# schematics.net
KiCad netlist of a schematic drawn in EAGLE
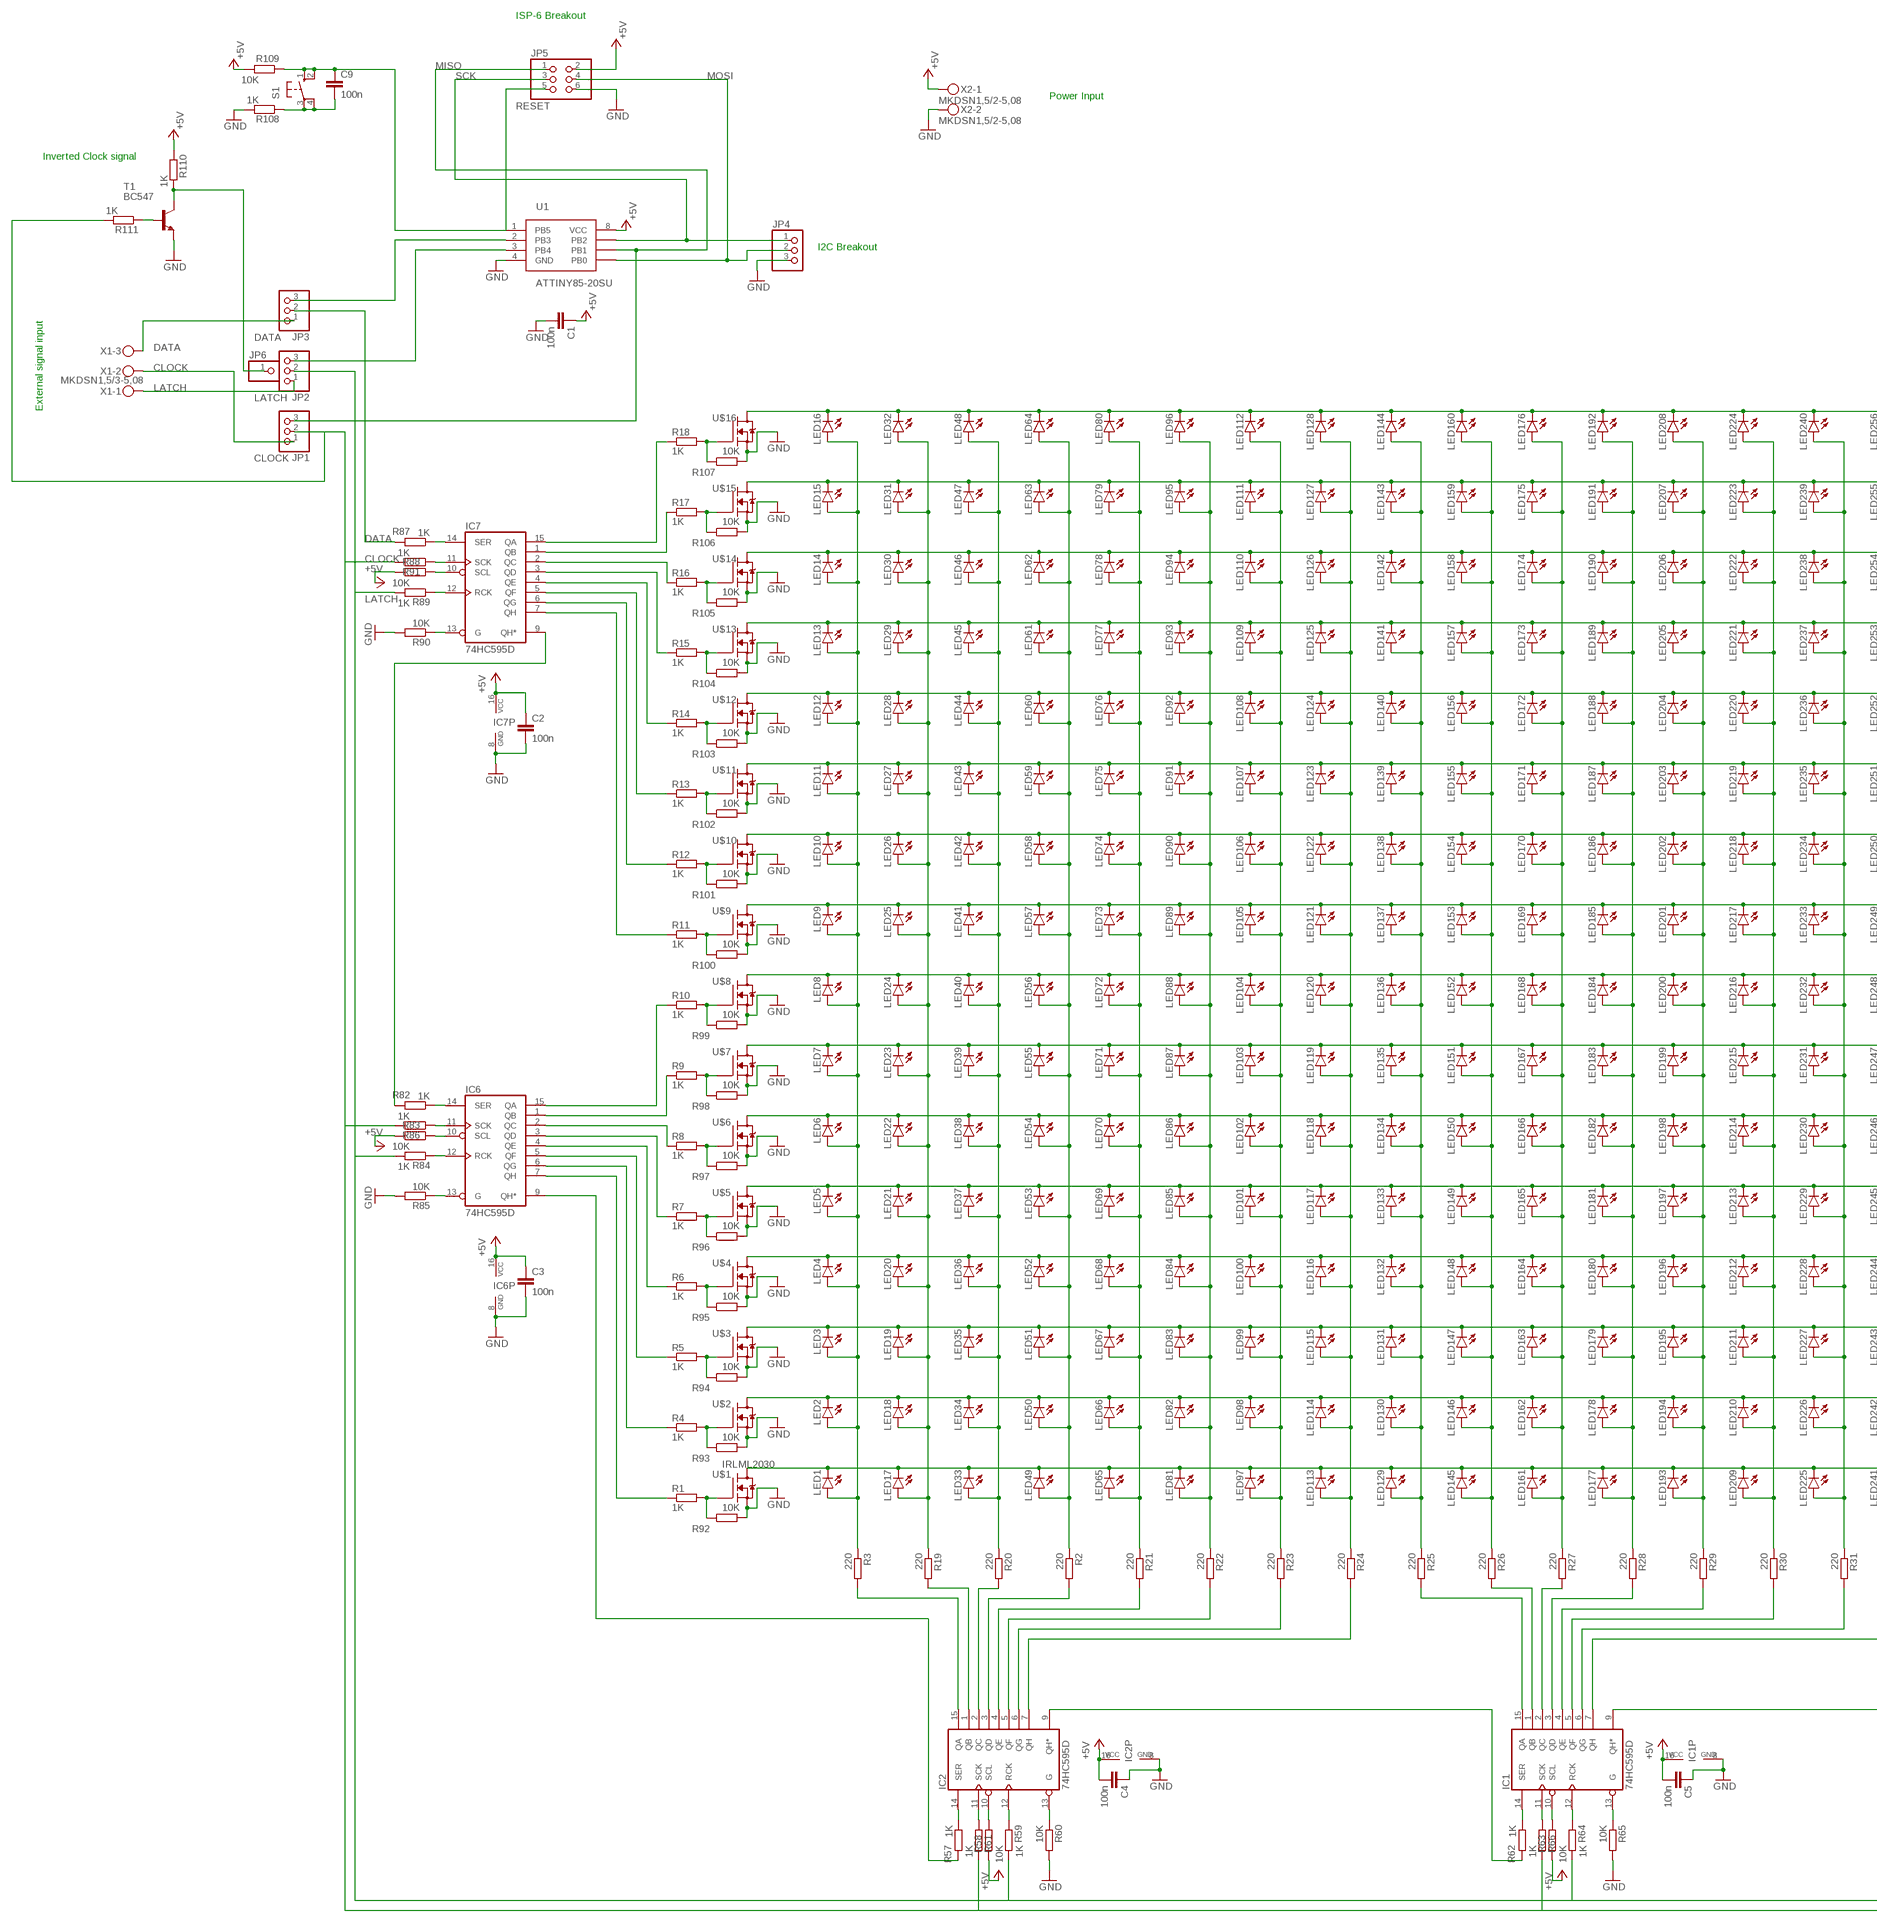
[diagram p0: schematic, sheet 1, part 1 of 2]
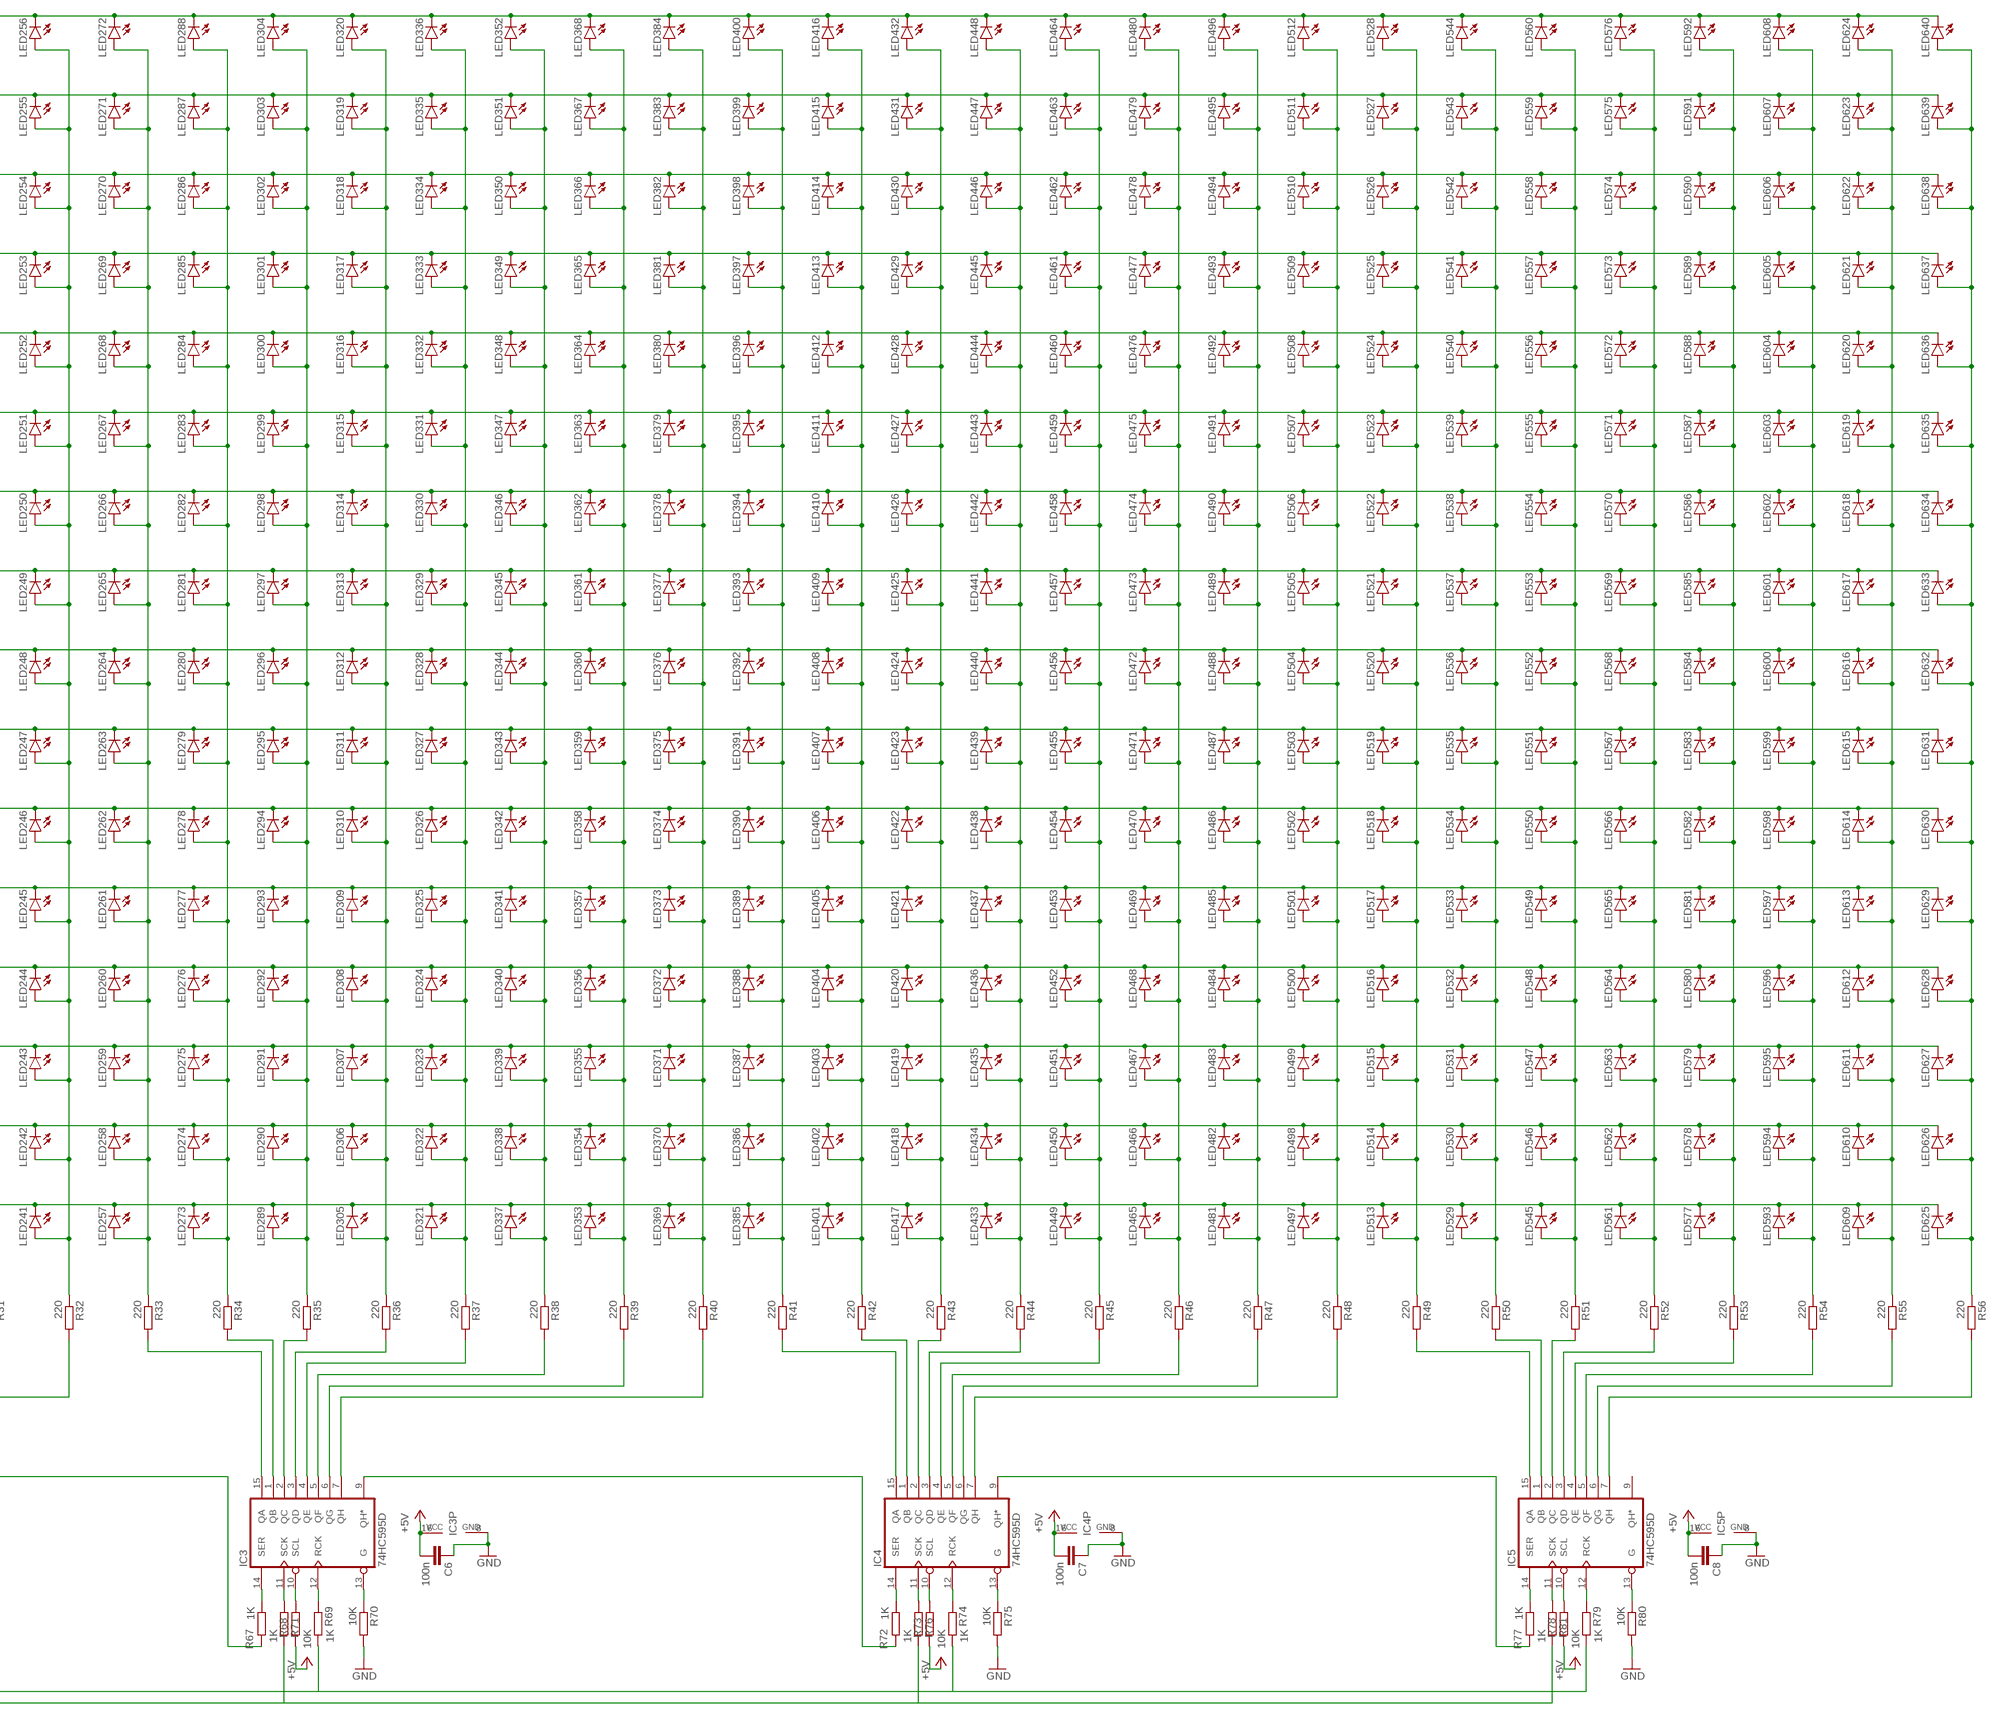
[diagram p1: schematic, sheet 1, part 2 of 2]

(export (version "E")
  (design (tool "Eeschema 10.0.6"))
  (components
    (comp (ref "C1")
      (value "100n")
      (footprint "eagle-import:C0805K")
      (libsource (lib "eagle-import") (part "C-EUC0805K"))
    )
    (comp (ref "C2")
      (value "100n")
      (footprint "eagle-import:C0805K")
      (libsource (lib "eagle-import") (part "C-EUC0805K"))
    )
    (comp (ref "C3")
      (value "100n")
      (footprint "eagle-import:C0805K")
      (libsource (lib "eagle-import") (part "C-EUC0805K"))
    )
    (comp (ref "C4")
      (value "100n")
      (footprint "eagle-import:C0805K")
      (libsource (lib "eagle-import") (part "C-EUC0805K"))
    )
    (comp (ref "C5")
      (value "100n")
      (footprint "eagle-import:C0805K")
      (libsource (lib "eagle-import") (part "C-EUC0805K"))
    )
    (comp (ref "C6")
      (value "100n")
      (footprint "eagle-import:C0805K")
      (libsource (lib "eagle-import") (part "C-EUC0805K"))
    )
    (comp (ref "C7")
      (value "100n")
      (footprint "eagle-import:C0805K")
      (libsource (lib "eagle-import") (part "C-EUC0805K"))
    )
    (comp (ref "C8")
      (value "100n")
      (footprint "eagle-import:C0805K")
      (libsource (lib "eagle-import") (part "C-EUC0805K"))
    )
    (comp (ref "C9")
      (value "100n")
      (footprint "eagle-import:C0805K")
      (libsource (lib "eagle-import") (part "C-EUC0805K"))
    )
    (comp (ref "IC1")
      (value "74HC595D")
      (footprint "eagle-import:SO16")
      (libsource (lib "eagle-import") (part "74595DHC"))
    )
    (comp (ref "IC2")
      (value "74HC595D")
      (footprint "eagle-import:SO16")
      (libsource (lib "eagle-import") (part "74595DHC"))
    )
    (comp (ref "IC3")
      (value "74HC595D")
      (footprint "eagle-import:SO16")
      (libsource (lib "eagle-import") (part "74595DHC"))
    )
    (comp (ref "IC4")
      (value "74HC595D")
      (footprint "eagle-import:SO16")
      (libsource (lib "eagle-import") (part "74595DHC"))
    )
    (comp (ref "IC5")
      (value "74HC595D")
      (footprint "eagle-import:SO16")
      (libsource (lib "eagle-import") (part "74595DHC"))
    )
    (comp (ref "IC6")
      (value "74HC595D")
      (footprint "eagle-import:SO16")
      (libsource (lib "eagle-import") (part "74595DHC"))
    )
    (comp (ref "IC7")
      (value "74HC595D")
      (footprint "eagle-import:SO16")
      (libsource (lib "eagle-import") (part "74595DHC"))
    )
    (comp (ref "JP1")
      (value "PINHD-1X3")
      (footprint "eagle-import:1X03")
      (libsource (lib "eagle-import") (part "PINHD-1X3"))
    )
    (comp (ref "JP2")
      (value "PINHD-1X3")
      (footprint "eagle-import:1X03")
      (libsource (lib "eagle-import") (part "PINHD-1X3"))
    )
    (comp (ref "JP3")
      (value "PINHD-1X3")
      (footprint "eagle-import:1X03")
      (libsource (lib "eagle-import") (part "PINHD-1X3"))
    )
    (comp (ref "JP4")
      (value "PINHD-1X3")
      (footprint "eagle-import:1X03")
      (libsource (lib "eagle-import") (part "PINHD-1X3"))
    )
    (comp (ref "JP5")
      (value "PINHD-2X3")
      (footprint "eagle-import:2X03")
      (libsource (lib "eagle-import") (part "PINHD-2X3"))
    )
    (comp (ref "JP6")
      (value "PINHD-1X1")
      (footprint "eagle-import:1X01")
      (libsource (lib "eagle-import") (part "PINHD-1X1"))
    )
    (comp (ref "LED1")
      (value "LED3MM")
      (footprint "eagle-import:LED3MM")
      (libsource (lib "eagle-import") (part "LED3MM"))
    )
    (comp (ref "LED2")
      (value "LED3MM")
      (footprint "eagle-import:LED3MM")
      (libsource (lib "eagle-import") (part "LED3MM"))
    )
    (comp (ref "LED3")
      (value "LED3MM")
      (footprint "eagle-import:LED3MM")
      (libsource (lib "eagle-import") (part "LED3MM"))
    )
    (comp (ref "LED4")
      (value "LED3MM")
      (footprint "eagle-import:LED3MM")
      (libsource (lib "eagle-import") (part "LED3MM"))
    )
    (comp (ref "LED5")
      (value "LED3MM")
      (footprint "eagle-import:LED3MM")
      (libsource (lib "eagle-import") (part "LED3MM"))
    )
    (comp (ref "LED6")
      (value "LED3MM")
      (footprint "eagle-import:LED3MM")
      (libsource (lib "eagle-import") (part "LED3MM"))
    )
    (comp (ref "LED7")
      (value "LED3MM")
      (footprint "eagle-import:LED3MM")
      (libsource (lib "eagle-import") (part "LED3MM"))
    )
    (comp (ref "LED8")
      (value "LED3MM")
      (footprint "eagle-import:LED3MM")
      (libsource (lib "eagle-import") (part "LED3MM"))
    )
    (comp (ref "LED9")
      (value "LED3MM")
      (footprint "eagle-import:LED3MM")
      (libsource (lib "eagle-import") (part "LED3MM"))
    )
    (comp (ref "LED10")
      (value "LED3MM")
      (footprint "eagle-import:LED3MM")
      (libsource (lib "eagle-import") (part "LED3MM"))
    )
    (comp (ref "LED11")
      (value "LED3MM")
      (footprint "eagle-import:LED3MM")
      (libsource (lib "eagle-import") (part "LED3MM"))
    )
    (comp (ref "LED12")
      (value "LED3MM")
      (footprint "eagle-import:LED3MM")
      (libsource (lib "eagle-import") (part "LED3MM"))
    )
    (comp (ref "LED13")
      (value "LED3MM")
      (footprint "eagle-import:LED3MM")
      (libsource (lib "eagle-import") (part "LED3MM"))
    )
    (comp (ref "LED14")
      (value "LED3MM")
      (footprint "eagle-import:LED3MM")
      (libsource (lib "eagle-import") (part "LED3MM"))
    )
    (comp (ref "LED15")
      (value "LED3MM")
      (footprint "eagle-import:LED3MM")
      (libsource (lib "eagle-import") (part "LED3MM"))
    )
    (comp (ref "LED16")
      (value "LED3MM")
      (footprint "eagle-import:LED3MM")
      (libsource (lib "eagle-import") (part "LED3MM"))
    )
    (comp (ref "LED17")
      (value "LED3MM")
      (footprint "eagle-import:LED3MM")
      (libsource (lib "eagle-import") (part "LED3MM"))
    )
    (comp (ref "LED18")
      (value "LED3MM")
      (footprint "eagle-import:LED3MM")
      (libsource (lib "eagle-import") (part "LED3MM"))
    )
    (comp (ref "LED19")
      (value "LED3MM")
      (footprint "eagle-import:LED3MM")
      (libsource (lib "eagle-import") (part "LED3MM"))
    )
    (comp (ref "LED20")
      (value "LED3MM")
      (footprint "eagle-import:LED3MM")
      (libsource (lib "eagle-import") (part "LED3MM"))
    )
    (comp (ref "LED21")
      (value "LED3MM")
      (footprint "eagle-import:LED3MM")
      (libsource (lib "eagle-import") (part "LED3MM"))
    )
    (comp (ref "LED22")
      (value "LED3MM")
      (footprint "eagle-import:LED3MM")
      (libsource (lib "eagle-import") (part "LED3MM"))
    )
    (comp (ref "LED23")
      (value "LED3MM")
      (footprint "eagle-import:LED3MM")
      (libsource (lib "eagle-import") (part "LED3MM"))
    )
    (comp (ref "LED24")
      (value "LED3MM")
      (footprint "eagle-import:LED3MM")
      (libsource (lib "eagle-import") (part "LED3MM"))
    )
    (comp (ref "LED25")
      (value "LED3MM")
      (footprint "eagle-import:LED3MM")
      (libsource (lib "eagle-import") (part "LED3MM"))
    )
    (comp (ref "LED26")
      (value "LED3MM")
      (footprint "eagle-import:LED3MM")
      (libsource (lib "eagle-import") (part "LED3MM"))
    )
    (comp (ref "LED27")
      (value "LED3MM")
      (footprint "eagle-import:LED3MM")
      (libsource (lib "eagle-import") (part "LED3MM"))
    )
    (comp (ref "LED28")
      (value "LED3MM")
      (footprint "eagle-import:LED3MM")
      (libsource (lib "eagle-import") (part "LED3MM"))
    )
    (comp (ref "LED29")
      (value "LED3MM")
      (footprint "eagle-import:LED3MM")
      (libsource (lib "eagle-import") (part "LED3MM"))
    )
    (comp (ref "LED30")
      (value "LED3MM")
      (footprint "eagle-import:LED3MM")
      (libsource (lib "eagle-import") (part "LED3MM"))
    )
    (comp (ref "LED31")
      (value "LED3MM")
      (footprint "eagle-import:LED3MM")
      (libsource (lib "eagle-import") (part "LED3MM"))
    )
    (comp (ref "LED32")
      (value "LED3MM")
      (footprint "eagle-import:LED3MM")
      (libsource (lib "eagle-import") (part "LED3MM"))
    )
    (comp (ref "LED33")
      (value "LED3MM")
      (footprint "eagle-import:LED3MM")
      (libsource (lib "eagle-import") (part "LED3MM"))
    )
    (comp (ref "LED34")
      (value "LED3MM")
      (footprint "eagle-import:LED3MM")
      (libsource (lib "eagle-import") (part "LED3MM"))
    )
    (comp (ref "LED35")
      (value "LED3MM")
      (footprint "eagle-import:LED3MM")
      (libsource (lib "eagle-import") (part "LED3MM"))
    )
    (comp (ref "LED36")
      (value "LED3MM")
      (footprint "eagle-import:LED3MM")
      (libsource (lib "eagle-import") (part "LED3MM"))
    )
    (comp (ref "LED37")
      (value "LED3MM")
      (footprint "eagle-import:LED3MM")
      (libsource (lib "eagle-import") (part "LED3MM"))
    )
    (comp (ref "LED38")
      (value "LED3MM")
      (footprint "eagle-import:LED3MM")
      (libsource (lib "eagle-import") (part "LED3MM"))
    )
    (comp (ref "LED39")
      (value "LED3MM")
      (footprint "eagle-import:LED3MM")
      (libsource (lib "eagle-import") (part "LED3MM"))
    )
    (comp (ref "LED40")
      (value "LED3MM")
      (footprint "eagle-import:LED3MM")
      (libsource (lib "eagle-import") (part "LED3MM"))
    )
    (comp (ref "LED41")
      (value "LED3MM")
      (footprint "eagle-import:LED3MM")
      (libsource (lib "eagle-import") (part "LED3MM"))
    )
    (comp (ref "LED42")
      (value "LED3MM")
      (footprint "eagle-import:LED3MM")
      (libsource (lib "eagle-import") (part "LED3MM"))
    )
    (comp (ref "LED43")
      (value "LED3MM")
      (footprint "eagle-import:LED3MM")
      (libsource (lib "eagle-import") (part "LED3MM"))
    )
    (comp (ref "LED44")
      (value "LED3MM")
      (footprint "eagle-import:LED3MM")
      (libsource (lib "eagle-import") (part "LED3MM"))
    )
    (comp (ref "LED45")
      (value "LED3MM")
      (footprint "eagle-import:LED3MM")
      (libsource (lib "eagle-import") (part "LED3MM"))
    )
    (comp (ref "LED46")
      (value "LED3MM")
      (footprint "eagle-import:LED3MM")
      (libsource (lib "eagle-import") (part "LED3MM"))
    )
    (comp (ref "LED47")
      (value "LED3MM")
      (footprint "eagle-import:LED3MM")
      (libsource (lib "eagle-import") (part "LED3MM"))
    )
    (comp (ref "LED48")
      (value "LED3MM")
      (footprint "eagle-import:LED3MM")
      (libsource (lib "eagle-import") (part "LED3MM"))
    )
    (comp (ref "LED49")
      (value "LED3MM")
      (footprint "eagle-import:LED3MM")
      (libsource (lib "eagle-import") (part "LED3MM"))
    )
    (comp (ref "LED50")
      (value "LED3MM")
      (footprint "eagle-import:LED3MM")
      (libsource (lib "eagle-import") (part "LED3MM"))
    )
    (comp (ref "LED51")
      (value "LED3MM")
      (footprint "eagle-import:LED3MM")
      (libsource (lib "eagle-import") (part "LED3MM"))
    )
    (comp (ref "LED52")
      (value "LED3MM")
      (footprint "eagle-import:LED3MM")
      (libsource (lib "eagle-import") (part "LED3MM"))
    )
    (comp (ref "LED53")
      (value "LED3MM")
      (footprint "eagle-import:LED3MM")
      (libsource (lib "eagle-import") (part "LED3MM"))
    )
    (comp (ref "LED54")
      (value "LED3MM")
      (footprint "eagle-import:LED3MM")
      (libsource (lib "eagle-import") (part "LED3MM"))
    )
    (comp (ref "LED55")
      (value "LED3MM")
      (footprint "eagle-import:LED3MM")
      (libsource (lib "eagle-import") (part "LED3MM"))
    )
    (comp (ref "LED56")
      (value "LED3MM")
      (footprint "eagle-import:LED3MM")
      (libsource (lib "eagle-import") (part "LED3MM"))
    )
    (comp (ref "LED57")
      (value "LED3MM")
      (footprint "eagle-import:LED3MM")
      (libsource (lib "eagle-import") (part "LED3MM"))
    )
    (comp (ref "LED58")
      (value "LED3MM")
      (footprint "eagle-import:LED3MM")
      (libsource (lib "eagle-import") (part "LED3MM"))
    )
    (comp (ref "LED59")
      (value "LED3MM")
      (footprint "eagle-import:LED3MM")
      (libsource (lib "eagle-import") (part "LED3MM"))
    )
    (comp (ref "LED60")
      (value "LED3MM")
      (footprint "eagle-import:LED3MM")
      (libsource (lib "eagle-import") (part "LED3MM"))
    )
    (comp (ref "LED61")
      (value "LED3MM")
      (footprint "eagle-import:LED3MM")
      (libsource (lib "eagle-import") (part "LED3MM"))
    )
    (comp (ref "LED62")
      (value "LED3MM")
      (footprint "eagle-import:LED3MM")
      (libsource (lib "eagle-import") (part "LED3MM"))
    )
    (comp (ref "LED63")
      (value "LED3MM")
      (footprint "eagle-import:LED3MM")
      (libsource (lib "eagle-import") (part "LED3MM"))
    )
    (comp (ref "LED64")
      (value "LED3MM")
      (footprint "eagle-import:LED3MM")
      (libsource (lib "eagle-import") (part "LED3MM"))
    )
    (comp (ref "LED65")
      (value "LED3MM")
      (footprint "eagle-import:LED3MM")
      (libsource (lib "eagle-import") (part "LED3MM"))
    )
    (comp (ref "LED66")
      (value "LED3MM")
      (footprint "eagle-import:LED3MM")
      (libsource (lib "eagle-import") (part "LED3MM"))
    )
    (comp (ref "LED67")
      (value "LED3MM")
      (footprint "eagle-import:LED3MM")
      (libsource (lib "eagle-import") (part "LED3MM"))
    )
    (comp (ref "LED68")
      (value "LED3MM")
      (footprint "eagle-import:LED3MM")
      (libsource (lib "eagle-import") (part "LED3MM"))
    )
    (comp (ref "LED69")
      (value "LED3MM")
      (footprint "eagle-import:LED3MM")
      (libsource (lib "eagle-import") (part "LED3MM"))
    )
    (comp (ref "LED70")
      (value "LED3MM")
      (footprint "eagle-import:LED3MM")
      (libsource (lib "eagle-import") (part "LED3MM"))
    )
    (comp (ref "LED71")
      (value "LED3MM")
      (footprint "eagle-import:LED3MM")
      (libsource (lib "eagle-import") (part "LED3MM"))
    )
    (comp (ref "LED72")
      (value "LED3MM")
      (footprint "eagle-import:LED3MM")
      (libsource (lib "eagle-import") (part "LED3MM"))
    )
    (comp (ref "LED73")
      (value "LED3MM")
      (footprint "eagle-import:LED3MM")
      (libsource (lib "eagle-import") (part "LED3MM"))
    )
    (comp (ref "LED74")
      (value "LED3MM")
      (footprint "eagle-import:LED3MM")
      (libsource (lib "eagle-import") (part "LED3MM"))
    )
    (comp (ref "LED75")
      (value "LED3MM")
      (footprint "eagle-import:LED3MM")
      (libsource (lib "eagle-import") (part "LED3MM"))
    )
    (comp (ref "LED76")
      (value "LED3MM")
      (footprint "eagle-import:LED3MM")
      (libsource (lib "eagle-import") (part "LED3MM"))
    )
    (comp (ref "LED77")
      (value "LED3MM")
      (footprint "eagle-import:LED3MM")
      (libsource (lib "eagle-import") (part "LED3MM"))
    )
    (comp (ref "LED78")
      (value "LED3MM")
      (footprint "eagle-import:LED3MM")
      (libsource (lib "eagle-import") (part "LED3MM"))
    )
    (comp (ref "LED79")
      (value "LED3MM")
      (footprint "eagle-import:LED3MM")
      (libsource (lib "eagle-import") (part "LED3MM"))
    )
    (comp (ref "LED80")
      (value "LED3MM")
      (footprint "eagle-import:LED3MM")
      (libsource (lib "eagle-import") (part "LED3MM"))
    )
    (comp (ref "LED81")
      (value "LED3MM")
      (footprint "eagle-import:LED3MM")
      (libsource (lib "eagle-import") (part "LED3MM"))
    )
    (comp (ref "LED82")
      (value "LED3MM")
      (footprint "eagle-import:LED3MM")
      (libsource (lib "eagle-import") (part "LED3MM"))
    )
    (comp (ref "LED83")
      (value "LED3MM")
      (footprint "eagle-import:LED3MM")
      (libsource (lib "eagle-import") (part "LED3MM"))
    )
    (comp (ref "LED84")
      (value "LED3MM")
      (footprint "eagle-import:LED3MM")
      (libsource (lib "eagle-import") (part "LED3MM"))
    )
    (comp (ref "LED85")
      (value "LED3MM")
      (footprint "eagle-import:LED3MM")
      (libsource (lib "eagle-import") (part "LED3MM"))
    )
    (comp (ref "LED86")
      (value "LED3MM")
      (footprint "eagle-import:LED3MM")
      (libsource (lib "eagle-import") (part "LED3MM"))
    )
    (comp (ref "LED87")
      (value "LED3MM")
      (footprint "eagle-import:LED3MM")
      (libsource (lib "eagle-import") (part "LED3MM"))
    )
    (comp (ref "LED88")
      (value "LED3MM")
      (footprint "eagle-import:LED3MM")
      (libsource (lib "eagle-import") (part "LED3MM"))
    )
    (comp (ref "LED89")
      (value "LED3MM")
      (footprint "eagle-import:LED3MM")
      (libsource (lib "eagle-import") (part "LED3MM"))
    )
    (comp (ref "LED90")
      (value "LED3MM")
      (footprint "eagle-import:LED3MM")
      (libsource (lib "eagle-import") (part "LED3MM"))
    )
    (comp (ref "LED91")
      (value "LED3MM")
      (footprint "eagle-import:LED3MM")
      (libsource (lib "eagle-import") (part "LED3MM"))
    )
    (comp (ref "LED92")
      (value "LED3MM")
      (footprint "eagle-import:LED3MM")
      (libsource (lib "eagle-import") (part "LED3MM"))
    )
    (comp (ref "LED93")
      (value "LED3MM")
      (footprint "eagle-import:LED3MM")
      (libsource (lib "eagle-import") (part "LED3MM"))
    )
    (comp (ref "LED94")
      (value "LED3MM")
      (footprint "eagle-import:LED3MM")
      (libsource (lib "eagle-import") (part "LED3MM"))
    )
    (comp (ref "LED95")
      (value "LED3MM")
      (footprint "eagle-import:LED3MM")
      (libsource (lib "eagle-import") (part "LED3MM"))
    )
    (comp (ref "LED96")
      (value "LED3MM")
      (footprint "eagle-import:LED3MM")
      (libsource (lib "eagle-import") (part "LED3MM"))
    )
    (comp (ref "LED97")
      (value "LED3MM")
      (footprint "eagle-import:LED3MM")
      (libsource (lib "eagle-import") (part "LED3MM"))
    )
    (comp (ref "LED98")
      (value "LED3MM")
      (footprint "eagle-import:LED3MM")
      (libsource (lib "eagle-import") (part "LED3MM"))
    )
    (comp (ref "LED99")
      (value "LED3MM")
      (footprint "eagle-import:LED3MM")
      (libsource (lib "eagle-import") (part "LED3MM"))
    )
    (comp (ref "LED100")
      (value "LED3MM")
      (footprint "eagle-import:LED3MM")
      (libsource (lib "eagle-import") (part "LED3MM"))
    )
    (comp (ref "LED101")
      (value "LED3MM")
      (footprint "eagle-import:LED3MM")
      (libsource (lib "eagle-import") (part "LED3MM"))
    )
    (comp (ref "LED102")
      (value "LED3MM")
      (footprint "eagle-import:LED3MM")
      (libsource (lib "eagle-import") (part "LED3MM"))
    )
    (comp (ref "LED103")
      (value "LED3MM")
      (footprint "eagle-import:LED3MM")
      (libsource (lib "eagle-import") (part "LED3MM"))
    )
    (comp (ref "LED104")
      (value "LED3MM")
      (footprint "eagle-import:LED3MM")
      (libsource (lib "eagle-import") (part "LED3MM"))
    )
    (comp (ref "LED105")
      (value "LED3MM")
      (footprint "eagle-import:LED3MM")
      (libsource (lib "eagle-import") (part "LED3MM"))
    )
    (comp (ref "LED106")
      (value "LED3MM")
      (footprint "eagle-import:LED3MM")
      (libsource (lib "eagle-import") (part "LED3MM"))
    )
    (comp (ref "LED107")
      (value "LED3MM")
      (footprint "eagle-import:LED3MM")
      (libsource (lib "eagle-import") (part "LED3MM"))
    )
    (comp (ref "LED108")
      (value "LED3MM")
      (footprint "eagle-import:LED3MM")
      (libsource (lib "eagle-import") (part "LED3MM"))
    )
    (comp (ref "LED109")
      (value "LED3MM")
      (footprint "eagle-import:LED3MM")
      (libsource (lib "eagle-import") (part "LED3MM"))
    )
    (comp (ref "LED110")
      (value "LED3MM")
      (footprint "eagle-import:LED3MM")
      (libsource (lib "eagle-import") (part "LED3MM"))
    )
    (comp (ref "LED111")
      (value "LED3MM")
      (footprint "eagle-import:LED3MM")
      (libsource (lib "eagle-import") (part "LED3MM"))
    )
    (comp (ref "LED112")
      (value "LED3MM")
      (footprint "eagle-import:LED3MM")
      (libsource (lib "eagle-import") (part "LED3MM"))
    )
    (comp (ref "LED113")
      (value "LED3MM")
      (footprint "eagle-import:LED3MM")
      (libsource (lib "eagle-import") (part "LED3MM"))
    )
    (comp (ref "LED114")
      (value "LED3MM")
      (footprint "eagle-import:LED3MM")
      (libsource (lib "eagle-import") (part "LED3MM"))
    )
    (comp (ref "LED115")
      (value "LED3MM")
      (footprint "eagle-import:LED3MM")
      (libsource (lib "eagle-import") (part "LED3MM"))
    )
    (comp (ref "LED116")
      (value "LED3MM")
      (footprint "eagle-import:LED3MM")
      (libsource (lib "eagle-import") (part "LED3MM"))
    )
    (comp (ref "LED117")
      (value "LED3MM")
      (footprint "eagle-import:LED3MM")
      (libsource (lib "eagle-import") (part "LED3MM"))
    )
    (comp (ref "LED118")
      (value "LED3MM")
      (footprint "eagle-import:LED3MM")
      (libsource (lib "eagle-import") (part "LED3MM"))
    )
    (comp (ref "LED119")
      (value "LED3MM")
      (footprint "eagle-import:LED3MM")
      (libsource (lib "eagle-import") (part "LED3MM"))
    )
    (comp (ref "LED120")
      (value "LED3MM")
      (footprint "eagle-import:LED3MM")
      (libsource (lib "eagle-import") (part "LED3MM"))
    )
    (comp (ref "LED121")
      (value "LED3MM")
      (footprint "eagle-import:LED3MM")
      (libsource (lib "eagle-import") (part "LED3MM"))
    )
    (comp (ref "LED122")
      (value "LED3MM")
      (footprint "eagle-import:LED3MM")
      (libsource (lib "eagle-import") (part "LED3MM"))
    )
    (comp (ref "LED123")
      (value "LED3MM")
      (footprint "eagle-import:LED3MM")
      (libsource (lib "eagle-import") (part "LED3MM"))
    )
    (comp (ref "LED124")
      (value "LED3MM")
      (footprint "eagle-import:LED3MM")
      (libsource (lib "eagle-import") (part "LED3MM"))
    )
    (comp (ref "LED125")
      (value "LED3MM")
      (footprint "eagle-import:LED3MM")
      (libsource (lib "eagle-import") (part "LED3MM"))
    )
    (comp (ref "LED126")
      (value "LED3MM")
      (footprint "eagle-import:LED3MM")
      (libsource (lib "eagle-import") (part "LED3MM"))
    )
    (comp (ref "LED127")
      (value "LED3MM")
      (footprint "eagle-import:LED3MM")
      (libsource (lib "eagle-import") (part "LED3MM"))
    )
    (comp (ref "LED128")
      (value "LED3MM")
      (footprint "eagle-import:LED3MM")
      (libsource (lib "eagle-import") (part "LED3MM"))
    )
    (comp (ref "LED129")
      (value "LED3MM")
      (footprint "eagle-import:LED3MM")
      (libsource (lib "eagle-import") (part "LED3MM"))
    )
    (comp (ref "LED130")
      (value "LED3MM")
      (footprint "eagle-import:LED3MM")
      (libsource (lib "eagle-import") (part "LED3MM"))
    )
    (comp (ref "LED131")
      (value "LED3MM")
      (footprint "eagle-import:LED3MM")
      (libsource (lib "eagle-import") (part "LED3MM"))
    )
    (comp (ref "LED132")
      (value "LED3MM")
      (footprint "eagle-import:LED3MM")
      (libsource (lib "eagle-import") (part "LED3MM"))
    )
    (comp (ref "LED133")
      (value "LED3MM")
      (footprint "eagle-import:LED3MM")
      (libsource (lib "eagle-import") (part "LED3MM"))
    )
    (comp (ref "LED134")
      (value "LED3MM")
      (footprint "eagle-import:LED3MM")
      (libsource (lib "eagle-import") (part "LED3MM"))
    )
    (comp (ref "LED135")
      (value "LED3MM")
      (footprint "eagle-import:LED3MM")
      (libsource (lib "eagle-import") (part "LED3MM"))
    )
    (comp (ref "LED136")
      (value "LED3MM")
      (footprint "eagle-import:LED3MM")
      (libsource (lib "eagle-import") (part "LED3MM"))
    )
    (comp (ref "LED137")
      (value "LED3MM")
      (footprint "eagle-import:LED3MM")
      (libsource (lib "eagle-import") (part "LED3MM"))
    )
    (comp (ref "LED138")
      (value "LED3MM")
      (footprint "eagle-import:LED3MM")
      (libsource (lib "eagle-import") (part "LED3MM"))
    )
    (comp (ref "LED139")
      (value "LED3MM")
      (footprint "eagle-import:LED3MM")
      (libsource (lib "eagle-import") (part "LED3MM"))
    )
    (comp (ref "LED140")
      (value "LED3MM")
      (footprint "eagle-import:LED3MM")
      (libsource (lib "eagle-import") (part "LED3MM"))
    )
    (comp (ref "LED141")
      (value "LED3MM")
      (footprint "eagle-import:LED3MM")
      (libsource (lib "eagle-import") (part "LED3MM"))
    )
    (comp (ref "LED142")
      (value "LED3MM")
      (footprint "eagle-import:LED3MM")
      (libsource (lib "eagle-import") (part "LED3MM"))
    )
    (comp (ref "LED143")
      (value "LED3MM")
      (footprint "eagle-import:LED3MM")
      (libsource (lib "eagle-import") (part "LED3MM"))
    )
    (comp (ref "LED144")
      (value "LED3MM")
      (footprint "eagle-import:LED3MM")
      (libsource (lib "eagle-import") (part "LED3MM"))
    )
    (comp (ref "LED145")
      (value "LED3MM")
      (footprint "eagle-import:LED3MM")
      (libsource (lib "eagle-import") (part "LED3MM"))
    )
    (comp (ref "LED146")
      (value "LED3MM")
      (footprint "eagle-import:LED3MM")
      (libsource (lib "eagle-import") (part "LED3MM"))
    )
    (comp (ref "LED147")
      (value "LED3MM")
      (footprint "eagle-import:LED3MM")
      (libsource (lib "eagle-import") (part "LED3MM"))
    )
    (comp (ref "LED148")
      (value "LED3MM")
      (footprint "eagle-import:LED3MM")
      (libsource (lib "eagle-import") (part "LED3MM"))
    )
    (comp (ref "LED149")
      (value "LED3MM")
      (footprint "eagle-import:LED3MM")
      (libsource (lib "eagle-import") (part "LED3MM"))
    )
    (comp (ref "LED150")
      (value "LED3MM")
      (footprint "eagle-import:LED3MM")
      (libsource (lib "eagle-import") (part "LED3MM"))
    )
    (comp (ref "LED151")
      (value "LED3MM")
      (footprint "eagle-import:LED3MM")
      (libsource (lib "eagle-import") (part "LED3MM"))
    )
    (comp (ref "LED152")
      (value "LED3MM")
      (footprint "eagle-import:LED3MM")
      (libsource (lib "eagle-import") (part "LED3MM"))
    )
    (comp (ref "LED153")
      (value "LED3MM")
      (footprint "eagle-import:LED3MM")
      (libsource (lib "eagle-import") (part "LED3MM"))
    )
    (comp (ref "LED154")
      (value "LED3MM")
      (footprint "eagle-import:LED3MM")
      (libsource (lib "eagle-import") (part "LED3MM"))
    )
    (comp (ref "LED155")
      (value "LED3MM")
      (footprint "eagle-import:LED3MM")
      (libsource (lib "eagle-import") (part "LED3MM"))
    )
    (comp (ref "LED156")
      (value "LED3MM")
      (footprint "eagle-import:LED3MM")
      (libsource (lib "eagle-import") (part "LED3MM"))
    )
    (comp (ref "LED157")
      (value "LED3MM")
      (footprint "eagle-import:LED3MM")
      (libsource (lib "eagle-import") (part "LED3MM"))
    )
    (comp (ref "LED158")
      (value "LED3MM")
      (footprint "eagle-import:LED3MM")
      (libsource (lib "eagle-import") (part "LED3MM"))
    )
    (comp (ref "LED159")
      (value "LED3MM")
      (footprint "eagle-import:LED3MM")
      (libsource (lib "eagle-import") (part "LED3MM"))
    )
    (comp (ref "LED160")
      (value "LED3MM")
      (footprint "eagle-import:LED3MM")
      (libsource (lib "eagle-import") (part "LED3MM"))
    )
    (comp (ref "LED161")
      (value "LED3MM")
      (footprint "eagle-import:LED3MM")
      (libsource (lib "eagle-import") (part "LED3MM"))
    )
    (comp (ref "LED162")
      (value "LED3MM")
      (footprint "eagle-import:LED3MM")
      (libsource (lib "eagle-import") (part "LED3MM"))
    )
    (comp (ref "LED163")
      (value "LED3MM")
      (footprint "eagle-import:LED3MM")
      (libsource (lib "eagle-import") (part "LED3MM"))
    )
    (comp (ref "LED164")
      (value "LED3MM")
      (footprint "eagle-import:LED3MM")
      (libsource (lib "eagle-import") (part "LED3MM"))
    )
    (comp (ref "LED165")
      (value "LED3MM")
      (footprint "eagle-import:LED3MM")
      (libsource (lib "eagle-import") (part "LED3MM"))
    )
    (comp (ref "LED166")
      (value "LED3MM")
      (footprint "eagle-import:LED3MM")
      (libsource (lib "eagle-import") (part "LED3MM"))
    )
    (comp (ref "LED167")
      (value "LED3MM")
      (footprint "eagle-import:LED3MM")
      (libsource (lib "eagle-import") (part "LED3MM"))
    )
    (comp (ref "LED168")
      (value "LED3MM")
      (footprint "eagle-import:LED3MM")
      (libsource (lib "eagle-import") (part "LED3MM"))
    )
    (comp (ref "LED169")
      (value "LED3MM")
      (footprint "eagle-import:LED3MM")
      (libsource (lib "eagle-import") (part "LED3MM"))
    )
    (comp (ref "LED170")
      (value "LED3MM")
      (footprint "eagle-import:LED3MM")
      (libsource (lib "eagle-import") (part "LED3MM"))
    )
    (comp (ref "LED171")
      (value "LED3MM")
      (footprint "eagle-import:LED3MM")
      (libsource (lib "eagle-import") (part "LED3MM"))
    )
    (comp (ref "LED172")
      (value "LED3MM")
      (footprint "eagle-import:LED3MM")
      (libsource (lib "eagle-import") (part "LED3MM"))
    )
    (comp (ref "LED173")
      (value "LED3MM")
      (footprint "eagle-import:LED3MM")
      (libsource (lib "eagle-import") (part "LED3MM"))
    )
    (comp (ref "LED174")
      (value "LED3MM")
      (footprint "eagle-import:LED3MM")
      (libsource (lib "eagle-import") (part "LED3MM"))
    )
    (comp (ref "LED175")
      (value "LED3MM")
      (footprint "eagle-import:LED3MM")
      (libsource (lib "eagle-import") (part "LED3MM"))
    )
    (comp (ref "LED176")
      (value "LED3MM")
      (footprint "eagle-import:LED3MM")
      (libsource (lib "eagle-import") (part "LED3MM"))
    )
    (comp (ref "LED177")
      (value "LED3MM")
      (footprint "eagle-import:LED3MM")
      (libsource (lib "eagle-import") (part "LED3MM"))
    )
    (comp (ref "LED178")
      (value "LED3MM")
      (footprint "eagle-import:LED3MM")
      (libsource (lib "eagle-import") (part "LED3MM"))
    )
    (comp (ref "LED179")
      (value "LED3MM")
      (footprint "eagle-import:LED3MM")
      (libsource (lib "eagle-import") (part "LED3MM"))
    )
    (comp (ref "LED180")
      (value "LED3MM")
      (footprint "eagle-import:LED3MM")
      (libsource (lib "eagle-import") (part "LED3MM"))
    )
    (comp (ref "LED181")
      (value "LED3MM")
      (footprint "eagle-import:LED3MM")
      (libsource (lib "eagle-import") (part "LED3MM"))
    )
    (comp (ref "LED182")
      (value "LED3MM")
      (footprint "eagle-import:LED3MM")
      (libsource (lib "eagle-import") (part "LED3MM"))
    )
    (comp (ref "LED183")
      (value "LED3MM")
      (footprint "eagle-import:LED3MM")
      (libsource (lib "eagle-import") (part "LED3MM"))
    )
    (comp (ref "LED184")
      (value "LED3MM")
      (footprint "eagle-import:LED3MM")
      (libsource (lib "eagle-import") (part "LED3MM"))
    )
    (comp (ref "LED185")
      (value "LED3MM")
      (footprint "eagle-import:LED3MM")
      (libsource (lib "eagle-import") (part "LED3MM"))
    )
    (comp (ref "LED186")
      (value "LED3MM")
      (footprint "eagle-import:LED3MM")
      (libsource (lib "eagle-import") (part "LED3MM"))
    )
    (comp (ref "LED187")
      (value "LED3MM")
      (footprint "eagle-import:LED3MM")
      (libsource (lib "eagle-import") (part "LED3MM"))
    )
    (comp (ref "LED188")
      (value "LED3MM")
      (footprint "eagle-import:LED3MM")
      (libsource (lib "eagle-import") (part "LED3MM"))
    )
    (comp (ref "LED189")
      (value "LED3MM")
      (footprint "eagle-import:LED3MM")
      (libsource (lib "eagle-import") (part "LED3MM"))
    )
    (comp (ref "LED190")
      (value "LED3MM")
      (footprint "eagle-import:LED3MM")
      (libsource (lib "eagle-import") (part "LED3MM"))
    )
    (comp (ref "LED191")
      (value "LED3MM")
      (footprint "eagle-import:LED3MM")
      (libsource (lib "eagle-import") (part "LED3MM"))
    )
    (comp (ref "LED192")
      (value "LED3MM")
      (footprint "eagle-import:LED3MM")
      (libsource (lib "eagle-import") (part "LED3MM"))
    )
    (comp (ref "LED193")
      (value "LED3MM")
      (footprint "eagle-import:LED3MM")
      (libsource (lib "eagle-import") (part "LED3MM"))
    )
    (comp (ref "LED194")
      (value "LED3MM")
      (footprint "eagle-import:LED3MM")
      (libsource (lib "eagle-import") (part "LED3MM"))
    )
    (comp (ref "LED195")
      (value "LED3MM")
      (footprint "eagle-import:LED3MM")
      (libsource (lib "eagle-import") (part "LED3MM"))
    )
    (comp (ref "LED196")
      (value "LED3MM")
      (footprint "eagle-import:LED3MM")
      (libsource (lib "eagle-import") (part "LED3MM"))
    )
    (comp (ref "LED197")
      (value "LED3MM")
      (footprint "eagle-import:LED3MM")
      (libsource (lib "eagle-import") (part "LED3MM"))
    )
    (comp (ref "LED198")
      (value "LED3MM")
      (footprint "eagle-import:LED3MM")
      (libsource (lib "eagle-import") (part "LED3MM"))
    )
    (comp (ref "LED199")
      (value "LED3MM")
      (footprint "eagle-import:LED3MM")
      (libsource (lib "eagle-import") (part "LED3MM"))
    )
    (comp (ref "LED200")
      (value "LED3MM")
      (footprint "eagle-import:LED3MM")
      (libsource (lib "eagle-import") (part "LED3MM"))
    )
    (comp (ref "LED201")
      (value "LED3MM")
      (footprint "eagle-import:LED3MM")
      (libsource (lib "eagle-import") (part "LED3MM"))
    )
    (comp (ref "LED202")
      (value "LED3MM")
      (footprint "eagle-import:LED3MM")
      (libsource (lib "eagle-import") (part "LED3MM"))
    )
    (comp (ref "LED203")
      (value "LED3MM")
      (footprint "eagle-import:LED3MM")
      (libsource (lib "eagle-import") (part "LED3MM"))
    )
    (comp (ref "LED204")
      (value "LED3MM")
      (footprint "eagle-import:LED3MM")
      (libsource (lib "eagle-import") (part "LED3MM"))
    )
    (comp (ref "LED205")
      (value "LED3MM")
      (footprint "eagle-import:LED3MM")
      (libsource (lib "eagle-import") (part "LED3MM"))
    )
    (comp (ref "LED206")
      (value "LED3MM")
      (footprint "eagle-import:LED3MM")
      (libsource (lib "eagle-import") (part "LED3MM"))
    )
    (comp (ref "LED207")
      (value "LED3MM")
      (footprint "eagle-import:LED3MM")
      (libsource (lib "eagle-import") (part "LED3MM"))
    )
    (comp (ref "LED208")
      (value "LED3MM")
      (footprint "eagle-import:LED3MM")
      (libsource (lib "eagle-import") (part "LED3MM"))
    )
    (comp (ref "LED209")
      (value "LED3MM")
      (footprint "eagle-import:LED3MM")
      (libsource (lib "eagle-import") (part "LED3MM"))
    )
    (comp (ref "LED210")
      (value "LED3MM")
      (footprint "eagle-import:LED3MM")
      (libsource (lib "eagle-import") (part "LED3MM"))
    )
    (comp (ref "LED211")
      (value "LED3MM")
      (footprint "eagle-import:LED3MM")
      (libsource (lib "eagle-import") (part "LED3MM"))
    )
    (comp (ref "LED212")
      (value "LED3MM")
      (footprint "eagle-import:LED3MM")
      (libsource (lib "eagle-import") (part "LED3MM"))
    )
    (comp (ref "LED213")
      (value "LED3MM")
      (footprint "eagle-import:LED3MM")
      (libsource (lib "eagle-import") (part "LED3MM"))
    )
    (comp (ref "LED214")
      (value "LED3MM")
      (footprint "eagle-import:LED3MM")
      (libsource (lib "eagle-import") (part "LED3MM"))
    )
    (comp (ref "LED215")
      (value "LED3MM")
      (footprint "eagle-import:LED3MM")
      (libsource (lib "eagle-import") (part "LED3MM"))
    )
    (comp (ref "LED216")
      (value "LED3MM")
      (footprint "eagle-import:LED3MM")
      (libsource (lib "eagle-import") (part "LED3MM"))
    )
    (comp (ref "LED217")
      (value "LED3MM")
      (footprint "eagle-import:LED3MM")
      (libsource (lib "eagle-import") (part "LED3MM"))
    )
    (comp (ref "LED218")
      (value "LED3MM")
      (footprint "eagle-import:LED3MM")
      (libsource (lib "eagle-import") (part "LED3MM"))
    )
    (comp (ref "LED219")
      (value "LED3MM")
      (footprint "eagle-import:LED3MM")
      (libsource (lib "eagle-import") (part "LED3MM"))
    )
    (comp (ref "LED220")
      (value "LED3MM")
      (footprint "eagle-import:LED3MM")
      (libsource (lib "eagle-import") (part "LED3MM"))
    )
    (comp (ref "LED221")
      (value "LED3MM")
      (footprint "eagle-import:LED3MM")
      (libsource (lib "eagle-import") (part "LED3MM"))
    )
    (comp (ref "LED222")
      (value "LED3MM")
      (footprint "eagle-import:LED3MM")
      (libsource (lib "eagle-import") (part "LED3MM"))
    )
    (comp (ref "LED223")
      (value "LED3MM")
      (footprint "eagle-import:LED3MM")
      (libsource (lib "eagle-import") (part "LED3MM"))
    )
    (comp (ref "LED224")
      (value "LED3MM")
      (footprint "eagle-import:LED3MM")
      (libsource (lib "eagle-import") (part "LED3MM"))
    )
    (comp (ref "LED225")
      (value "LED3MM")
      (footprint "eagle-import:LED3MM")
      (libsource (lib "eagle-import") (part "LED3MM"))
    )
    (comp (ref "LED226")
      (value "LED3MM")
      (footprint "eagle-import:LED3MM")
      (libsource (lib "eagle-import") (part "LED3MM"))
    )
    (comp (ref "LED227")
      (value "LED3MM")
      (footprint "eagle-import:LED3MM")
      (libsource (lib "eagle-import") (part "LED3MM"))
    )
    (comp (ref "LED228")
      (value "LED3MM")
      (footprint "eagle-import:LED3MM")
      (libsource (lib "eagle-import") (part "LED3MM"))
    )
    (comp (ref "LED229")
      (value "LED3MM")
      (footprint "eagle-import:LED3MM")
      (libsource (lib "eagle-import") (part "LED3MM"))
    )
    (comp (ref "LED230")
      (value "LED3MM")
      (footprint "eagle-import:LED3MM")
      (libsource (lib "eagle-import") (part "LED3MM"))
    )
    (comp (ref "LED231")
      (value "LED3MM")
      (footprint "eagle-import:LED3MM")
      (libsource (lib "eagle-import") (part "LED3MM"))
    )
    (comp (ref "LED232")
      (value "LED3MM")
      (footprint "eagle-import:LED3MM")
      (libsource (lib "eagle-import") (part "LED3MM"))
    )
    (comp (ref "LED233")
      (value "LED3MM")
      (footprint "eagle-import:LED3MM")
      (libsource (lib "eagle-import") (part "LED3MM"))
    )
    (comp (ref "LED234")
      (value "LED3MM")
      (footprint "eagle-import:LED3MM")
      (libsource (lib "eagle-import") (part "LED3MM"))
    )
    (comp (ref "LED235")
      (value "LED3MM")
      (footprint "eagle-import:LED3MM")
      (libsource (lib "eagle-import") (part "LED3MM"))
    )
    (comp (ref "LED236")
      (value "LED3MM")
      (footprint "eagle-import:LED3MM")
      (libsource (lib "eagle-import") (part "LED3MM"))
    )
    (comp (ref "LED237")
      (value "LED3MM")
      (footprint "eagle-import:LED3MM")
      (libsource (lib "eagle-import") (part "LED3MM"))
    )
    (comp (ref "LED238")
      (value "LED3MM")
      (footprint "eagle-import:LED3MM")
      (libsource (lib "eagle-import") (part "LED3MM"))
    )
    (comp (ref "LED239")
      (value "LED3MM")
      (footprint "eagle-import:LED3MM")
      (libsource (lib "eagle-import") (part "LED3MM"))
    )
    (comp (ref "LED240")
      (value "LED3MM")
      (footprint "eagle-import:LED3MM")
      (libsource (lib "eagle-import") (part "LED3MM"))
    )
    (comp (ref "LED241")
      (value "LED3MM")
      (footprint "eagle-import:LED3MM")
      (libsource (lib "eagle-import") (part "LED3MM"))
    )
    (comp (ref "LED242")
      (value "LED3MM")
      (footprint "eagle-import:LED3MM")
      (libsource (lib "eagle-import") (part "LED3MM"))
    )
    (comp (ref "LED243")
      (value "LED3MM")
      (footprint "eagle-import:LED3MM")
      (libsource (lib "eagle-import") (part "LED3MM"))
    )
    (comp (ref "LED244")
      (value "LED3MM")
      (footprint "eagle-import:LED3MM")
      (libsource (lib "eagle-import") (part "LED3MM"))
    )
    (comp (ref "LED245")
      (value "LED3MM")
      (footprint "eagle-import:LED3MM")
      (libsource (lib "eagle-import") (part "LED3MM"))
    )
    (comp (ref "LED246")
      (value "LED3MM")
      (footprint "eagle-import:LED3MM")
      (libsource (lib "eagle-import") (part "LED3MM"))
    )
    (comp (ref "LED247")
      (value "LED3MM")
      (footprint "eagle-import:LED3MM")
      (libsource (lib "eagle-import") (part "LED3MM"))
    )
    (comp (ref "LED248")
      (value "LED3MM")
      (footprint "eagle-import:LED3MM")
      (libsource (lib "eagle-import") (part "LED3MM"))
    )
    (comp (ref "LED249")
      (value "LED3MM")
      (footprint "eagle-import:LED3MM")
      (libsource (lib "eagle-import") (part "LED3MM"))
    )
    (comp (ref "LED250")
      (value "LED3MM")
      (footprint "eagle-import:LED3MM")
      (libsource (lib "eagle-import") (part "LED3MM"))
    )
    (comp (ref "LED251")
      (value "LED3MM")
      (footprint "eagle-import:LED3MM")
      (libsource (lib "eagle-import") (part "LED3MM"))
    )
    (comp (ref "LED252")
      (value "LED3MM")
      (footprint "eagle-import:LED3MM")
      (libsource (lib "eagle-import") (part "LED3MM"))
    )
    (comp (ref "LED253")
      (value "LED3MM")
      (footprint "eagle-import:LED3MM")
      (libsource (lib "eagle-import") (part "LED3MM"))
    )
    (comp (ref "LED254")
      (value "LED3MM")
      (footprint "eagle-import:LED3MM")
      (libsource (lib "eagle-import") (part "LED3MM"))
    )
    (comp (ref "LED255")
      (value "LED3MM")
      (footprint "eagle-import:LED3MM")
      (libsource (lib "eagle-import") (part "LED3MM"))
    )
    (comp (ref "LED256")
      (value "LED3MM")
      (footprint "eagle-import:LED3MM")
      (libsource (lib "eagle-import") (part "LED3MM"))
    )
    (comp (ref "LED257")
      (value "LED3MM")
      (footprint "eagle-import:LED3MM")
      (libsource (lib "eagle-import") (part "LED3MM"))
    )
    (comp (ref "LED258")
      (value "LED3MM")
      (footprint "eagle-import:LED3MM")
      (libsource (lib "eagle-import") (part "LED3MM"))
    )
    (comp (ref "LED259")
      (value "LED3MM")
      (footprint "eagle-import:LED3MM")
      (libsource (lib "eagle-import") (part "LED3MM"))
    )
    (comp (ref "LED260")
      (value "LED3MM")
      (footprint "eagle-import:LED3MM")
      (libsource (lib "eagle-import") (part "LED3MM"))
    )
    (comp (ref "LED261")
      (value "LED3MM")
      (footprint "eagle-import:LED3MM")
      (libsource (lib "eagle-import") (part "LED3MM"))
    )
    (comp (ref "LED262")
      (value "LED3MM")
      (footprint "eagle-import:LED3MM")
      (libsource (lib "eagle-import") (part "LED3MM"))
    )
    (comp (ref "LED263")
      (value "LED3MM")
      (footprint "eagle-import:LED3MM")
      (libsource (lib "eagle-import") (part "LED3MM"))
    )
    (comp (ref "LED264")
      (value "LED3MM")
      (footprint "eagle-import:LED3MM")
      (libsource (lib "eagle-import") (part "LED3MM"))
    )
    (comp (ref "LED265")
      (value "LED3MM")
      (footprint "eagle-import:LED3MM")
      (libsource (lib "eagle-import") (part "LED3MM"))
    )
    (comp (ref "LED266")
      (value "LED3MM")
      (footprint "eagle-import:LED3MM")
      (libsource (lib "eagle-import") (part "LED3MM"))
    )
    (comp (ref "LED267")
      (value "LED3MM")
      (footprint "eagle-import:LED3MM")
      (libsource (lib "eagle-import") (part "LED3MM"))
    )
    (comp (ref "LED268")
      (value "LED3MM")
      (footprint "eagle-import:LED3MM")
      (libsource (lib "eagle-import") (part "LED3MM"))
    )
    (comp (ref "LED269")
      (value "LED3MM")
      (footprint "eagle-import:LED3MM")
      (libsource (lib "eagle-import") (part "LED3MM"))
    )
    (comp (ref "LED270")
      (value "LED3MM")
      (footprint "eagle-import:LED3MM")
      (libsource (lib "eagle-import") (part "LED3MM"))
    )
    (comp (ref "LED271")
      (value "LED3MM")
      (footprint "eagle-import:LED3MM")
      (libsource (lib "eagle-import") (part "LED3MM"))
    )
    (comp (ref "LED272")
      (value "LED3MM")
      (footprint "eagle-import:LED3MM")
      (libsource (lib "eagle-import") (part "LED3MM"))
    )
    (comp (ref "LED273")
      (value "LED3MM")
      (footprint "eagle-import:LED3MM")
      (libsource (lib "eagle-import") (part "LED3MM"))
    )
    (comp (ref "LED274")
      (value "LED3MM")
      (footprint "eagle-import:LED3MM")
      (libsource (lib "eagle-import") (part "LED3MM"))
    )
    (comp (ref "LED275")
      (value "LED3MM")
      (footprint "eagle-import:LED3MM")
      (libsource (lib "eagle-import") (part "LED3MM"))
    )
    (comp (ref "LED276")
      (value "LED3MM")
      (footprint "eagle-import:LED3MM")
      (libsource (lib "eagle-import") (part "LED3MM"))
    )
    (comp (ref "LED277")
      (value "LED3MM")
      (footprint "eagle-import:LED3MM")
      (libsource (lib "eagle-import") (part "LED3MM"))
    )
    (comp (ref "LED278")
      (value "LED3MM")
      (footprint "eagle-import:LED3MM")
      (libsource (lib "eagle-import") (part "LED3MM"))
    )
    (comp (ref "LED279")
      (value "LED3MM")
      (footprint "eagle-import:LED3MM")
      (libsource (lib "eagle-import") (part "LED3MM"))
    )
    (comp (ref "LED280")
      (value "LED3MM")
      (footprint "eagle-import:LED3MM")
      (libsource (lib "eagle-import") (part "LED3MM"))
    )
    (comp (ref "LED281")
      (value "LED3MM")
      (footprint "eagle-import:LED3MM")
      (libsource (lib "eagle-import") (part "LED3MM"))
    )
    (comp (ref "LED282")
      (value "LED3MM")
      (footprint "eagle-import:LED3MM")
      (libsource (lib "eagle-import") (part "LED3MM"))
    )
    (comp (ref "LED283")
      (value "LED3MM")
      (footprint "eagle-import:LED3MM")
      (libsource (lib "eagle-import") (part "LED3MM"))
    )
    (comp (ref "LED284")
      (value "LED3MM")
      (footprint "eagle-import:LED3MM")
      (libsource (lib "eagle-import") (part "LED3MM"))
    )
    (comp (ref "LED285")
      (value "LED3MM")
      (footprint "eagle-import:LED3MM")
      (libsource (lib "eagle-import") (part "LED3MM"))
    )
    (comp (ref "LED286")
      (value "LED3MM")
      (footprint "eagle-import:LED3MM")
      (libsource (lib "eagle-import") (part "LED3MM"))
    )
    (comp (ref "LED287")
      (value "LED3MM")
      (footprint "eagle-import:LED3MM")
      (libsource (lib "eagle-import") (part "LED3MM"))
    )
    (comp (ref "LED288")
      (value "LED3MM")
      (footprint "eagle-import:LED3MM")
      (libsource (lib "eagle-import") (part "LED3MM"))
    )
    (comp (ref "LED289")
      (value "LED3MM")
      (footprint "eagle-import:LED3MM")
      (libsource (lib "eagle-import") (part "LED3MM"))
    )
    (comp (ref "LED290")
      (value "LED3MM")
      (footprint "eagle-import:LED3MM")
      (libsource (lib "eagle-import") (part "LED3MM"))
    )
    (comp (ref "LED291")
      (value "LED3MM")
      (footprint "eagle-import:LED3MM")
      (libsource (lib "eagle-import") (part "LED3MM"))
    )
    (comp (ref "LED292")
      (value "LED3MM")
      (footprint "eagle-import:LED3MM")
      (libsource (lib "eagle-import") (part "LED3MM"))
    )
    (comp (ref "LED293")
      (value "LED3MM")
      (footprint "eagle-import:LED3MM")
      (libsource (lib "eagle-import") (part "LED3MM"))
    )
    (comp (ref "LED294")
      (value "LED3MM")
      (footprint "eagle-import:LED3MM")
      (libsource (lib "eagle-import") (part "LED3MM"))
    )
    (comp (ref "LED295")
      (value "LED3MM")
      (footprint "eagle-import:LED3MM")
      (libsource (lib "eagle-import") (part "LED3MM"))
    )
    (comp (ref "LED296")
      (value "LED3MM")
      (footprint "eagle-import:LED3MM")
      (libsource (lib "eagle-import") (part "LED3MM"))
    )
    (comp (ref "LED297")
      (value "LED3MM")
      (footprint "eagle-import:LED3MM")
      (libsource (lib "eagle-import") (part "LED3MM"))
    )
    (comp (ref "LED298")
      (value "LED3MM")
      (footprint "eagle-import:LED3MM")
      (libsource (lib "eagle-import") (part "LED3MM"))
    )
    (comp (ref "LED299")
      (value "LED3MM")
      (footprint "eagle-import:LED3MM")
      (libsource (lib "eagle-import") (part "LED3MM"))
    )
    (comp (ref "LED300")
      (value "LED3MM")
      (footprint "eagle-import:LED3MM")
      (libsource (lib "eagle-import") (part "LED3MM"))
    )
    (comp (ref "LED301")
      (value "LED3MM")
      (footprint "eagle-import:LED3MM")
      (libsource (lib "eagle-import") (part "LED3MM"))
    )
    (comp (ref "LED302")
      (value "LED3MM")
      (footprint "eagle-import:LED3MM")
      (libsource (lib "eagle-import") (part "LED3MM"))
    )
    (comp (ref "LED303")
      (value "LED3MM")
      (footprint "eagle-import:LED3MM")
      (libsource (lib "eagle-import") (part "LED3MM"))
    )
    (comp (ref "LED304")
      (value "LED3MM")
      (footprint "eagle-import:LED3MM")
      (libsource (lib "eagle-import") (part "LED3MM"))
    )
    (comp (ref "LED305")
      (value "LED3MM")
      (footprint "eagle-import:LED3MM")
      (libsource (lib "eagle-import") (part "LED3MM"))
    )
    (comp (ref "LED306")
      (value "LED3MM")
      (footprint "eagle-import:LED3MM")
      (libsource (lib "eagle-import") (part "LED3MM"))
    )
    (comp (ref "LED307")
      (value "LED3MM")
      (footprint "eagle-import:LED3MM")
      (libsource (lib "eagle-import") (part "LED3MM"))
    )
    (comp (ref "LED308")
      (value "LED3MM")
      (footprint "eagle-import:LED3MM")
      (libsource (lib "eagle-import") (part "LED3MM"))
    )
    (comp (ref "LED309")
      (value "LED3MM")
      (footprint "eagle-import:LED3MM")
      (libsource (lib "eagle-import") (part "LED3MM"))
    )
    (comp (ref "LED310")
      (value "LED3MM")
      (footprint "eagle-import:LED3MM")
      (libsource (lib "eagle-import") (part "LED3MM"))
    )
    (comp (ref "LED311")
      (value "LED3MM")
      (footprint "eagle-import:LED3MM")
      (libsource (lib "eagle-import") (part "LED3MM"))
    )
    (comp (ref "LED312")
      (value "LED3MM")
      (footprint "eagle-import:LED3MM")
      (libsource (lib "eagle-import") (part "LED3MM"))
    )
    (comp (ref "LED313")
      (value "LED3MM")
      (footprint "eagle-import:LED3MM")
      (libsource (lib "eagle-import") (part "LED3MM"))
    )
    (comp (ref "LED314")
      (value "LED3MM")
      (footprint "eagle-import:LED3MM")
      (libsource (lib "eagle-import") (part "LED3MM"))
    )
    (comp (ref "LED315")
      (value "LED3MM")
      (footprint "eagle-import:LED3MM")
      (libsource (lib "eagle-import") (part "LED3MM"))
    )
    (comp (ref "LED316")
      (value "LED3MM")
      (footprint "eagle-import:LED3MM")
      (libsource (lib "eagle-import") (part "LED3MM"))
    )
    (comp (ref "LED317")
      (value "LED3MM")
      (footprint "eagle-import:LED3MM")
      (libsource (lib "eagle-import") (part "LED3MM"))
    )
    (comp (ref "LED318")
      (value "LED3MM")
      (footprint "eagle-import:LED3MM")
      (libsource (lib "eagle-import") (part "LED3MM"))
    )
    (comp (ref "LED319")
      (value "LED3MM")
      (footprint "eagle-import:LED3MM")
      (libsource (lib "eagle-import") (part "LED3MM"))
    )
    (comp (ref "LED320")
      (value "LED3MM")
      (footprint "eagle-import:LED3MM")
      (libsource (lib "eagle-import") (part "LED3MM"))
    )
    (comp (ref "LED321")
      (value "LED3MM")
      (footprint "eagle-import:LED3MM")
      (libsource (lib "eagle-import") (part "LED3MM"))
    )
    (comp (ref "LED322")
      (value "LED3MM")
      (footprint "eagle-import:LED3MM")
      (libsource (lib "eagle-import") (part "LED3MM"))
    )
    (comp (ref "LED323")
      (value "LED3MM")
      (footprint "eagle-import:LED3MM")
      (libsource (lib "eagle-import") (part "LED3MM"))
    )
    (comp (ref "LED324")
      (value "LED3MM")
      (footprint "eagle-import:LED3MM")
      (libsource (lib "eagle-import") (part "LED3MM"))
    )
    (comp (ref "LED325")
      (value "LED3MM")
      (footprint "eagle-import:LED3MM")
      (libsource (lib "eagle-import") (part "LED3MM"))
    )
    (comp (ref "LED326")
      (value "LED3MM")
      (footprint "eagle-import:LED3MM")
      (libsource (lib "eagle-import") (part "LED3MM"))
    )
    (comp (ref "LED327")
      (value "LED3MM")
      (footprint "eagle-import:LED3MM")
      (libsource (lib "eagle-import") (part "LED3MM"))
    )
    (comp (ref "LED328")
      (value "LED3MM")
      (footprint "eagle-import:LED3MM")
      (libsource (lib "eagle-import") (part "LED3MM"))
    )
    (comp (ref "LED329")
      (value "LED3MM")
      (footprint "eagle-import:LED3MM")
      (libsource (lib "eagle-import") (part "LED3MM"))
    )
    (comp (ref "LED330")
      (value "LED3MM")
      (footprint "eagle-import:LED3MM")
      (libsource (lib "eagle-import") (part "LED3MM"))
    )
    (comp (ref "LED331")
      (value "LED3MM")
      (footprint "eagle-import:LED3MM")
      (libsource (lib "eagle-import") (part "LED3MM"))
    )
    (comp (ref "LED332")
      (value "LED3MM")
      (footprint "eagle-import:LED3MM")
      (libsource (lib "eagle-import") (part "LED3MM"))
    )
    (comp (ref "LED333")
      (value "LED3MM")
      (footprint "eagle-import:LED3MM")
      (libsource (lib "eagle-import") (part "LED3MM"))
    )
    (comp (ref "LED334")
      (value "LED3MM")
      (footprint "eagle-import:LED3MM")
      (libsource (lib "eagle-import") (part "LED3MM"))
    )
    (comp (ref "LED335")
      (value "LED3MM")
      (footprint "eagle-import:LED3MM")
      (libsource (lib "eagle-import") (part "LED3MM"))
    )
    (comp (ref "LED336")
      (value "LED3MM")
      (footprint "eagle-import:LED3MM")
      (libsource (lib "eagle-import") (part "LED3MM"))
    )
    (comp (ref "LED337")
      (value "LED3MM")
      (footprint "eagle-import:LED3MM")
      (libsource (lib "eagle-import") (part "LED3MM"))
    )
    (comp (ref "LED338")
      (value "LED3MM")
      (footprint "eagle-import:LED3MM")
      (libsource (lib "eagle-import") (part "LED3MM"))
    )
    (comp (ref "LED339")
      (value "LED3MM")
      (footprint "eagle-import:LED3MM")
      (libsource (lib "eagle-import") (part "LED3MM"))
    )
    (comp (ref "LED340")
      (value "LED3MM")
      (footprint "eagle-import:LED3MM")
      (libsource (lib "eagle-import") (part "LED3MM"))
    )
    (comp (ref "LED341")
      (value "LED3MM")
      (footprint "eagle-import:LED3MM")
      (libsource (lib "eagle-import") (part "LED3MM"))
    )
    (comp (ref "LED342")
      (value "LED3MM")
      (footprint "eagle-import:LED3MM")
      (libsource (lib "eagle-import") (part "LED3MM"))
    )
    (comp (ref "LED343")
      (value "LED3MM")
      (footprint "eagle-import:LED3MM")
      (libsource (lib "eagle-import") (part "LED3MM"))
    )
    (comp (ref "LED344")
      (value "LED3MM")
      (footprint "eagle-import:LED3MM")
      (libsource (lib "eagle-import") (part "LED3MM"))
    )
    (comp (ref "LED345")
      (value "LED3MM")
      (footprint "eagle-import:LED3MM")
      (libsource (lib "eagle-import") (part "LED3MM"))
    )
    (comp (ref "LED346")
      (value "LED3MM")
      (footprint "eagle-import:LED3MM")
      (libsource (lib "eagle-import") (part "LED3MM"))
    )
    (comp (ref "LED347")
      (value "LED3MM")
      (footprint "eagle-import:LED3MM")
      (libsource (lib "eagle-import") (part "LED3MM"))
    )
    (comp (ref "LED348")
      (value "LED3MM")
      (footprint "eagle-import:LED3MM")
      (libsource (lib "eagle-import") (part "LED3MM"))
    )
    (comp (ref "LED349")
      (value "LED3MM")
      (footprint "eagle-import:LED3MM")
      (libsource (lib "eagle-import") (part "LED3MM"))
    )
    (comp (ref "LED350")
      (value "LED3MM")
      (footprint "eagle-import:LED3MM")
      (libsource (lib "eagle-import") (part "LED3MM"))
    )
    (comp (ref "LED351")
      (value "LED3MM")
      (footprint "eagle-import:LED3MM")
      (libsource (lib "eagle-import") (part "LED3MM"))
    )
    (comp (ref "LED352")
      (value "LED3MM")
      (footprint "eagle-import:LED3MM")
      (libsource (lib "eagle-import") (part "LED3MM"))
    )
    (comp (ref "LED353")
      (value "LED3MM")
      (footprint "eagle-import:LED3MM")
      (libsource (lib "eagle-import") (part "LED3MM"))
    )
    (comp (ref "LED354")
      (value "LED3MM")
      (footprint "eagle-import:LED3MM")
      (libsource (lib "eagle-import") (part "LED3MM"))
    )
    (comp (ref "LED355")
      (value "LED3MM")
      (footprint "eagle-import:LED3MM")
      (libsource (lib "eagle-import") (part "LED3MM"))
    )
    (comp (ref "LED356")
      (value "LED3MM")
      (footprint "eagle-import:LED3MM")
      (libsource (lib "eagle-import") (part "LED3MM"))
    )
    (comp (ref "LED357")
      (value "LED3MM")
      (footprint "eagle-import:LED3MM")
      (libsource (lib "eagle-import") (part "LED3MM"))
    )
    (comp (ref "LED358")
      (value "LED3MM")
      (footprint "eagle-import:LED3MM")
      (libsource (lib "eagle-import") (part "LED3MM"))
    )
    (comp (ref "LED359")
      (value "LED3MM")
      (footprint "eagle-import:LED3MM")
      (libsource (lib "eagle-import") (part "LED3MM"))
    )
    (comp (ref "LED360")
      (value "LED3MM")
      (footprint "eagle-import:LED3MM")
      (libsource (lib "eagle-import") (part "LED3MM"))
    )
    (comp (ref "LED361")
      (value "LED3MM")
      (footprint "eagle-import:LED3MM")
      (libsource (lib "eagle-import") (part "LED3MM"))
    )
    (comp (ref "LED362")
      (value "LED3MM")
      (footprint "eagle-import:LED3MM")
      (libsource (lib "eagle-import") (part "LED3MM"))
    )
    (comp (ref "LED363")
      (value "LED3MM")
      (footprint "eagle-import:LED3MM")
      (libsource (lib "eagle-import") (part "LED3MM"))
    )
    (comp (ref "LED364")
      (value "LED3MM")
      (footprint "eagle-import:LED3MM")
      (libsource (lib "eagle-import") (part "LED3MM"))
    )
    (comp (ref "LED365")
      (value "LED3MM")
      (footprint "eagle-import:LED3MM")
      (libsource (lib "eagle-import") (part "LED3MM"))
    )
    (comp (ref "LED366")
      (value "LED3MM")
      (footprint "eagle-import:LED3MM")
      (libsource (lib "eagle-import") (part "LED3MM"))
    )
    (comp (ref "LED367")
      (value "LED3MM")
      (footprint "eagle-import:LED3MM")
      (libsource (lib "eagle-import") (part "LED3MM"))
    )
    (comp (ref "LED368")
      (value "LED3MM")
      (footprint "eagle-import:LED3MM")
      (libsource (lib "eagle-import") (part "LED3MM"))
    )
    (comp (ref "LED369")
      (value "LED3MM")
      (footprint "eagle-import:LED3MM")
      (libsource (lib "eagle-import") (part "LED3MM"))
    )
    (comp (ref "LED370")
      (value "LED3MM")
      (footprint "eagle-import:LED3MM")
      (libsource (lib "eagle-import") (part "LED3MM"))
    )
    (comp (ref "LED371")
      (value "LED3MM")
      (footprint "eagle-import:LED3MM")
      (libsource (lib "eagle-import") (part "LED3MM"))
    )
    (comp (ref "LED372")
      (value "LED3MM")
      (footprint "eagle-import:LED3MM")
      (libsource (lib "eagle-import") (part "LED3MM"))
    )
    (comp (ref "LED373")
      (value "LED3MM")
      (footprint "eagle-import:LED3MM")
      (libsource (lib "eagle-import") (part "LED3MM"))
    )
    (comp (ref "LED374")
      (value "LED3MM")
      (footprint "eagle-import:LED3MM")
      (libsource (lib "eagle-import") (part "LED3MM"))
    )
    (comp (ref "LED375")
      (value "LED3MM")
      (footprint "eagle-import:LED3MM")
      (libsource (lib "eagle-import") (part "LED3MM"))
    )
    (comp (ref "LED376")
      (value "LED3MM")
      (footprint "eagle-import:LED3MM")
      (libsource (lib "eagle-import") (part "LED3MM"))
    )
    (comp (ref "LED377")
      (value "LED3MM")
      (footprint "eagle-import:LED3MM")
      (libsource (lib "eagle-import") (part "LED3MM"))
    )
    (comp (ref "LED378")
      (value "LED3MM")
      (footprint "eagle-import:LED3MM")
      (libsource (lib "eagle-import") (part "LED3MM"))
    )
    (comp (ref "LED379")
      (value "LED3MM")
      (footprint "eagle-import:LED3MM")
      (libsource (lib "eagle-import") (part "LED3MM"))
    )
    (comp (ref "LED380")
      (value "LED3MM")
      (footprint "eagle-import:LED3MM")
      (libsource (lib "eagle-import") (part "LED3MM"))
    )
    (comp (ref "LED381")
      (value "LED3MM")
      (footprint "eagle-import:LED3MM")
      (libsource (lib "eagle-import") (part "LED3MM"))
    )
    (comp (ref "LED382")
      (value "LED3MM")
      (footprint "eagle-import:LED3MM")
      (libsource (lib "eagle-import") (part "LED3MM"))
    )
    (comp (ref "LED383")
      (value "LED3MM")
      (footprint "eagle-import:LED3MM")
      (libsource (lib "eagle-import") (part "LED3MM"))
    )
    (comp (ref "LED384")
      (value "LED3MM")
      (footprint "eagle-import:LED3MM")
      (libsource (lib "eagle-import") (part "LED3MM"))
    )
    (comp (ref "LED385")
      (value "LED3MM")
      (footprint "eagle-import:LED3MM")
      (libsource (lib "eagle-import") (part "LED3MM"))
    )
    (comp (ref "LED386")
      (value "LED3MM")
      (footprint "eagle-import:LED3MM")
      (libsource (lib "eagle-import") (part "LED3MM"))
    )
    (comp (ref "LED387")
      (value "LED3MM")
      (footprint "eagle-import:LED3MM")
      (libsource (lib "eagle-import") (part "LED3MM"))
    )
    (comp (ref "LED388")
      (value "LED3MM")
      (footprint "eagle-import:LED3MM")
      (libsource (lib "eagle-import") (part "LED3MM"))
    )
    (comp (ref "LED389")
      (value "LED3MM")
      (footprint "eagle-import:LED3MM")
      (libsource (lib "eagle-import") (part "LED3MM"))
    )
    (comp (ref "LED390")
      (value "LED3MM")
      (footprint "eagle-import:LED3MM")
      (libsource (lib "eagle-import") (part "LED3MM"))
    )
    (comp (ref "LED391")
      (value "LED3MM")
      (footprint "eagle-import:LED3MM")
      (libsource (lib "eagle-import") (part "LED3MM"))
    )
    (comp (ref "LED392")
      (value "LED3MM")
      (footprint "eagle-import:LED3MM")
      (libsource (lib "eagle-import") (part "LED3MM"))
    )
    (comp (ref "LED393")
      (value "LED3MM")
      (footprint "eagle-import:LED3MM")
      (libsource (lib "eagle-import") (part "LED3MM"))
    )
    (comp (ref "LED394")
      (value "LED3MM")
      (footprint "eagle-import:LED3MM")
      (libsource (lib "eagle-import") (part "LED3MM"))
    )
    (comp (ref "LED395")
      (value "LED3MM")
      (footprint "eagle-import:LED3MM")
      (libsource (lib "eagle-import") (part "LED3MM"))
    )
    (comp (ref "LED396")
      (value "LED3MM")
      (footprint "eagle-import:LED3MM")
      (libsource (lib "eagle-import") (part "LED3MM"))
    )
    (comp (ref "LED397")
      (value "LED3MM")
      (footprint "eagle-import:LED3MM")
      (libsource (lib "eagle-import") (part "LED3MM"))
    )
    (comp (ref "LED398")
      (value "LED3MM")
      (footprint "eagle-import:LED3MM")
      (libsource (lib "eagle-import") (part "LED3MM"))
    )
    (comp (ref "LED399")
      (value "LED3MM")
      (footprint "eagle-import:LED3MM")
      (libsource (lib "eagle-import") (part "LED3MM"))
    )
    (comp (ref "LED400")
      (value "LED3MM")
      (footprint "eagle-import:LED3MM")
      (libsource (lib "eagle-import") (part "LED3MM"))
    )
    (comp (ref "LED401")
      (value "LED3MM")
      (footprint "eagle-import:LED3MM")
      (libsource (lib "eagle-import") (part "LED3MM"))
    )
    (comp (ref "LED402")
      (value "LED3MM")
      (footprint "eagle-import:LED3MM")
      (libsource (lib "eagle-import") (part "LED3MM"))
    )
    (comp (ref "LED403")
      (value "LED3MM")
      (footprint "eagle-import:LED3MM")
      (libsource (lib "eagle-import") (part "LED3MM"))
    )
    (comp (ref "LED404")
      (value "LED3MM")
      (footprint "eagle-import:LED3MM")
      (libsource (lib "eagle-import") (part "LED3MM"))
    )
    (comp (ref "LED405")
      (value "LED3MM")
      (footprint "eagle-import:LED3MM")
      (libsource (lib "eagle-import") (part "LED3MM"))
    )
    (comp (ref "LED406")
      (value "LED3MM")
      (footprint "eagle-import:LED3MM")
      (libsource (lib "eagle-import") (part "LED3MM"))
    )
    (comp (ref "LED407")
      (value "LED3MM")
      (footprint "eagle-import:LED3MM")
      (libsource (lib "eagle-import") (part "LED3MM"))
    )
    (comp (ref "LED408")
      (value "LED3MM")
      (footprint "eagle-import:LED3MM")
      (libsource (lib "eagle-import") (part "LED3MM"))
    )
    (comp (ref "LED409")
      (value "LED3MM")
      (footprint "eagle-import:LED3MM")
      (libsource (lib "eagle-import") (part "LED3MM"))
    )
    (comp (ref "LED410")
      (value "LED3MM")
      (footprint "eagle-import:LED3MM")
      (libsource (lib "eagle-import") (part "LED3MM"))
    )
    (comp (ref "LED411")
      (value "LED3MM")
      (footprint "eagle-import:LED3MM")
      (libsource (lib "eagle-import") (part "LED3MM"))
    )
    (comp (ref "LED412")
      (value "LED3MM")
      (footprint "eagle-import:LED3MM")
      (libsource (lib "eagle-import") (part "LED3MM"))
    )
    (comp (ref "LED413")
      (value "LED3MM")
      (footprint "eagle-import:LED3MM")
      (libsource (lib "eagle-import") (part "LED3MM"))
    )
    (comp (ref "LED414")
      (value "LED3MM")
      (footprint "eagle-import:LED3MM")
      (libsource (lib "eagle-import") (part "LED3MM"))
    )
    (comp (ref "LED415")
      (value "LED3MM")
      (footprint "eagle-import:LED3MM")
      (libsource (lib "eagle-import") (part "LED3MM"))
    )
    (comp (ref "LED416")
      (value "LED3MM")
      (footprint "eagle-import:LED3MM")
      (libsource (lib "eagle-import") (part "LED3MM"))
    )
    (comp (ref "LED417")
      (value "LED3MM")
      (footprint "eagle-import:LED3MM")
      (libsource (lib "eagle-import") (part "LED3MM"))
    )
    (comp (ref "LED418")
      (value "LED3MM")
      (footprint "eagle-import:LED3MM")
      (libsource (lib "eagle-import") (part "LED3MM"))
    )
    (comp (ref "LED419")
      (value "LED3MM")
      (footprint "eagle-import:LED3MM")
      (libsource (lib "eagle-import") (part "LED3MM"))
    )
    (comp (ref "LED420")
      (value "LED3MM")
      (footprint "eagle-import:LED3MM")
      (libsource (lib "eagle-import") (part "LED3MM"))
    )
    (comp (ref "LED421")
      (value "LED3MM")
      (footprint "eagle-import:LED3MM")
      (libsource (lib "eagle-import") (part "LED3MM"))
    )
    (comp (ref "LED422")
      (value "LED3MM")
      (footprint "eagle-import:LED3MM")
      (libsource (lib "eagle-import") (part "LED3MM"))
    )
    (comp (ref "LED423")
      (value "LED3MM")
      (footprint "eagle-import:LED3MM")
      (libsource (lib "eagle-import") (part "LED3MM"))
    )
    (comp (ref "LED424")
      (value "LED3MM")
      (footprint "eagle-import:LED3MM")
      (libsource (lib "eagle-import") (part "LED3MM"))
    )
    (comp (ref "LED425")
      (value "LED3MM")
      (footprint "eagle-import:LED3MM")
      (libsource (lib "eagle-import") (part "LED3MM"))
    )
    (comp (ref "LED426")
      (value "LED3MM")
      (footprint "eagle-import:LED3MM")
      (libsource (lib "eagle-import") (part "LED3MM"))
    )
    (comp (ref "LED427")
      (value "LED3MM")
      (footprint "eagle-import:LED3MM")
      (libsource (lib "eagle-import") (part "LED3MM"))
    )
    (comp (ref "LED428")
      (value "LED3MM")
      (footprint "eagle-import:LED3MM")
      (libsource (lib "eagle-import") (part "LED3MM"))
    )
    (comp (ref "LED429")
      (value "LED3MM")
      (footprint "eagle-import:LED3MM")
      (libsource (lib "eagle-import") (part "LED3MM"))
    )
    (comp (ref "LED430")
      (value "LED3MM")
      (footprint "eagle-import:LED3MM")
      (libsource (lib "eagle-import") (part "LED3MM"))
    )
    (comp (ref "LED431")
      (value "LED3MM")
      (footprint "eagle-import:LED3MM")
      (libsource (lib "eagle-import") (part "LED3MM"))
    )
    (comp (ref "LED432")
      (value "LED3MM")
      (footprint "eagle-import:LED3MM")
      (libsource (lib "eagle-import") (part "LED3MM"))
    )
    (comp (ref "LED433")
      (value "LED3MM")
      (footprint "eagle-import:LED3MM")
      (libsource (lib "eagle-import") (part "LED3MM"))
    )
    (comp (ref "LED434")
      (value "LED3MM")
      (footprint "eagle-import:LED3MM")
      (libsource (lib "eagle-import") (part "LED3MM"))
    )
    (comp (ref "LED435")
      (value "LED3MM")
      (footprint "eagle-import:LED3MM")
      (libsource (lib "eagle-import") (part "LED3MM"))
    )
    (comp (ref "LED436")
      (value "LED3MM")
      (footprint "eagle-import:LED3MM")
      (libsource (lib "eagle-import") (part "LED3MM"))
    )
    (comp (ref "LED437")
      (value "LED3MM")
      (footprint "eagle-import:LED3MM")
      (libsource (lib "eagle-import") (part "LED3MM"))
    )
    (comp (ref "LED438")
      (value "LED3MM")
      (footprint "eagle-import:LED3MM")
      (libsource (lib "eagle-import") (part "LED3MM"))
    )
    (comp (ref "LED439")
      (value "LED3MM")
      (footprint "eagle-import:LED3MM")
      (libsource (lib "eagle-import") (part "LED3MM"))
    )
    (comp (ref "LED440")
      (value "LED3MM")
      (footprint "eagle-import:LED3MM")
      (libsource (lib "eagle-import") (part "LED3MM"))
    )
    (comp (ref "LED441")
      (value "LED3MM")
      (footprint "eagle-import:LED3MM")
      (libsource (lib "eagle-import") (part "LED3MM"))
    )
    (comp (ref "LED442")
      (value "LED3MM")
      (footprint "eagle-import:LED3MM")
      (libsource (lib "eagle-import") (part "LED3MM"))
    )
    (comp (ref "LED443")
      (value "LED3MM")
      (footprint "eagle-import:LED3MM")
      (libsource (lib "eagle-import") (part "LED3MM"))
    )
    (comp (ref "LED444")
      (value "LED3MM")
      (footprint "eagle-import:LED3MM")
      (libsource (lib "eagle-import") (part "LED3MM"))
    )
    (comp (ref "LED445")
      (value "LED3MM")
      (footprint "eagle-import:LED3MM")
      (libsource (lib "eagle-import") (part "LED3MM"))
    )
    (comp (ref "LED446")
      (value "LED3MM")
      (footprint "eagle-import:LED3MM")
      (libsource (lib "eagle-import") (part "LED3MM"))
    )
    (comp (ref "LED447")
      (value "LED3MM")
      (footprint "eagle-import:LED3MM")
      (libsource (lib "eagle-import") (part "LED3MM"))
    )
    (comp (ref "LED448")
      (value "LED3MM")
      (footprint "eagle-import:LED3MM")
      (libsource (lib "eagle-import") (part "LED3MM"))
    )
    (comp (ref "LED449")
      (value "LED3MM")
      (footprint "eagle-import:LED3MM")
      (libsource (lib "eagle-import") (part "LED3MM"))
    )
    (comp (ref "LED450")
      (value "LED3MM")
      (footprint "eagle-import:LED3MM")
      (libsource (lib "eagle-import") (part "LED3MM"))
    )
    (comp (ref "LED451")
      (value "LED3MM")
      (footprint "eagle-import:LED3MM")
      (libsource (lib "eagle-import") (part "LED3MM"))
    )
    (comp (ref "LED452")
      (value "LED3MM")
      (footprint "eagle-import:LED3MM")
      (libsource (lib "eagle-import") (part "LED3MM"))
    )
    (comp (ref "LED453")
      (value "LED3MM")
      (footprint "eagle-import:LED3MM")
      (libsource (lib "eagle-import") (part "LED3MM"))
    )
    (comp (ref "LED454")
      (value "LED3MM")
      (footprint "eagle-import:LED3MM")
      (libsource (lib "eagle-import") (part "LED3MM"))
    )
    (comp (ref "LED455")
      (value "LED3MM")
      (footprint "eagle-import:LED3MM")
      (libsource (lib "eagle-import") (part "LED3MM"))
    )
    (comp (ref "LED456")
      (value "LED3MM")
      (footprint "eagle-import:LED3MM")
      (libsource (lib "eagle-import") (part "LED3MM"))
    )
    (comp (ref "LED457")
      (value "LED3MM")
      (footprint "eagle-import:LED3MM")
      (libsource (lib "eagle-import") (part "LED3MM"))
    )
    (comp (ref "LED458")
      (value "LED3MM")
      (footprint "eagle-import:LED3MM")
      (libsource (lib "eagle-import") (part "LED3MM"))
    )
    (comp (ref "LED459")
      (value "LED3MM")
      (footprint "eagle-import:LED3MM")
      (libsource (lib "eagle-import") (part "LED3MM"))
    )
    (comp (ref "LED460")
      (value "LED3MM")
      (footprint "eagle-import:LED3MM")
      (libsource (lib "eagle-import") (part "LED3MM"))
    )
    (comp (ref "LED461")
      (value "LED3MM")
      (footprint "eagle-import:LED3MM")
      (libsource (lib "eagle-import") (part "LED3MM"))
    )
    (comp (ref "LED462")
      (value "LED3MM")
      (footprint "eagle-import:LED3MM")
      (libsource (lib "eagle-import") (part "LED3MM"))
    )
    (comp (ref "LED463")
      (value "LED3MM")
      (footprint "eagle-import:LED3MM")
      (libsource (lib "eagle-import") (part "LED3MM"))
    )
    (comp (ref "LED464")
      (value "LED3MM")
      (footprint "eagle-import:LED3MM")
      (libsource (lib "eagle-import") (part "LED3MM"))
    )
    (comp (ref "LED465")
      (value "LED3MM")
      (footprint "eagle-import:LED3MM")
      (libsource (lib "eagle-import") (part "LED3MM"))
    )
    (comp (ref "LED466")
      (value "LED3MM")
      (footprint "eagle-import:LED3MM")
      (libsource (lib "eagle-import") (part "LED3MM"))
    )
    (comp (ref "LED467")
      (value "LED3MM")
      (footprint "eagle-import:LED3MM")
      (libsource (lib "eagle-import") (part "LED3MM"))
    )
    (comp (ref "LED468")
      (value "LED3MM")
      (footprint "eagle-import:LED3MM")
      (libsource (lib "eagle-import") (part "LED3MM"))
    )
    (comp (ref "LED469")
      (value "LED3MM")
      (footprint "eagle-import:LED3MM")
      (libsource (lib "eagle-import") (part "LED3MM"))
    )
    (comp (ref "LED470")
      (value "LED3MM")
      (footprint "eagle-import:LED3MM")
      (libsource (lib "eagle-import") (part "LED3MM"))
    )
    (comp (ref "LED471")
      (value "LED3MM")
      (footprint "eagle-import:LED3MM")
      (libsource (lib "eagle-import") (part "LED3MM"))
    )
    (comp (ref "LED472")
      (value "LED3MM")
      (footprint "eagle-import:LED3MM")
      (libsource (lib "eagle-import") (part "LED3MM"))
    )
    (comp (ref "LED473")
      (value "LED3MM")
      (footprint "eagle-import:LED3MM")
      (libsource (lib "eagle-import") (part "LED3MM"))
    )
    (comp (ref "LED474")
      (value "LED3MM")
      (footprint "eagle-import:LED3MM")
      (libsource (lib "eagle-import") (part "LED3MM"))
    )
    (comp (ref "LED475")
      (value "LED3MM")
      (footprint "eagle-import:LED3MM")
      (libsource (lib "eagle-import") (part "LED3MM"))
    )
    (comp (ref "LED476")
      (value "LED3MM")
      (footprint "eagle-import:LED3MM")
      (libsource (lib "eagle-import") (part "LED3MM"))
    )
    (comp (ref "LED477")
      (value "LED3MM")
      (footprint "eagle-import:LED3MM")
      (libsource (lib "eagle-import") (part "LED3MM"))
    )
    (comp (ref "LED478")
      (value "LED3MM")
      (footprint "eagle-import:LED3MM")
      (libsource (lib "eagle-import") (part "LED3MM"))
    )
    (comp (ref "LED479")
      (value "LED3MM")
      (footprint "eagle-import:LED3MM")
      (libsource (lib "eagle-import") (part "LED3MM"))
    )
    (comp (ref "LED480")
      (value "LED3MM")
      (footprint "eagle-import:LED3MM")
      (libsource (lib "eagle-import") (part "LED3MM"))
    )
    (comp (ref "LED481")
      (value "LED3MM")
      (footprint "eagle-import:LED3MM")
      (libsource (lib "eagle-import") (part "LED3MM"))
    )
    (comp (ref "LED482")
      (value "LED3MM")
      (footprint "eagle-import:LED3MM")
      (libsource (lib "eagle-import") (part "LED3MM"))
    )
    (comp (ref "LED483")
      (value "LED3MM")
      (footprint "eagle-import:LED3MM")
      (libsource (lib "eagle-import") (part "LED3MM"))
    )
    (comp (ref "LED484")
      (value "LED3MM")
      (footprint "eagle-import:LED3MM")
      (libsource (lib "eagle-import") (part "LED3MM"))
    )
    (comp (ref "LED485")
      (value "LED3MM")
      (footprint "eagle-import:LED3MM")
      (libsource (lib "eagle-import") (part "LED3MM"))
    )
    (comp (ref "LED486")
      (value "LED3MM")
      (footprint "eagle-import:LED3MM")
      (libsource (lib "eagle-import") (part "LED3MM"))
    )
    (comp (ref "LED487")
      (value "LED3MM")
      (footprint "eagle-import:LED3MM")
      (libsource (lib "eagle-import") (part "LED3MM"))
    )
    (comp (ref "LED488")
      (value "LED3MM")
      (footprint "eagle-import:LED3MM")
      (libsource (lib "eagle-import") (part "LED3MM"))
    )
    (comp (ref "LED489")
      (value "LED3MM")
      (footprint "eagle-import:LED3MM")
      (libsource (lib "eagle-import") (part "LED3MM"))
    )
    (comp (ref "LED490")
      (value "LED3MM")
      (footprint "eagle-import:LED3MM")
      (libsource (lib "eagle-import") (part "LED3MM"))
    )
    (comp (ref "LED491")
      (value "LED3MM")
      (footprint "eagle-import:LED3MM")
      (libsource (lib "eagle-import") (part "LED3MM"))
    )
    (comp (ref "LED492")
      (value "LED3MM")
      (footprint "eagle-import:LED3MM")
      (libsource (lib "eagle-import") (part "LED3MM"))
    )
    (comp (ref "LED493")
      (value "LED3MM")
      (footprint "eagle-import:LED3MM")
      (libsource (lib "eagle-import") (part "LED3MM"))
    )
    (comp (ref "LED494")
      (value "LED3MM")
      (footprint "eagle-import:LED3MM")
      (libsource (lib "eagle-import") (part "LED3MM"))
    )
    (comp (ref "LED495")
      (value "LED3MM")
      (footprint "eagle-import:LED3MM")
      (libsource (lib "eagle-import") (part "LED3MM"))
    )
    (comp (ref "LED496")
      (value "LED3MM")
      (footprint "eagle-import:LED3MM")
      (libsource (lib "eagle-import") (part "LED3MM"))
    )
    (comp (ref "LED497")
      (value "LED3MM")
      (footprint "eagle-import:LED3MM")
      (libsource (lib "eagle-import") (part "LED3MM"))
    )
    (comp (ref "LED498")
      (value "LED3MM")
      (footprint "eagle-import:LED3MM")
      (libsource (lib "eagle-import") (part "LED3MM"))
    )
    (comp (ref "LED499")
      (value "LED3MM")
      (footprint "eagle-import:LED3MM")
      (libsource (lib "eagle-import") (part "LED3MM"))
    )
    (comp (ref "LED500")
      (value "LED3MM")
      (footprint "eagle-import:LED3MM")
      (libsource (lib "eagle-import") (part "LED3MM"))
    )
    (comp (ref "LED501")
      (value "LED3MM")
      (footprint "eagle-import:LED3MM")
      (libsource (lib "eagle-import") (part "LED3MM"))
    )
    (comp (ref "LED502")
      (value "LED3MM")
      (footprint "eagle-import:LED3MM")
      (libsource (lib "eagle-import") (part "LED3MM"))
    )
    (comp (ref "LED503")
      (value "LED3MM")
      (footprint "eagle-import:LED3MM")
      (libsource (lib "eagle-import") (part "LED3MM"))
    )
    (comp (ref "LED504")
      (value "LED3MM")
      (footprint "eagle-import:LED3MM")
      (libsource (lib "eagle-import") (part "LED3MM"))
    )
    (comp (ref "LED505")
      (value "LED3MM")
      (footprint "eagle-import:LED3MM")
      (libsource (lib "eagle-import") (part "LED3MM"))
    )
    (comp (ref "LED506")
      (value "LED3MM")
      (footprint "eagle-import:LED3MM")
      (libsource (lib "eagle-import") (part "LED3MM"))
    )
    (comp (ref "LED507")
      (value "LED3MM")
      (footprint "eagle-import:LED3MM")
      (libsource (lib "eagle-import") (part "LED3MM"))
    )
    (comp (ref "LED508")
      (value "LED3MM")
      (footprint "eagle-import:LED3MM")
      (libsource (lib "eagle-import") (part "LED3MM"))
    )
    (comp (ref "LED509")
      (value "LED3MM")
      (footprint "eagle-import:LED3MM")
      (libsource (lib "eagle-import") (part "LED3MM"))
    )
    (comp (ref "LED510")
      (value "LED3MM")
      (footprint "eagle-import:LED3MM")
      (libsource (lib "eagle-import") (part "LED3MM"))
    )
    (comp (ref "LED511")
      (value "LED3MM")
      (footprint "eagle-import:LED3MM")
      (libsource (lib "eagle-import") (part "LED3MM"))
    )
    (comp (ref "LED512")
      (value "LED3MM")
      (footprint "eagle-import:LED3MM")
      (libsource (lib "eagle-import") (part "LED3MM"))
    )
    (comp (ref "LED513")
      (value "LED3MM")
      (footprint "eagle-import:LED3MM")
      (libsource (lib "eagle-import") (part "LED3MM"))
    )
    (comp (ref "LED514")
      (value "LED3MM")
      (footprint "eagle-import:LED3MM")
      (libsource (lib "eagle-import") (part "LED3MM"))
    )
    (comp (ref "LED515")
      (value "LED3MM")
      (footprint "eagle-import:LED3MM")
      (libsource (lib "eagle-import") (part "LED3MM"))
    )
    (comp (ref "LED516")
      (value "LED3MM")
      (footprint "eagle-import:LED3MM")
      (libsource (lib "eagle-import") (part "LED3MM"))
    )
    (comp (ref "LED517")
      (value "LED3MM")
      (footprint "eagle-import:LED3MM")
      (libsource (lib "eagle-import") (part "LED3MM"))
    )
    (comp (ref "LED518")
      (value "LED3MM")
      (footprint "eagle-import:LED3MM")
      (libsource (lib "eagle-import") (part "LED3MM"))
    )
    (comp (ref "LED519")
      (value "LED3MM")
      (footprint "eagle-import:LED3MM")
      (libsource (lib "eagle-import") (part "LED3MM"))
    )
    (comp (ref "LED520")
      (value "LED3MM")
      (footprint "eagle-import:LED3MM")
      (libsource (lib "eagle-import") (part "LED3MM"))
    )
    (comp (ref "LED521")
      (value "LED3MM")
      (footprint "eagle-import:LED3MM")
      (libsource (lib "eagle-import") (part "LED3MM"))
    )
    (comp (ref "LED522")
      (value "LED3MM")
      (footprint "eagle-import:LED3MM")
      (libsource (lib "eagle-import") (part "LED3MM"))
    )
    (comp (ref "LED523")
      (value "LED3MM")
      (footprint "eagle-import:LED3MM")
      (libsource (lib "eagle-import") (part "LED3MM"))
    )
    (comp (ref "LED524")
      (value "LED3MM")
      (footprint "eagle-import:LED3MM")
      (libsource (lib "eagle-import") (part "LED3MM"))
    )
    (comp (ref "LED525")
      (value "LED3MM")
      (footprint "eagle-import:LED3MM")
      (libsource (lib "eagle-import") (part "LED3MM"))
    )
    (comp (ref "LED526")
      (value "LED3MM")
      (footprint "eagle-import:LED3MM")
      (libsource (lib "eagle-import") (part "LED3MM"))
    )
    (comp (ref "LED527")
      (value "LED3MM")
      (footprint "eagle-import:LED3MM")
      (libsource (lib "eagle-import") (part "LED3MM"))
    )
    (comp (ref "LED528")
      (value "LED3MM")
      (footprint "eagle-import:LED3MM")
      (libsource (lib "eagle-import") (part "LED3MM"))
    )
    (comp (ref "LED529")
      (value "LED3MM")
      (footprint "eagle-import:LED3MM")
      (libsource (lib "eagle-import") (part "LED3MM"))
    )
    (comp (ref "LED530")
      (value "LED3MM")
      (footprint "eagle-import:LED3MM")
      (libsource (lib "eagle-import") (part "LED3MM"))
    )
    (comp (ref "LED531")
      (value "LED3MM")
      (footprint "eagle-import:LED3MM")
      (libsource (lib "eagle-import") (part "LED3MM"))
    )
    (comp (ref "LED532")
      (value "LED3MM")
      (footprint "eagle-import:LED3MM")
      (libsource (lib "eagle-import") (part "LED3MM"))
    )
    (comp (ref "LED533")
      (value "LED3MM")
      (footprint "eagle-import:LED3MM")
      (libsource (lib "eagle-import") (part "LED3MM"))
    )
    (comp (ref "LED534")
      (value "LED3MM")
      (footprint "eagle-import:LED3MM")
      (libsource (lib "eagle-import") (part "LED3MM"))
    )
    (comp (ref "LED535")
      (value "LED3MM")
      (footprint "eagle-import:LED3MM")
      (libsource (lib "eagle-import") (part "LED3MM"))
    )
    (comp (ref "LED536")
      (value "LED3MM")
      (footprint "eagle-import:LED3MM")
      (libsource (lib "eagle-import") (part "LED3MM"))
    )
    (comp (ref "LED537")
      (value "LED3MM")
      (footprint "eagle-import:LED3MM")
      (libsource (lib "eagle-import") (part "LED3MM"))
    )
    (comp (ref "LED538")
      (value "LED3MM")
      (footprint "eagle-import:LED3MM")
      (libsource (lib "eagle-import") (part "LED3MM"))
    )
    (comp (ref "LED539")
      (value "LED3MM")
      (footprint "eagle-import:LED3MM")
      (libsource (lib "eagle-import") (part "LED3MM"))
    )
    (comp (ref "LED540")
      (value "LED3MM")
      (footprint "eagle-import:LED3MM")
      (libsource (lib "eagle-import") (part "LED3MM"))
    )
    (comp (ref "LED541")
      (value "LED3MM")
      (footprint "eagle-import:LED3MM")
      (libsource (lib "eagle-import") (part "LED3MM"))
    )
    (comp (ref "LED542")
      (value "LED3MM")
      (footprint "eagle-import:LED3MM")
      (libsource (lib "eagle-import") (part "LED3MM"))
    )
    (comp (ref "LED543")
      (value "LED3MM")
      (footprint "eagle-import:LED3MM")
      (libsource (lib "eagle-import") (part "LED3MM"))
    )
    (comp (ref "LED544")
      (value "LED3MM")
      (footprint "eagle-import:LED3MM")
      (libsource (lib "eagle-import") (part "LED3MM"))
    )
    (comp (ref "LED545")
      (value "LED3MM")
      (footprint "eagle-import:LED3MM")
      (libsource (lib "eagle-import") (part "LED3MM"))
    )
    (comp (ref "LED546")
      (value "LED3MM")
      (footprint "eagle-import:LED3MM")
      (libsource (lib "eagle-import") (part "LED3MM"))
    )
    (comp (ref "LED547")
      (value "LED3MM")
      (footprint "eagle-import:LED3MM")
      (libsource (lib "eagle-import") (part "LED3MM"))
    )
    (comp (ref "LED548")
      (value "LED3MM")
      (footprint "eagle-import:LED3MM")
      (libsource (lib "eagle-import") (part "LED3MM"))
    )
    (comp (ref "LED549")
      (value "LED3MM")
      (footprint "eagle-import:LED3MM")
      (libsource (lib "eagle-import") (part "LED3MM"))
    )
    (comp (ref "LED550")
      (value "LED3MM")
      (footprint "eagle-import:LED3MM")
      (libsource (lib "eagle-import") (part "LED3MM"))
    )
    (comp (ref "LED551")
      (value "LED3MM")
      (footprint "eagle-import:LED3MM")
      (libsource (lib "eagle-import") (part "LED3MM"))
    )
    (comp (ref "LED552")
      (value "LED3MM")
      (footprint "eagle-import:LED3MM")
      (libsource (lib "eagle-import") (part "LED3MM"))
    )
    (comp (ref "LED553")
      (value "LED3MM")
      (footprint "eagle-import:LED3MM")
      (libsource (lib "eagle-import") (part "LED3MM"))
    )
    (comp (ref "LED554")
      (value "LED3MM")
      (footprint "eagle-import:LED3MM")
      (libsource (lib "eagle-import") (part "LED3MM"))
    )
    (comp (ref "LED555")
      (value "LED3MM")
      (footprint "eagle-import:LED3MM")
      (libsource (lib "eagle-import") (part "LED3MM"))
    )
    (comp (ref "LED556")
      (value "LED3MM")
      (footprint "eagle-import:LED3MM")
      (libsource (lib "eagle-import") (part "LED3MM"))
    )
    (comp (ref "LED557")
      (value "LED3MM")
      (footprint "eagle-import:LED3MM")
      (libsource (lib "eagle-import") (part "LED3MM"))
    )
    (comp (ref "LED558")
      (value "LED3MM")
      (footprint "eagle-import:LED3MM")
      (libsource (lib "eagle-import") (part "LED3MM"))
    )
    (comp (ref "LED559")
      (value "LED3MM")
      (footprint "eagle-import:LED3MM")
      (libsource (lib "eagle-import") (part "LED3MM"))
    )
    (comp (ref "LED560")
      (value "LED3MM")
      (footprint "eagle-import:LED3MM")
      (libsource (lib "eagle-import") (part "LED3MM"))
    )
    (comp (ref "LED561")
      (value "LED3MM")
      (footprint "eagle-import:LED3MM")
      (libsource (lib "eagle-import") (part "LED3MM"))
    )
    (comp (ref "LED562")
      (value "LED3MM")
      (footprint "eagle-import:LED3MM")
      (libsource (lib "eagle-import") (part "LED3MM"))
    )
    (comp (ref "LED563")
      (value "LED3MM")
      (footprint "eagle-import:LED3MM")
      (libsource (lib "eagle-import") (part "LED3MM"))
    )
    (comp (ref "LED564")
      (value "LED3MM")
      (footprint "eagle-import:LED3MM")
      (libsource (lib "eagle-import") (part "LED3MM"))
    )
    (comp (ref "LED565")
      (value "LED3MM")
      (footprint "eagle-import:LED3MM")
      (libsource (lib "eagle-import") (part "LED3MM"))
    )
    (comp (ref "LED566")
      (value "LED3MM")
      (footprint "eagle-import:LED3MM")
      (libsource (lib "eagle-import") (part "LED3MM"))
    )
    (comp (ref "LED567")
      (value "LED3MM")
      (footprint "eagle-import:LED3MM")
      (libsource (lib "eagle-import") (part "LED3MM"))
    )
    (comp (ref "LED568")
      (value "LED3MM")
      (footprint "eagle-import:LED3MM")
      (libsource (lib "eagle-import") (part "LED3MM"))
    )
    (comp (ref "LED569")
      (value "LED3MM")
      (footprint "eagle-import:LED3MM")
      (libsource (lib "eagle-import") (part "LED3MM"))
    )
    (comp (ref "LED570")
      (value "LED3MM")
      (footprint "eagle-import:LED3MM")
      (libsource (lib "eagle-import") (part "LED3MM"))
    )
    (comp (ref "LED571")
      (value "LED3MM")
      (footprint "eagle-import:LED3MM")
      (libsource (lib "eagle-import") (part "LED3MM"))
    )
    (comp (ref "LED572")
      (value "LED3MM")
      (footprint "eagle-import:LED3MM")
      (libsource (lib "eagle-import") (part "LED3MM"))
    )
    (comp (ref "LED573")
      (value "LED3MM")
      (footprint "eagle-import:LED3MM")
      (libsource (lib "eagle-import") (part "LED3MM"))
    )
    (comp (ref "LED574")
      (value "LED3MM")
      (footprint "eagle-import:LED3MM")
      (libsource (lib "eagle-import") (part "LED3MM"))
    )
    (comp (ref "LED575")
      (value "LED3MM")
      (footprint "eagle-import:LED3MM")
      (libsource (lib "eagle-import") (part "LED3MM"))
    )
    (comp (ref "LED576")
      (value "LED3MM")
      (footprint "eagle-import:LED3MM")
      (libsource (lib "eagle-import") (part "LED3MM"))
    )
    (comp (ref "LED577")
      (value "LED3MM")
      (footprint "eagle-import:LED3MM")
      (libsource (lib "eagle-import") (part "LED3MM"))
    )
    (comp (ref "LED578")
      (value "LED3MM")
      (footprint "eagle-import:LED3MM")
      (libsource (lib "eagle-import") (part "LED3MM"))
    )
    (comp (ref "LED579")
      (value "LED3MM")
      (footprint "eagle-import:LED3MM")
      (libsource (lib "eagle-import") (part "LED3MM"))
    )
    (comp (ref "LED580")
      (value "LED3MM")
      (footprint "eagle-import:LED3MM")
      (libsource (lib "eagle-import") (part "LED3MM"))
    )
    (comp (ref "LED581")
      (value "LED3MM")
      (footprint "eagle-import:LED3MM")
      (libsource (lib "eagle-import") (part "LED3MM"))
    )
    (comp (ref "LED582")
      (value "LED3MM")
      (footprint "eagle-import:LED3MM")
      (libsource (lib "eagle-import") (part "LED3MM"))
    )
    (comp (ref "LED583")
      (value "LED3MM")
      (footprint "eagle-import:LED3MM")
      (libsource (lib "eagle-import") (part "LED3MM"))
    )
    (comp (ref "LED584")
      (value "LED3MM")
      (footprint "eagle-import:LED3MM")
      (libsource (lib "eagle-import") (part "LED3MM"))
    )
    (comp (ref "LED585")
      (value "LED3MM")
      (footprint "eagle-import:LED3MM")
      (libsource (lib "eagle-import") (part "LED3MM"))
    )
    (comp (ref "LED586")
      (value "LED3MM")
      (footprint "eagle-import:LED3MM")
      (libsource (lib "eagle-import") (part "LED3MM"))
    )
    (comp (ref "LED587")
      (value "LED3MM")
      (footprint "eagle-import:LED3MM")
      (libsource (lib "eagle-import") (part "LED3MM"))
    )
    (comp (ref "LED588")
      (value "LED3MM")
      (footprint "eagle-import:LED3MM")
      (libsource (lib "eagle-import") (part "LED3MM"))
    )
    (comp (ref "LED589")
      (value "LED3MM")
      (footprint "eagle-import:LED3MM")
      (libsource (lib "eagle-import") (part "LED3MM"))
    )
    (comp (ref "LED590")
      (value "LED3MM")
      (footprint "eagle-import:LED3MM")
      (libsource (lib "eagle-import") (part "LED3MM"))
    )
    (comp (ref "LED591")
      (value "LED3MM")
      (footprint "eagle-import:LED3MM")
      (libsource (lib "eagle-import") (part "LED3MM"))
    )
    (comp (ref "LED592")
      (value "LED3MM")
      (footprint "eagle-import:LED3MM")
      (libsource (lib "eagle-import") (part "LED3MM"))
    )
    (comp (ref "LED593")
      (value "LED3MM")
      (footprint "eagle-import:LED3MM")
      (libsource (lib "eagle-import") (part "LED3MM"))
    )
    (comp (ref "LED594")
      (value "LED3MM")
      (footprint "eagle-import:LED3MM")
      (libsource (lib "eagle-import") (part "LED3MM"))
    )
    (comp (ref "LED595")
      (value "LED3MM")
      (footprint "eagle-import:LED3MM")
      (libsource (lib "eagle-import") (part "LED3MM"))
    )
    (comp (ref "LED596")
      (value "LED3MM")
      (footprint "eagle-import:LED3MM")
      (libsource (lib "eagle-import") (part "LED3MM"))
    )
    (comp (ref "LED597")
      (value "LED3MM")
      (footprint "eagle-import:LED3MM")
      (libsource (lib "eagle-import") (part "LED3MM"))
    )
    (comp (ref "LED598")
      (value "LED3MM")
      (footprint "eagle-import:LED3MM")
      (libsource (lib "eagle-import") (part "LED3MM"))
    )
    (comp (ref "LED599")
      (value "LED3MM")
      (footprint "eagle-import:LED3MM")
      (libsource (lib "eagle-import") (part "LED3MM"))
    )
    (comp (ref "LED600")
      (value "LED3MM")
      (footprint "eagle-import:LED3MM")
      (libsource (lib "eagle-import") (part "LED3MM"))
    )
    (comp (ref "LED601")
      (value "LED3MM")
      (footprint "eagle-import:LED3MM")
      (libsource (lib "eagle-import") (part "LED3MM"))
    )
    (comp (ref "LED602")
      (value "LED3MM")
      (footprint "eagle-import:LED3MM")
      (libsource (lib "eagle-import") (part "LED3MM"))
    )
    (comp (ref "LED603")
      (value "LED3MM")
      (footprint "eagle-import:LED3MM")
      (libsource (lib "eagle-import") (part "LED3MM"))
    )
    (comp (ref "LED604")
      (value "LED3MM")
      (footprint "eagle-import:LED3MM")
      (libsource (lib "eagle-import") (part "LED3MM"))
    )
    (comp (ref "LED605")
      (value "LED3MM")
      (footprint "eagle-import:LED3MM")
      (libsource (lib "eagle-import") (part "LED3MM"))
    )
    (comp (ref "LED606")
      (value "LED3MM")
      (footprint "eagle-import:LED3MM")
      (libsource (lib "eagle-import") (part "LED3MM"))
    )
    (comp (ref "LED607")
      (value "LED3MM")
      (footprint "eagle-import:LED3MM")
      (libsource (lib "eagle-import") (part "LED3MM"))
    )
    (comp (ref "LED608")
      (value "LED3MM")
      (footprint "eagle-import:LED3MM")
      (libsource (lib "eagle-import") (part "LED3MM"))
    )
    (comp (ref "LED609")
      (value "LED3MM")
      (footprint "eagle-import:LED3MM")
      (libsource (lib "eagle-import") (part "LED3MM"))
    )
    (comp (ref "LED610")
      (value "LED3MM")
      (footprint "eagle-import:LED3MM")
      (libsource (lib "eagle-import") (part "LED3MM"))
    )
    (comp (ref "LED611")
      (value "LED3MM")
      (footprint "eagle-import:LED3MM")
      (libsource (lib "eagle-import") (part "LED3MM"))
    )
    (comp (ref "LED612")
      (value "LED3MM")
      (footprint "eagle-import:LED3MM")
      (libsource (lib "eagle-import") (part "LED3MM"))
    )
    (comp (ref "LED613")
      (value "LED3MM")
      (footprint "eagle-import:LED3MM")
      (libsource (lib "eagle-import") (part "LED3MM"))
    )
    (comp (ref "LED614")
      (value "LED3MM")
      (footprint "eagle-import:LED3MM")
      (libsource (lib "eagle-import") (part "LED3MM"))
    )
    (comp (ref "LED615")
      (value "LED3MM")
      (footprint "eagle-import:LED3MM")
      (libsource (lib "eagle-import") (part "LED3MM"))
    )
    (comp (ref "LED616")
      (value "LED3MM")
      (footprint "eagle-import:LED3MM")
      (libsource (lib "eagle-import") (part "LED3MM"))
    )
    (comp (ref "LED617")
      (value "LED3MM")
      (footprint "eagle-import:LED3MM")
      (libsource (lib "eagle-import") (part "LED3MM"))
    )
    (comp (ref "LED618")
      (value "LED3MM")
      (footprint "eagle-import:LED3MM")
      (libsource (lib "eagle-import") (part "LED3MM"))
    )
    (comp (ref "LED619")
      (value "LED3MM")
      (footprint "eagle-import:LED3MM")
      (libsource (lib "eagle-import") (part "LED3MM"))
    )
    (comp (ref "LED620")
      (value "LED3MM")
      (footprint "eagle-import:LED3MM")
      (libsource (lib "eagle-import") (part "LED3MM"))
    )
    (comp (ref "LED621")
      (value "LED3MM")
      (footprint "eagle-import:LED3MM")
      (libsource (lib "eagle-import") (part "LED3MM"))
    )
    (comp (ref "LED622")
      (value "LED3MM")
      (footprint "eagle-import:LED3MM")
      (libsource (lib "eagle-import") (part "LED3MM"))
    )
    (comp (ref "LED623")
      (value "LED3MM")
      (footprint "eagle-import:LED3MM")
      (libsource (lib "eagle-import") (part "LED3MM"))
    )
    (comp (ref "LED624")
      (value "LED3MM")
      (footprint "eagle-import:LED3MM")
      (libsource (lib "eagle-import") (part "LED3MM"))
    )
    (comp (ref "LED625")
      (value "LED3MM")
      (footprint "eagle-import:LED3MM")
      (libsource (lib "eagle-import") (part "LED3MM"))
    )
    (comp (ref "LED626")
      (value "LED3MM")
      (footprint "eagle-import:LED3MM")
      (libsource (lib "eagle-import") (part "LED3MM"))
    )
    (comp (ref "LED627")
      (value "LED3MM")
      (footprint "eagle-import:LED3MM")
      (libsource (lib "eagle-import") (part "LED3MM"))
    )
    (comp (ref "LED628")
      (value "LED3MM")
      (footprint "eagle-import:LED3MM")
      (libsource (lib "eagle-import") (part "LED3MM"))
    )
    (comp (ref "LED629")
      (value "LED3MM")
      (footprint "eagle-import:LED3MM")
      (libsource (lib "eagle-import") (part "LED3MM"))
    )
    (comp (ref "LED630")
      (value "LED3MM")
      (footprint "eagle-import:LED3MM")
      (libsource (lib "eagle-import") (part "LED3MM"))
    )
    (comp (ref "LED631")
      (value "LED3MM")
      (footprint "eagle-import:LED3MM")
      (libsource (lib "eagle-import") (part "LED3MM"))
    )
    (comp (ref "LED632")
      (value "LED3MM")
      (footprint "eagle-import:LED3MM")
      (libsource (lib "eagle-import") (part "LED3MM"))
    )
    (comp (ref "LED633")
      (value "LED3MM")
      (footprint "eagle-import:LED3MM")
      (libsource (lib "eagle-import") (part "LED3MM"))
    )
    (comp (ref "LED634")
      (value "LED3MM")
      (footprint "eagle-import:LED3MM")
      (libsource (lib "eagle-import") (part "LED3MM"))
    )
    (comp (ref "LED635")
      (value "LED3MM")
      (footprint "eagle-import:LED3MM")
      (libsource (lib "eagle-import") (part "LED3MM"))
    )
    (comp (ref "LED636")
      (value "LED3MM")
      (footprint "eagle-import:LED3MM")
      (libsource (lib "eagle-import") (part "LED3MM"))
    )
    (comp (ref "LED637")
      (value "LED3MM")
      (footprint "eagle-import:LED3MM")
      (libsource (lib "eagle-import") (part "LED3MM"))
    )
    (comp (ref "LED638")
      (value "LED3MM")
      (footprint "eagle-import:LED3MM")
      (libsource (lib "eagle-import") (part "LED3MM"))
    )
    (comp (ref "LED639")
      (value "LED3MM")
      (footprint "eagle-import:LED3MM")
      (libsource (lib "eagle-import") (part "LED3MM"))
    )
    (comp (ref "LED640")
      (value "LED3MM")
      (footprint "eagle-import:LED3MM")
      (libsource (lib "eagle-import") (part "LED3MM"))
    )
    (comp (ref "R1")
      (value "1K")
      (footprint "eagle-import:R0805W")
      (libsource (lib "eagle-import") (part "R-EU_R0805W"))
    )
    (comp (ref "R2")
      (value "220")
      (footprint "eagle-import:R0805W")
      (libsource (lib "eagle-import") (part "R-EU_R0805W"))
    )
    (comp (ref "R3")
      (value "220")
      (footprint "eagle-import:R0805W")
      (libsource (lib "eagle-import") (part "R-EU_R0805W"))
    )
    (comp (ref "R4")
      (value "1K")
      (footprint "eagle-import:R0805W")
      (libsource (lib "eagle-import") (part "R-EU_R0805W"))
    )
    (comp (ref "R5")
      (value "1K")
      (footprint "eagle-import:R0805W")
      (libsource (lib "eagle-import") (part "R-EU_R0805W"))
    )
    (comp (ref "R6")
      (value "1K")
      (footprint "eagle-import:R0805W")
      (libsource (lib "eagle-import") (part "R-EU_R0805W"))
    )
    (comp (ref "R7")
      (value "1K")
      (footprint "eagle-import:R0805W")
      (libsource (lib "eagle-import") (part "R-EU_R0805W"))
    )
    (comp (ref "R8")
      (value "1K")
      (footprint "eagle-import:R0805W")
      (libsource (lib "eagle-import") (part "R-EU_R0805W"))
    )
    (comp (ref "R9")
      (value "1K")
      (footprint "eagle-import:R0805W")
      (libsource (lib "eagle-import") (part "R-EU_R0805W"))
    )
    (comp (ref "R10")
      (value "1K")
      (footprint "eagle-import:R0805W")
      (libsource (lib "eagle-import") (part "R-EU_R0805W"))
    )
    (comp (ref "R11")
      (value "1K")
      (footprint "eagle-import:R0805W")
      (libsource (lib "eagle-import") (part "R-EU_R0805W"))
    )
    (comp (ref "R12")
      (value "1K")
      (footprint "eagle-import:R0805W")
      (libsource (lib "eagle-import") (part "R-EU_R0805W"))
    )
    (comp (ref "R13")
      (value "1K")
      (footprint "eagle-import:R0805W")
      (libsource (lib "eagle-import") (part "R-EU_R0805W"))
    )
    (comp (ref "R14")
      (value "1K")
      (footprint "eagle-import:R0805W")
      (libsource (lib "eagle-import") (part "R-EU_R0805W"))
    )
    (comp (ref "R15")
      (value "1K")
      (footprint "eagle-import:R0805W")
      (libsource (lib "eagle-import") (part "R-EU_R0805W"))
    )
    (comp (ref "R16")
      (value "1K")
      (footprint "eagle-import:R0805W")
      (libsource (lib "eagle-import") (part "R-EU_R0805W"))
    )
    (comp (ref "R17")
      (value "1K")
      (footprint "eagle-import:R0805W")
      (libsource (lib "eagle-import") (part "R-EU_R0805W"))
    )
    (comp (ref "R18")
      (value "1K")
      (footprint "eagle-import:R0805W")
      (libsource (lib "eagle-import") (part "R-EU_R0805W"))
    )
    (comp (ref "R19")
      (value "220")
      (footprint "eagle-import:R0805W")
      (libsource (lib "eagle-import") (part "R-EU_R0805W"))
    )
    (comp (ref "R20")
      (value "220")
      (footprint "eagle-import:R0805W")
      (libsource (lib "eagle-import") (part "R-EU_R0805W"))
    )
    (comp (ref "R21")
      (value "220")
      (footprint "eagle-import:R0805W")
      (libsource (lib "eagle-import") (part "R-EU_R0805W"))
    )
    (comp (ref "R22")
      (value "220")
      (footprint "eagle-import:R0805W")
      (libsource (lib "eagle-import") (part "R-EU_R0805W"))
    )
    (comp (ref "R23")
      (value "220")
      (footprint "eagle-import:R0805W")
      (libsource (lib "eagle-import") (part "R-EU_R0805W"))
    )
    (comp (ref "R24")
      (value "220")
      (footprint "eagle-import:R0805W")
      (libsource (lib "eagle-import") (part "R-EU_R0805W"))
    )
    (comp (ref "R25")
      (value "220")
      (footprint "eagle-import:R0805W")
      (libsource (lib "eagle-import") (part "R-EU_R0805W"))
    )
    (comp (ref "R26")
      (value "220")
      (footprint "eagle-import:R0805W")
      (libsource (lib "eagle-import") (part "R-EU_R0805W"))
    )
    (comp (ref "R27")
      (value "220")
      (footprint "eagle-import:R0805W")
      (libsource (lib "eagle-import") (part "R-EU_R0805W"))
    )
    (comp (ref "R28")
      (value "220")
      (footprint "eagle-import:R0805W")
      (libsource (lib "eagle-import") (part "R-EU_R0805W"))
    )
    (comp (ref "R29")
      (value "220")
      (footprint "eagle-import:R0805W")
      (libsource (lib "eagle-import") (part "R-EU_R0805W"))
    )
    (comp (ref "R30")
      (value "220")
      (footprint "eagle-import:R0805W")
      (libsource (lib "eagle-import") (part "R-EU_R0805W"))
    )
    (comp (ref "R31")
      (value "220")
      (footprint "eagle-import:R0805W")
      (libsource (lib "eagle-import") (part "R-EU_R0805W"))
    )
    (comp (ref "R32")
      (value "220")
      (footprint "eagle-import:R0805W")
      (libsource (lib "eagle-import") (part "R-EU_R0805W"))
    )
    (comp (ref "R33")
      (value "220")
      (footprint "eagle-import:R0805W")
      (libsource (lib "eagle-import") (part "R-EU_R0805W"))
    )
    (comp (ref "R34")
      (value "220")
      (footprint "eagle-import:R0805W")
      (libsource (lib "eagle-import") (part "R-EU_R0805W"))
    )
    (comp (ref "R35")
      (value "220")
      (footprint "eagle-import:R0805W")
      (libsource (lib "eagle-import") (part "R-EU_R0805W"))
    )
    (comp (ref "R36")
      (value "220")
      (footprint "eagle-import:R0805W")
      (libsource (lib "eagle-import") (part "R-EU_R0805W"))
    )
    (comp (ref "R37")
      (value "220")
      (footprint "eagle-import:R0805W")
      (libsource (lib "eagle-import") (part "R-EU_R0805W"))
    )
    (comp (ref "R38")
      (value "220")
      (footprint "eagle-import:R0805W")
      (libsource (lib "eagle-import") (part "R-EU_R0805W"))
    )
    (comp (ref "R39")
      (value "220")
      (footprint "eagle-import:R0805W")
      (libsource (lib "eagle-import") (part "R-EU_R0805W"))
    )
    (comp (ref "R40")
      (value "220")
      (footprint "eagle-import:R0805W")
      (libsource (lib "eagle-import") (part "R-EU_R0805W"))
    )
    (comp (ref "R41")
      (value "220")
      (footprint "eagle-import:R0805W")
      (libsource (lib "eagle-import") (part "R-EU_R0805W"))
    )
    (comp (ref "R42")
      (value "220")
      (footprint "eagle-import:R0805W")
      (libsource (lib "eagle-import") (part "R-EU_R0805W"))
    )
    (comp (ref "R43")
      (value "220")
      (footprint "eagle-import:R0805W")
      (libsource (lib "eagle-import") (part "R-EU_R0805W"))
    )
    (comp (ref "R44")
      (value "220")
      (footprint "eagle-import:R0805W")
      (libsource (lib "eagle-import") (part "R-EU_R0805W"))
    )
    (comp (ref "R45")
      (value "220")
      (footprint "eagle-import:R0805W")
      (libsource (lib "eagle-import") (part "R-EU_R0805W"))
    )
    (comp (ref "R46")
      (value "220")
      (footprint "eagle-import:R0805W")
      (libsource (lib "eagle-import") (part "R-EU_R0805W"))
    )
    (comp (ref "R47")
      (value "220")
      (footprint "eagle-import:R0805W")
      (libsource (lib "eagle-import") (part "R-EU_R0805W"))
    )
    (comp (ref "R48")
      (value "220")
      (footprint "eagle-import:R0805W")
      (libsource (lib "eagle-import") (part "R-EU_R0805W"))
    )
    (comp (ref "R49")
      (value "220")
      (footprint "eagle-import:R0805W")
      (libsource (lib "eagle-import") (part "R-EU_R0805W"))
    )
    (comp (ref "R50")
      (value "220")
      (footprint "eagle-import:R0805W")
      (libsource (lib "eagle-import") (part "R-EU_R0805W"))
    )
    (comp (ref "R51")
      (value "220")
      (footprint "eagle-import:R0805W")
      (libsource (lib "eagle-import") (part "R-EU_R0805W"))
    )
    (comp (ref "R52")
      (value "220")
      (footprint "eagle-import:R0805W")
      (libsource (lib "eagle-import") (part "R-EU_R0805W"))
    )
    (comp (ref "R53")
      (value "220")
      (footprint "eagle-import:R0805W")
      (libsource (lib "eagle-import") (part "R-EU_R0805W"))
    )
    (comp (ref "R54")
      (value "220")
      (footprint "eagle-import:R0805W")
      (libsource (lib "eagle-import") (part "R-EU_R0805W"))
    )
    (comp (ref "R55")
      (value "220")
      (footprint "eagle-import:R0805W")
      (libsource (lib "eagle-import") (part "R-EU_R0805W"))
    )
    (comp (ref "R56")
      (value "220")
      (footprint "eagle-import:R0805W")
      (libsource (lib "eagle-import") (part "R-EU_R0805W"))
    )
    (comp (ref "R57")
      (value "1K")
      (footprint "eagle-import:R0805W")
      (libsource (lib "eagle-import") (part "R-EU_R0805W"))
    )
    (comp (ref "R58")
      (value "1K")
      (footprint "eagle-import:R0805W")
      (libsource (lib "eagle-import") (part "R-EU_R0805W"))
    )
    (comp (ref "R59")
      (value "1K")
      (footprint "eagle-import:R0805W")
      (libsource (lib "eagle-import") (part "R-EU_R0805W"))
    )
    (comp (ref "R60")
      (value "10K")
      (footprint "eagle-import:R0805W")
      (libsource (lib "eagle-import") (part "R-EU_R0805W"))
    )
    (comp (ref "R61")
      (value "10K")
      (footprint "eagle-import:R0805W")
      (libsource (lib "eagle-import") (part "R-EU_R0805W"))
    )
    (comp (ref "R62")
      (value "1K")
      (footprint "eagle-import:R0805W")
      (libsource (lib "eagle-import") (part "R-EU_R0805W"))
    )
    (comp (ref "R63")
      (value "1K")
      (footprint "eagle-import:R0805W")
      (libsource (lib "eagle-import") (part "R-EU_R0805W"))
    )
    (comp (ref "R64")
      (value "1K")
      (footprint "eagle-import:R0805W")
      (libsource (lib "eagle-import") (part "R-EU_R0805W"))
    )
    (comp (ref "R65")
      (value "10K")
      (footprint "eagle-import:R0805W")
      (libsource (lib "eagle-import") (part "R-EU_R0805W"))
    )
    (comp (ref "R66")
      (value "10K")
      (footprint "eagle-import:R0805W")
      (libsource (lib "eagle-import") (part "R-EU_R0805W"))
    )
    (comp (ref "R67")
      (value "1K")
      (footprint "eagle-import:R0805W")
      (libsource (lib "eagle-import") (part "R-EU_R0805W"))
    )
    (comp (ref "R68")
      (value "1K")
      (footprint "eagle-import:R0805W")
      (libsource (lib "eagle-import") (part "R-EU_R0805W"))
    )
    (comp (ref "R69")
      (value "1K")
      (footprint "eagle-import:R0805W")
      (libsource (lib "eagle-import") (part "R-EU_R0805W"))
    )
    (comp (ref "R70")
      (value "10K")
      (footprint "eagle-import:R0805W")
      (libsource (lib "eagle-import") (part "R-EU_R0805W"))
    )
    (comp (ref "R71")
      (value "10K")
      (footprint "eagle-import:R0805W")
      (libsource (lib "eagle-import") (part "R-EU_R0805W"))
    )
    (comp (ref "R72")
      (value "1K")
      (footprint "eagle-import:R0805W")
      (libsource (lib "eagle-import") (part "R-EU_R0805W"))
    )
    (comp (ref "R73")
      (value "1K")
      (footprint "eagle-import:R0805W")
      (libsource (lib "eagle-import") (part "R-EU_R0805W"))
    )
    (comp (ref "R74")
      (value "1K")
      (footprint "eagle-import:R0805W")
      (libsource (lib "eagle-import") (part "R-EU_R0805W"))
    )
    (comp (ref "R75")
      (value "10K")
      (footprint "eagle-import:R0805W")
      (libsource (lib "eagle-import") (part "R-EU_R0805W"))
    )
    (comp (ref "R76")
      (value "10K")
      (footprint "eagle-import:R0805W")
      (libsource (lib "eagle-import") (part "R-EU_R0805W"))
    )
    (comp (ref "R77")
      (value "1K")
      (footprint "eagle-import:R0805W")
      (libsource (lib "eagle-import") (part "R-EU_R0805W"))
    )
    (comp (ref "R78")
      (value "1K")
      (footprint "eagle-import:R0805W")
      (libsource (lib "eagle-import") (part "R-EU_R0805W"))
    )
    (comp (ref "R79")
      (value "1K")
      (footprint "eagle-import:R0805W")
      (libsource (lib "eagle-import") (part "R-EU_R0805W"))
    )
    (comp (ref "R80")
      (value "10K")
      (footprint "eagle-import:R0805W")
      (libsource (lib "eagle-import") (part "R-EU_R0805W"))
    )
    (comp (ref "R81")
      (value "10K")
      (footprint "eagle-import:R0805W")
      (libsource (lib "eagle-import") (part "R-EU_R0805W"))
    )
    (comp (ref "R82")
      (value "1K")
      (footprint "eagle-import:R0805W")
      (libsource (lib "eagle-import") (part "R-EU_R0805W"))
    )
    (comp (ref "R83")
      (value "1K")
      (footprint "eagle-import:R0805W")
      (libsource (lib "eagle-import") (part "R-EU_R0805W"))
    )
    (comp (ref "R84")
      (value "1K")
      (footprint "eagle-import:R0805W")
      (libsource (lib "eagle-import") (part "R-EU_R0805W"))
    )
    (comp (ref "R85")
      (value "10K")
      (footprint "eagle-import:R0805W")
      (libsource (lib "eagle-import") (part "R-EU_R0805W"))
    )
    (comp (ref "R86")
      (value "10K")
      (footprint "eagle-import:R0805W")
      (libsource (lib "eagle-import") (part "R-EU_R0805W"))
    )
    (comp (ref "R87")
      (value "1K")
      (footprint "eagle-import:R0805W")
      (libsource (lib "eagle-import") (part "R-EU_R0805W"))
    )
    (comp (ref "R88")
      (value "1K")
      (footprint "eagle-import:R0805W")
      (libsource (lib "eagle-import") (part "R-EU_R0805W"))
    )
    (comp (ref "R89")
      (value "1K")
      (footprint "eagle-import:R0805W")
      (libsource (lib "eagle-import") (part "R-EU_R0805W"))
    )
    (comp (ref "R90")
      (value "10K")
      (footprint "eagle-import:R0805W")
      (libsource (lib "eagle-import") (part "R-EU_R0805W"))
    )
    (comp (ref "R91")
      (value "10K")
      (footprint "eagle-import:R0805W")
      (libsource (lib "eagle-import") (part "R-EU_R0805W"))
    )
    (comp (ref "R92")
      (value "10K")
      (footprint "eagle-import:R0805W")
      (libsource (lib "eagle-import") (part "R-EU_R0805W"))
    )
    (comp (ref "R93")
      (value "10K")
      (footprint "eagle-import:R0805W")
      (libsource (lib "eagle-import") (part "R-EU_R0805W"))
    )
    (comp (ref "R94")
      (value "10K")
      (footprint "eagle-import:R0805W")
      (libsource (lib "eagle-import") (part "R-EU_R0805W"))
    )
    (comp (ref "R95")
      (value "10K")
      (footprint "eagle-import:R0805W")
      (libsource (lib "eagle-import") (part "R-EU_R0805W"))
    )
    (comp (ref "R96")
      (value "10K")
      (footprint "eagle-import:R0805W")
      (libsource (lib "eagle-import") (part "R-EU_R0805W"))
    )
    (comp (ref "R97")
      (value "10K")
      (footprint "eagle-import:R0805W")
      (libsource (lib "eagle-import") (part "R-EU_R0805W"))
    )
    (comp (ref "R98")
      (value "10K")
      (footprint "eagle-import:R0805W")
      (libsource (lib "eagle-import") (part "R-EU_R0805W"))
    )
    (comp (ref "R99")
      (value "10K")
      (footprint "eagle-import:R0805W")
      (libsource (lib "eagle-import") (part "R-EU_R0805W"))
    )
    (comp (ref "R100")
      (value "10K")
      (footprint "eagle-import:R0805W")
      (libsource (lib "eagle-import") (part "R-EU_R0805W"))
    )
    (comp (ref "R101")
      (value "10K")
      (footprint "eagle-import:R0805W")
      (libsource (lib "eagle-import") (part "R-EU_R0805W"))
    )
    (comp (ref "R102")
      (value "10K")
      (footprint "eagle-import:R0805W")
      (libsource (lib "eagle-import") (part "R-EU_R0805W"))
    )
    (comp (ref "R103")
      (value "10K")
      (footprint "eagle-import:R0805W")
      (libsource (lib "eagle-import") (part "R-EU_R0805W"))
    )
    (comp (ref "R104")
      (value "10K")
      (footprint "eagle-import:R0805W")
      (libsource (lib "eagle-import") (part "R-EU_R0805W"))
    )
    (comp (ref "R105")
      (value "10K")
      (footprint "eagle-import:R0805W")
      (libsource (lib "eagle-import") (part "R-EU_R0805W"))
    )
    (comp (ref "R106")
      (value "10K")
      (footprint "eagle-import:R0805W")
      (libsource (lib "eagle-import") (part "R-EU_R0805W"))
    )
    (comp (ref "R107")
      (value "10K")
      (footprint "eagle-import:R0805W")
      (libsource (lib "eagle-import") (part "R-EU_R0805W"))
    )
    (comp (ref "R108")
      (value "1K")
      (footprint "eagle-import:R0805W")
      (libsource (lib "eagle-import") (part "R-EU_R0805W"))
    )
    (comp (ref "R109")
      (value "10K")
      (footprint "eagle-import:R0805W")
      (libsource (lib "eagle-import") (part "R-EU_R0805W"))
    )
    (comp (ref "R110")
      (value "1K")
      (footprint "eagle-import:R0805W")
      (libsource (lib "eagle-import") (part "R-EU_R0805W"))
    )
    (comp (ref "R111")
      (value "1K")
      (footprint "eagle-import:R0805W")
      (libsource (lib "eagle-import") (part "R-EU_R0805W"))
    )
    (comp (ref "S1")
      (value "10-XX")
      (footprint "eagle-import:B3F-10XX")
      (fields (field (name "MPN") "B3F-1000"))
      (libsource (lib "eagle-import") (part "10-XX"))
    )
    (comp (ref "T1")
      (value "BC547")
      (footprint "eagle-import:TO92")
      (libsource (lib "eagle-import") (part "BC547"))
    )
    (comp (ref "U$1")
      (value "IRLML2030")
      (footprint "eagle-import:SOT23")
      (libsource (lib "eagle-import") (part "IRLML2030"))
    )
    (comp (ref "U$2")
      (value "IRLML2030")
      (footprint "eagle-import:SOT23")
      (libsource (lib "eagle-import") (part "IRLML2030"))
    )
    (comp (ref "U$3")
      (value "IRLML2030")
      (footprint "eagle-import:SOT23")
      (libsource (lib "eagle-import") (part "IRLML2030"))
    )
    (comp (ref "U$4")
      (value "IRLML2030")
      (footprint "eagle-import:SOT23")
      (libsource (lib "eagle-import") (part "IRLML2030"))
    )
    (comp (ref "U$5")
      (value "IRLML2030")
      (footprint "eagle-import:SOT23")
      (libsource (lib "eagle-import") (part "IRLML2030"))
    )
    (comp (ref "U$6")
      (value "IRLML2030")
      (footprint "eagle-import:SOT23")
      (libsource (lib "eagle-import") (part "IRLML2030"))
    )
    (comp (ref "U$7")
      (value "IRLML2030")
      (footprint "eagle-import:SOT23")
      (libsource (lib "eagle-import") (part "IRLML2030"))
    )
    (comp (ref "U$8")
      (value "IRLML2030")
      (footprint "eagle-import:SOT23")
      (libsource (lib "eagle-import") (part "IRLML2030"))
    )
    (comp (ref "U$9")
      (value "IRLML2030")
      (footprint "eagle-import:SOT23")
      (libsource (lib "eagle-import") (part "IRLML2030"))
    )
    (comp (ref "U$10")
      (value "IRLML2030")
      (footprint "eagle-import:SOT23")
      (libsource (lib "eagle-import") (part "IRLML2030"))
    )
    (comp (ref "U$11")
      (value "IRLML2030")
      (footprint "eagle-import:SOT23")
      (libsource (lib "eagle-import") (part "IRLML2030"))
    )
    (comp (ref "U$12")
      (value "IRLML2030")
      (footprint "eagle-import:SOT23")
      (libsource (lib "eagle-import") (part "IRLML2030"))
    )
    (comp (ref "U$13")
      (value "IRLML2030")
      (footprint "eagle-import:SOT23")
      (libsource (lib "eagle-import") (part "IRLML2030"))
    )
    (comp (ref "U$14")
      (value "IRLML2030")
      (footprint "eagle-import:SOT23")
      (libsource (lib "eagle-import") (part "IRLML2030"))
    )
    (comp (ref "U$15")
      (value "IRLML2030")
      (footprint "eagle-import:SOT23")
      (libsource (lib "eagle-import") (part "IRLML2030"))
    )
    (comp (ref "U$16")
      (value "IRLML2030")
      (footprint "eagle-import:SOT23")
      (libsource (lib "eagle-import") (part "IRLML2030"))
    )
    (comp (ref "U1")
      (value "ATTINY85-20SU")
      (footprint "eagle-import:SOIC-8")
      (fields
        (field (name "DIGI_KEY_PART_NUMBER") "ATTINY85-20SU-ND")
        (field (name "MANUFACTURER") "Microchip Technology")
        (field (name "CREATED_BY") "PCBLayout.com")
      )
      (libsource (lib "eagle-import") (part "ATTINY85-20SU"))
    )
    (comp (ref "X1")
      (value "MKDSN1,5/3-5,08")
      (footprint "eagle-import:MKDSN1,5_3-5,08")
      (libsource (lib "eagle-import") (part "MKDSN1,5/3-5,08"))
    )
    (comp (ref "X2")
      (value "MKDSN1,5/2-5,08")
      (footprint "eagle-import:MKDSN1,5_2-5,08")
      (libsource (lib "eagle-import") (part "MKDSN1,5/2-5,08"))
    )
  )
  (nets
    (net (code "1") (name "+5V") (class "Default")
      (node (ref "C1") (pin "1") (pinfunction "1_1") (pintype "passive"))
      (node (ref "C2") (pin "1") (pinfunction "1_1") (pintype "passive"))
      (node (ref "C3") (pin "1") (pinfunction "1_1") (pintype "passive"))
      (node (ref "C4") (pin "2") (pinfunction "2_2") (pintype "passive"))
      (node (ref "C5") (pin "2") (pinfunction "2_2") (pintype "passive"))
      (node (ref "C6") (pin "2") (pinfunction "2_2") (pintype "passive"))
      (node (ref "C7") (pin "2") (pinfunction "2_2") (pintype "passive"))
      (node (ref "C8") (pin "2") (pinfunction "2_2") (pintype "passive"))
      (node (ref "IC1") (pin "16") (pinfunction "VCC_16") (pintype "power_in"))
      (node (ref "IC2") (pin "16") (pinfunction "VCC_16") (pintype "power_in"))
      (node (ref "IC3") (pin "16") (pinfunction "VCC_16") (pintype "power_in"))
      (node (ref "IC4") (pin "16") (pinfunction "VCC_16") (pintype "power_in"))
      (node (ref "IC5") (pin "16") (pinfunction "VCC_16") (pintype "power_in"))
      (node (ref "IC6") (pin "16") (pinfunction "VCC_16") (pintype "power_in"))
      (node (ref "IC7") (pin "16") (pinfunction "VCC_16") (pintype "power_in"))
      (node (ref "JP5") (pin "2") (pinfunction "2_2") (pintype "passive"))
      (node (ref "R109") (pin "2") (pinfunction "2_2") (pintype "passive"))
      (node (ref "R110") (pin "1") (pinfunction "1_1") (pintype "passive"))
      (node (ref "R61") (pin "2") (pinfunction "2_2") (pintype "passive"))
      (node (ref "R66") (pin "2") (pinfunction "2_2") (pintype "passive"))
      (node (ref "R71") (pin "2") (pinfunction "2_2") (pintype "passive"))
      (node (ref "R76") (pin "2") (pinfunction "2_2") (pintype "passive"))
      (node (ref "R81") (pin "2") (pinfunction "2_2") (pintype "passive"))
      (node (ref "R86") (pin "2") (pinfunction "2_2") (pintype "passive"))
      (node (ref "R91") (pin "2") (pinfunction "2_2") (pintype "passive"))
      (node (ref "U1") (pin "8") (pinfunction "VCC_8") (pintype "power_in"))
      (node (ref "X2") (pin "1") (pinfunction "KL_1") (pintype "passive"))
    )
    (net (code "2") (name "/CLOCK") (class "Default")
      (node (ref "JP1") (pin "2") (pinfunction "2_2") (pintype "passive"))
      (node (ref "R111") (pin "2") (pinfunction "2_2") (pintype "passive"))
      (node (ref "R58") (pin "2") (pinfunction "2_2") (pintype "passive"))
      (node (ref "R63") (pin "2") (pinfunction "2_2") (pintype "passive"))
      (node (ref "R68") (pin "2") (pinfunction "2_2") (pintype "passive"))
      (node (ref "R73") (pin "2") (pinfunction "2_2") (pintype "passive"))
      (node (ref "R78") (pin "2") (pinfunction "2_2") (pintype "passive"))
      (node (ref "R83") (pin "2") (pinfunction "2_2") (pintype "passive"))
      (node (ref "R88") (pin "2") (pinfunction "2_2") (pintype "passive"))
    )
    (net (code "3") (name "/DATA") (class "Default")
      (node (ref "JP3") (pin "2") (pinfunction "2_2") (pintype "passive"))
      (node (ref "R87") (pin "2") (pinfunction "2_2") (pintype "passive"))
    )
    (net (code "4") (name "/LATCH") (class "Default")
      (node (ref "JP2") (pin "2") (pinfunction "2_2") (pintype "passive"))
      (node (ref "R59") (pin "2") (pinfunction "2_2") (pintype "passive"))
      (node (ref "R64") (pin "2") (pinfunction "2_2") (pintype "passive"))
      (node (ref "R69") (pin "2") (pinfunction "2_2") (pintype "passive"))
      (node (ref "R74") (pin "2") (pinfunction "2_2") (pintype "passive"))
      (node (ref "R79") (pin "2") (pinfunction "2_2") (pintype "passive"))
      (node (ref "R84") (pin "2") (pinfunction "2_2") (pintype "passive"))
      (node (ref "R89") (pin "2") (pinfunction "2_2") (pintype "passive"))
    )
    (net (code "5") (name "/MISO") (class "Default")
      (node (ref "JP1") (pin "3") (pinfunction "3_3") (pintype "passive"))
      (node (ref "JP5") (pin "1") (pinfunction "1_1") (pintype "passive"))
      (node (ref "U1") (pin "6") (pinfunction "PB1_6") (pintype "bidirectional"))
    )
    (net (code "6") (name "/MOSI") (class "Default")
      (node (ref "JP4") (pin "2") (pinfunction "2_2") (pintype "passive"))
      (node (ref "JP5") (pin "4") (pinfunction "4_4") (pintype "passive"))
      (node (ref "U1") (pin "5") (pinfunction "PB0_5") (pintype "bidirectional"))
    )
    (net (code "7") (name "/RESET") (class "Default")
      (node (ref "C9") (pin "1") (pinfunction "1_1") (pintype "passive"))
      (node (ref "JP5") (pin "5") (pinfunction "5_5") (pintype "passive"))
      (node (ref "R109") (pin "1") (pinfunction "1_1") (pintype "passive"))
      (node (ref "S1") (pin "1") (pinfunction "S_1") (pintype "passive"))
      (node (ref "S1") (pin "2") (pinfunction "S1_2") (pintype "passive"))
      (node (ref "U1") (pin "1") (pinfunction "PB5_1") (pintype "bidirectional"))
    )
    (net (code "8") (name "/SCK") (class "Default")
      (node (ref "JP4") (pin "1") (pinfunction "1_1") (pintype "passive"))
      (node (ref "JP5") (pin "3") (pinfunction "3_3") (pintype "passive"))
      (node (ref "U1") (pin "7") (pinfunction "PB2_7") (pintype "bidirectional"))
    )
    (net (code "9") (name "GND") (class "Default")
      (node (ref "C1") (pin "2") (pinfunction "2_2") (pintype "passive"))
      (node (ref "C2") (pin "2") (pinfunction "2_2") (pintype "passive"))
      (node (ref "C3") (pin "2") (pinfunction "2_2") (pintype "passive"))
      (node (ref "C4") (pin "1") (pinfunction "1_1") (pintype "passive"))
      (node (ref "C5") (pin "1") (pinfunction "1_1") (pintype "passive"))
      (node (ref "C6") (pin "1") (pinfunction "1_1") (pintype "passive"))
      (node (ref "C7") (pin "1") (pinfunction "1_1") (pintype "passive"))
      (node (ref "C8") (pin "1") (pinfunction "1_1") (pintype "passive"))
      (node (ref "IC1") (pin "8") (pinfunction "GND_8") (pintype "power_in"))
      (node (ref "IC2") (pin "8") (pinfunction "GND_8") (pintype "power_in"))
      (node (ref "IC3") (pin "8") (pinfunction "GND_8") (pintype "power_in"))
      (node (ref "IC4") (pin "8") (pinfunction "GND_8") (pintype "power_in"))
      (node (ref "IC5") (pin "8") (pinfunction "GND_8") (pintype "power_in"))
      (node (ref "IC6") (pin "8") (pinfunction "GND_8") (pintype "power_in"))
      (node (ref "IC7") (pin "8") (pinfunction "GND_8") (pintype "power_in"))
      (node (ref "JP4") (pin "3") (pinfunction "3_3") (pintype "passive"))
      (node (ref "JP5") (pin "6") (pinfunction "6_6") (pintype "passive"))
      (node (ref "R100") (pin "2") (pinfunction "2_2") (pintype "passive"))
      (node (ref "R101") (pin "2") (pinfunction "2_2") (pintype "passive"))
      (node (ref "R102") (pin "2") (pinfunction "2_2") (pintype "passive"))
      (node (ref "R103") (pin "2") (pinfunction "2_2") (pintype "passive"))
      (node (ref "R104") (pin "2") (pinfunction "2_2") (pintype "passive"))
      (node (ref "R105") (pin "2") (pinfunction "2_2") (pintype "passive"))
      (node (ref "R106") (pin "2") (pinfunction "2_2") (pintype "passive"))
      (node (ref "R107") (pin "2") (pinfunction "2_2") (pintype "passive"))
      (node (ref "R108") (pin "2") (pinfunction "2_2") (pintype "passive"))
      (node (ref "R60") (pin "2") (pinfunction "2_2") (pintype "passive"))
      (node (ref "R65") (pin "2") (pinfunction "2_2") (pintype "passive"))
      (node (ref "R70") (pin "2") (pinfunction "2_2") (pintype "passive"))
      (node (ref "R75") (pin "2") (pinfunction "2_2") (pintype "passive"))
      (node (ref "R80") (pin "2") (pinfunction "2_2") (pintype "passive"))
      (node (ref "R85") (pin "2") (pinfunction "2_2") (pintype "passive"))
      (node (ref "R90") (pin "2") (pinfunction "2_2") (pintype "passive"))
      (node (ref "R92") (pin "2") (pinfunction "2_2") (pintype "passive"))
      (node (ref "R93") (pin "2") (pinfunction "2_2") (pintype "passive"))
      (node (ref "R94") (pin "2") (pinfunction "2_2") (pintype "passive"))
      (node (ref "R95") (pin "2") (pinfunction "2_2") (pintype "passive"))
      (node (ref "R96") (pin "2") (pinfunction "2_2") (pintype "passive"))
      (node (ref "R97") (pin "2") (pinfunction "2_2") (pintype "passive"))
      (node (ref "R98") (pin "2") (pinfunction "2_2") (pintype "passive"))
      (node (ref "R99") (pin "2") (pinfunction "2_2") (pintype "passive"))
      (node (ref "T1") (pin "1") (pinfunction "E_1") (pintype "passive"))
      (node (ref "U$1") (pin "2") (pinfunction "S_2") (pintype "passive"))
      (node (ref "U$10") (pin "2") (pinfunction "S_2") (pintype "passive"))
      (node (ref "U$11") (pin "2") (pinfunction "S_2") (pintype "passive"))
      (node (ref "U$12") (pin "2") (pinfunction "S_2") (pintype "passive"))
      (node (ref "U$13") (pin "2") (pinfunction "S_2") (pintype "passive"))
      (node (ref "U$14") (pin "2") (pinfunction "S_2") (pintype "passive"))
      (node (ref "U$15") (pin "2") (pinfunction "S_2") (pintype "passive"))
      (node (ref "U$16") (pin "2") (pinfunction "S_2") (pintype "passive"))
      (node (ref "U$2") (pin "2") (pinfunction "S_2") (pintype "passive"))
      (node (ref "U$3") (pin "2") (pinfunction "S_2") (pintype "passive"))
      (node (ref "U$4") (pin "2") (pinfunction "S_2") (pintype "passive"))
      (node (ref "U$5") (pin "2") (pinfunction "S_2") (pintype "passive"))
      (node (ref "U$6") (pin "2") (pinfunction "S_2") (pintype "passive"))
      (node (ref "U$7") (pin "2") (pinfunction "S_2") (pintype "passive"))
      (node (ref "U$8") (pin "2") (pinfunction "S_2") (pintype "passive"))
      (node (ref "U$9") (pin "2") (pinfunction "S_2") (pintype "passive"))
      (node (ref "U1") (pin "4") (pinfunction "GND_4") (pintype "power_in"))
      (node (ref "X2") (pin "2") (pinfunction "KL_2") (pintype "passive"))
    )
    (net (code "10") (name "Net-(IC1A-G)") (class "Default")
      (node (ref "IC1") (pin "13") (pinfunction "G_13") (pintype "input"))
      (node (ref "R65") (pin "1") (pinfunction "1_1") (pintype "passive"))
    )
    (net (code "11") (name "Net-(IC1A-QA)") (class "Default")
      (node (ref "IC1") (pin "15") (pinfunction "QA_15") (pintype "tri_state"))
      (node (ref "R25") (pin "2") (pinfunction "2_2") (pintype "passive"))
    )
    (net (code "12") (name "Net-(IC1A-QB)") (class "Default")
      (node (ref "IC1") (pin "1") (pinfunction "QB_1") (pintype "tri_state"))
      (node (ref "R26") (pin "2") (pinfunction "2_2") (pintype "passive"))
    )
    (net (code "13") (name "Net-(IC1A-QC)") (class "Default")
      (node (ref "IC1") (pin "2") (pinfunction "QC_2") (pintype "tri_state"))
      (node (ref "R27") (pin "2") (pinfunction "2_2") (pintype "passive"))
    )
    (net (code "14") (name "Net-(IC1A-QD)") (class "Default")
      (node (ref "IC1") (pin "3") (pinfunction "QD_3") (pintype "tri_state"))
      (node (ref "R28") (pin "2") (pinfunction "2_2") (pintype "passive"))
    )
    (net (code "15") (name "Net-(IC1A-QE)") (class "Default")
      (node (ref "IC1") (pin "4") (pinfunction "QE_4") (pintype "tri_state"))
      (node (ref "R29") (pin "2") (pinfunction "2_2") (pintype "passive"))
    )
    (net (code "16") (name "Net-(IC1A-QF)") (class "Default")
      (node (ref "IC1") (pin "5") (pinfunction "QF_5") (pintype "tri_state"))
      (node (ref "R30") (pin "2") (pinfunction "2_2") (pintype "passive"))
    )
    (net (code "17") (name "Net-(IC1A-QG)") (class "Default")
      (node (ref "IC1") (pin "6") (pinfunction "QG_6") (pintype "tri_state"))
      (node (ref "R31") (pin "2") (pinfunction "2_2") (pintype "passive"))
    )
    (net (code "18") (name "Net-(IC1A-QH)") (class "Default")
      (node (ref "IC1") (pin "7") (pinfunction "QH_7") (pintype "tri_state"))
      (node (ref "R32") (pin "2") (pinfunction "2_2") (pintype "passive"))
    )
    (net (code "19") (name "Net-(IC1A-QH*)") (class "Default")
      (node (ref "IC1") (pin "9") (pinfunction "QH*_9") (pintype "tri_state"))
      (node (ref "R67") (pin "2") (pinfunction "2_2") (pintype "passive"))
    )
    (net (code "20") (name "Net-(IC1A-RCK)") (class "Default")
      (node (ref "IC1") (pin "12") (pinfunction "RCK_12") (pintype "input"))
      (node (ref "R64") (pin "1") (pinfunction "1_1") (pintype "passive"))
    )
    (net (code "21") (name "Net-(IC1A-SCK)") (class "Default")
      (node (ref "IC1") (pin "11") (pinfunction "SCK_11") (pintype "input"))
      (node (ref "R63") (pin "1") (pinfunction "1_1") (pintype "passive"))
    )
    (net (code "22") (name "Net-(IC1A-SCL)") (class "Default")
      (node (ref "IC1") (pin "10") (pinfunction "SCL_10") (pintype "input"))
      (node (ref "R66") (pin "1") (pinfunction "1_1") (pintype "passive"))
    )
    (net (code "23") (name "Net-(IC1A-SER)") (class "Default")
      (node (ref "IC1") (pin "14") (pinfunction "SER_14") (pintype "input"))
      (node (ref "R62") (pin "1") (pinfunction "1_1") (pintype "passive"))
    )
    (net (code "24") (name "Net-(IC2A-G)") (class "Default")
      (node (ref "IC2") (pin "13") (pinfunction "G_13") (pintype "input"))
      (node (ref "R60") (pin "1") (pinfunction "1_1") (pintype "passive"))
    )
    (net (code "25") (name "Net-(IC2A-QA)") (class "Default")
      (node (ref "IC2") (pin "15") (pinfunction "QA_15") (pintype "tri_state"))
      (node (ref "R3") (pin "2") (pinfunction "2_2") (pintype "passive"))
    )
    (net (code "26") (name "Net-(IC2A-QB)") (class "Default")
      (node (ref "IC2") (pin "1") (pinfunction "QB_1") (pintype "tri_state"))
      (node (ref "R19") (pin "2") (pinfunction "2_2") (pintype "passive"))
    )
    (net (code "27") (name "Net-(IC2A-QC)") (class "Default")
      (node (ref "IC2") (pin "2") (pinfunction "QC_2") (pintype "tri_state"))
      (node (ref "R20") (pin "2") (pinfunction "2_2") (pintype "passive"))
    )
    (net (code "28") (name "Net-(IC2A-QD)") (class "Default")
      (node (ref "IC2") (pin "3") (pinfunction "QD_3") (pintype "tri_state"))
      (node (ref "R2") (pin "2") (pinfunction "2_2") (pintype "passive"))
    )
    (net (code "29") (name "Net-(IC2A-QE)") (class "Default")
      (node (ref "IC2") (pin "4") (pinfunction "QE_4") (pintype "tri_state"))
      (node (ref "R21") (pin "2") (pinfunction "2_2") (pintype "passive"))
    )
    (net (code "30") (name "Net-(IC2A-QF)") (class "Default")
      (node (ref "IC2") (pin "5") (pinfunction "QF_5") (pintype "tri_state"))
      (node (ref "R22") (pin "2") (pinfunction "2_2") (pintype "passive"))
    )
    (net (code "31") (name "Net-(IC2A-QG)") (class "Default")
      (node (ref "IC2") (pin "6") (pinfunction "QG_6") (pintype "tri_state"))
      (node (ref "R23") (pin "2") (pinfunction "2_2") (pintype "passive"))
    )
    (net (code "32") (name "Net-(IC2A-QH)") (class "Default")
      (node (ref "IC2") (pin "7") (pinfunction "QH_7") (pintype "tri_state"))
      (node (ref "R24") (pin "2") (pinfunction "2_2") (pintype "passive"))
    )
    (net (code "33") (name "Net-(IC2A-QH*)") (class "Default")
      (node (ref "IC2") (pin "9") (pinfunction "QH*_9") (pintype "tri_state"))
      (node (ref "R62") (pin "2") (pinfunction "2_2") (pintype "passive"))
    )
    (net (code "34") (name "Net-(IC2A-RCK)") (class "Default")
      (node (ref "IC2") (pin "12") (pinfunction "RCK_12") (pintype "input"))
      (node (ref "R59") (pin "1") (pinfunction "1_1") (pintype "passive"))
    )
    (net (code "35") (name "Net-(IC2A-SCK)") (class "Default")
      (node (ref "IC2") (pin "11") (pinfunction "SCK_11") (pintype "input"))
      (node (ref "R58") (pin "1") (pinfunction "1_1") (pintype "passive"))
    )
    (net (code "36") (name "Net-(IC2A-SCL)") (class "Default")
      (node (ref "IC2") (pin "10") (pinfunction "SCL_10") (pintype "input"))
      (node (ref "R61") (pin "1") (pinfunction "1_1") (pintype "passive"))
    )
    (net (code "37") (name "Net-(IC2A-SER)") (class "Default")
      (node (ref "IC2") (pin "14") (pinfunction "SER_14") (pintype "input"))
      (node (ref "R57") (pin "1") (pinfunction "1_1") (pintype "passive"))
    )
    (net (code "38") (name "Net-(IC3A-G)") (class "Default")
      (node (ref "IC3") (pin "13") (pinfunction "G_13") (pintype "input"))
      (node (ref "R70") (pin "1") (pinfunction "1_1") (pintype "passive"))
    )
    (net (code "39") (name "Net-(IC3A-QA)") (class "Default")
      (node (ref "IC3") (pin "15") (pinfunction "QA_15") (pintype "tri_state"))
      (node (ref "R33") (pin "2") (pinfunction "2_2") (pintype "passive"))
    )
    (net (code "40") (name "Net-(IC3A-QB)") (class "Default")
      (node (ref "IC3") (pin "1") (pinfunction "QB_1") (pintype "tri_state"))
      (node (ref "R34") (pin "2") (pinfunction "2_2") (pintype "passive"))
    )
    (net (code "41") (name "Net-(IC3A-QC)") (class "Default")
      (node (ref "IC3") (pin "2") (pinfunction "QC_2") (pintype "tri_state"))
      (node (ref "R35") (pin "2") (pinfunction "2_2") (pintype "passive"))
    )
    (net (code "42") (name "Net-(IC3A-QD)") (class "Default")
      (node (ref "IC3") (pin "3") (pinfunction "QD_3") (pintype "tri_state"))
      (node (ref "R36") (pin "2") (pinfunction "2_2") (pintype "passive"))
    )
    (net (code "43") (name "Net-(IC3A-QE)") (class "Default")
      (node (ref "IC3") (pin "4") (pinfunction "QE_4") (pintype "tri_state"))
      (node (ref "R37") (pin "2") (pinfunction "2_2") (pintype "passive"))
    )
    (net (code "44") (name "Net-(IC3A-QF)") (class "Default")
      (node (ref "IC3") (pin "5") (pinfunction "QF_5") (pintype "tri_state"))
      (node (ref "R38") (pin "2") (pinfunction "2_2") (pintype "passive"))
    )
    (net (code "45") (name "Net-(IC3A-QG)") (class "Default")
      (node (ref "IC3") (pin "6") (pinfunction "QG_6") (pintype "tri_state"))
      (node (ref "R39") (pin "2") (pinfunction "2_2") (pintype "passive"))
    )
    (net (code "46") (name "Net-(IC3A-QH)") (class "Default")
      (node (ref "IC3") (pin "7") (pinfunction "QH_7") (pintype "tri_state"))
      (node (ref "R40") (pin "2") (pinfunction "2_2") (pintype "passive"))
    )
    (net (code "47") (name "Net-(IC3A-QH*)") (class "Default")
      (node (ref "IC3") (pin "9") (pinfunction "QH*_9") (pintype "tri_state"))
      (node (ref "R72") (pin "2") (pinfunction "2_2") (pintype "passive"))
    )
    (net (code "48") (name "Net-(IC3A-RCK)") (class "Default")
      (node (ref "IC3") (pin "12") (pinfunction "RCK_12") (pintype "input"))
      (node (ref "R69") (pin "1") (pinfunction "1_1") (pintype "passive"))
    )
    (net (code "49") (name "Net-(IC3A-SCK)") (class "Default")
      (node (ref "IC3") (pin "11") (pinfunction "SCK_11") (pintype "input"))
      (node (ref "R68") (pin "1") (pinfunction "1_1") (pintype "passive"))
    )
    (net (code "50") (name "Net-(IC3A-SCL)") (class "Default")
      (node (ref "IC3") (pin "10") (pinfunction "SCL_10") (pintype "input"))
      (node (ref "R71") (pin "1") (pinfunction "1_1") (pintype "passive"))
    )
    (net (code "51") (name "Net-(IC3A-SER)") (class "Default")
      (node (ref "IC3") (pin "14") (pinfunction "SER_14") (pintype "input"))
      (node (ref "R67") (pin "1") (pinfunction "1_1") (pintype "passive"))
    )
    (net (code "52") (name "Net-(IC4A-G)") (class "Default")
      (node (ref "IC4") (pin "13") (pinfunction "G_13") (pintype "input"))
      (node (ref "R75") (pin "1") (pinfunction "1_1") (pintype "passive"))
    )
    (net (code "53") (name "Net-(IC4A-QA)") (class "Default")
      (node (ref "IC4") (pin "15") (pinfunction "QA_15") (pintype "tri_state"))
      (node (ref "R41") (pin "2") (pinfunction "2_2") (pintype "passive"))
    )
    (net (code "54") (name "Net-(IC4A-QB)") (class "Default")
      (node (ref "IC4") (pin "1") (pinfunction "QB_1") (pintype "tri_state"))
      (node (ref "R42") (pin "2") (pinfunction "2_2") (pintype "passive"))
    )
    (net (code "55") (name "Net-(IC4A-QC)") (class "Default")
      (node (ref "IC4") (pin "2") (pinfunction "QC_2") (pintype "tri_state"))
      (node (ref "R43") (pin "2") (pinfunction "2_2") (pintype "passive"))
    )
    (net (code "56") (name "Net-(IC4A-QD)") (class "Default")
      (node (ref "IC4") (pin "3") (pinfunction "QD_3") (pintype "tri_state"))
      (node (ref "R44") (pin "2") (pinfunction "2_2") (pintype "passive"))
    )
    (net (code "57") (name "Net-(IC4A-QE)") (class "Default")
      (node (ref "IC4") (pin "4") (pinfunction "QE_4") (pintype "tri_state"))
      (node (ref "R45") (pin "2") (pinfunction "2_2") (pintype "passive"))
    )
    (net (code "58") (name "Net-(IC4A-QF)") (class "Default")
      (node (ref "IC4") (pin "5") (pinfunction "QF_5") (pintype "tri_state"))
      (node (ref "R46") (pin "2") (pinfunction "2_2") (pintype "passive"))
    )
    (net (code "59") (name "Net-(IC4A-QG)") (class "Default")
      (node (ref "IC4") (pin "6") (pinfunction "QG_6") (pintype "tri_state"))
      (node (ref "R47") (pin "2") (pinfunction "2_2") (pintype "passive"))
    )
    (net (code "60") (name "Net-(IC4A-QH)") (class "Default")
      (node (ref "IC4") (pin "7") (pinfunction "QH_7") (pintype "tri_state"))
      (node (ref "R48") (pin "2") (pinfunction "2_2") (pintype "passive"))
    )
    (net (code "61") (name "Net-(IC4A-QH*)") (class "Default")
      (node (ref "IC4") (pin "9") (pinfunction "QH*_9") (pintype "tri_state"))
      (node (ref "R77") (pin "2") (pinfunction "2_2") (pintype "passive"))
    )
    (net (code "62") (name "Net-(IC4A-RCK)") (class "Default")
      (node (ref "IC4") (pin "12") (pinfunction "RCK_12") (pintype "input"))
      (node (ref "R74") (pin "1") (pinfunction "1_1") (pintype "passive"))
    )
    (net (code "63") (name "Net-(IC4A-SCK)") (class "Default")
      (node (ref "IC4") (pin "11") (pinfunction "SCK_11") (pintype "input"))
      (node (ref "R73") (pin "1") (pinfunction "1_1") (pintype "passive"))
    )
    (net (code "64") (name "Net-(IC4A-SCL)") (class "Default")
      (node (ref "IC4") (pin "10") (pinfunction "SCL_10") (pintype "input"))
      (node (ref "R76") (pin "1") (pinfunction "1_1") (pintype "passive"))
    )
    (net (code "65") (name "Net-(IC4A-SER)") (class "Default")
      (node (ref "IC4") (pin "14") (pinfunction "SER_14") (pintype "input"))
      (node (ref "R72") (pin "1") (pinfunction "1_1") (pintype "passive"))
    )
    (net (code "66") (name "Net-(IC5A-G)") (class "Default")
      (node (ref "IC5") (pin "13") (pinfunction "G_13") (pintype "input"))
      (node (ref "R80") (pin "1") (pinfunction "1_1") (pintype "passive"))
    )
    (net (code "67") (name "Net-(IC5A-QA)") (class "Default")
      (node (ref "IC5") (pin "15") (pinfunction "QA_15") (pintype "tri_state"))
      (node (ref "R49") (pin "2") (pinfunction "2_2") (pintype "passive"))
    )
    (net (code "68") (name "Net-(IC5A-QB)") (class "Default")
      (node (ref "IC5") (pin "1") (pinfunction "QB_1") (pintype "tri_state"))
      (node (ref "R50") (pin "2") (pinfunction "2_2") (pintype "passive"))
    )
    (net (code "69") (name "Net-(IC5A-QC)") (class "Default")
      (node (ref "IC5") (pin "2") (pinfunction "QC_2") (pintype "tri_state"))
      (node (ref "R51") (pin "2") (pinfunction "2_2") (pintype "passive"))
    )
    (net (code "70") (name "Net-(IC5A-QD)") (class "Default")
      (node (ref "IC5") (pin "3") (pinfunction "QD_3") (pintype "tri_state"))
      (node (ref "R52") (pin "2") (pinfunction "2_2") (pintype "passive"))
    )
    (net (code "71") (name "Net-(IC5A-QE)") (class "Default")
      (node (ref "IC5") (pin "4") (pinfunction "QE_4") (pintype "tri_state"))
      (node (ref "R53") (pin "2") (pinfunction "2_2") (pintype "passive"))
    )
    (net (code "72") (name "Net-(IC5A-QF)") (class "Default")
      (node (ref "IC5") (pin "5") (pinfunction "QF_5") (pintype "tri_state"))
      (node (ref "R54") (pin "2") (pinfunction "2_2") (pintype "passive"))
    )
    (net (code "73") (name "Net-(IC5A-QG)") (class "Default")
      (node (ref "IC5") (pin "6") (pinfunction "QG_6") (pintype "tri_state"))
      (node (ref "R55") (pin "2") (pinfunction "2_2") (pintype "passive"))
    )
    (net (code "74") (name "Net-(IC5A-QH)") (class "Default")
      (node (ref "IC5") (pin "7") (pinfunction "QH_7") (pintype "tri_state"))
      (node (ref "R56") (pin "2") (pinfunction "2_2") (pintype "passive"))
    )
    (net (code "75") (name "Net-(IC5A-RCK)") (class "Default")
      (node (ref "IC5") (pin "12") (pinfunction "RCK_12") (pintype "input"))
      (node (ref "R79") (pin "1") (pinfunction "1_1") (pintype "passive"))
    )
    (net (code "76") (name "Net-(IC5A-SCK)") (class "Default")
      (node (ref "IC5") (pin "11") (pinfunction "SCK_11") (pintype "input"))
      (node (ref "R78") (pin "1") (pinfunction "1_1") (pintype "passive"))
    )
    (net (code "77") (name "Net-(IC5A-SCL)") (class "Default")
      (node (ref "IC5") (pin "10") (pinfunction "SCL_10") (pintype "input"))
      (node (ref "R81") (pin "1") (pinfunction "1_1") (pintype "passive"))
    )
    (net (code "78") (name "Net-(IC5A-SER)") (class "Default")
      (node (ref "IC5") (pin "14") (pinfunction "SER_14") (pintype "input"))
      (node (ref "R77") (pin "1") (pinfunction "1_1") (pintype "passive"))
    )
    (net (code "79") (name "Net-(IC6A-G)") (class "Default")
      (node (ref "IC6") (pin "13") (pinfunction "G_13") (pintype "input"))
      (node (ref "R85") (pin "1") (pinfunction "1_1") (pintype "passive"))
    )
    (net (code "80") (name "Net-(IC6A-QA)") (class "Default")
      (node (ref "IC6") (pin "15") (pinfunction "QA_15") (pintype "tri_state"))
      (node (ref "R10") (pin "1") (pinfunction "1_1") (pintype "passive"))
    )
    (net (code "81") (name "Net-(IC6A-QB)") (class "Default")
      (node (ref "IC6") (pin "1") (pinfunction "QB_1") (pintype "tri_state"))
      (node (ref "R9") (pin "1") (pinfunction "1_1") (pintype "passive"))
    )
    (net (code "82") (name "Net-(IC6A-QC)") (class "Default")
      (node (ref "IC6") (pin "2") (pinfunction "QC_2") (pintype "tri_state"))
      (node (ref "R8") (pin "1") (pinfunction "1_1") (pintype "passive"))
    )
    (net (code "83") (name "Net-(IC6A-QD)") (class "Default")
      (node (ref "IC6") (pin "3") (pinfunction "QD_3") (pintype "tri_state"))
      (node (ref "R7") (pin "1") (pinfunction "1_1") (pintype "passive"))
    )
    (net (code "84") (name "Net-(IC6A-QE)") (class "Default")
      (node (ref "IC6") (pin "4") (pinfunction "QE_4") (pintype "tri_state"))
      (node (ref "R6") (pin "1") (pinfunction "1_1") (pintype "passive"))
    )
    (net (code "85") (name "Net-(IC6A-QF)") (class "Default")
      (node (ref "IC6") (pin "5") (pinfunction "QF_5") (pintype "tri_state"))
      (node (ref "R5") (pin "1") (pinfunction "1_1") (pintype "passive"))
    )
    (net (code "86") (name "Net-(IC6A-QG)") (class "Default")
      (node (ref "IC6") (pin "6") (pinfunction "QG_6") (pintype "tri_state"))
      (node (ref "R4") (pin "1") (pinfunction "1_1") (pintype "passive"))
    )
    (net (code "87") (name "Net-(IC6A-QH)") (class "Default")
      (node (ref "IC6") (pin "7") (pinfunction "QH_7") (pintype "tri_state"))
      (node (ref "R1") (pin "1") (pinfunction "1_1") (pintype "passive"))
    )
    (net (code "88") (name "Net-(IC6A-QH*)") (class "Default")
      (node (ref "IC6") (pin "9") (pinfunction "QH*_9") (pintype "tri_state"))
      (node (ref "R57") (pin "2") (pinfunction "2_2") (pintype "passive"))
    )
    (net (code "89") (name "Net-(IC6A-RCK)") (class "Default")
      (node (ref "IC6") (pin "12") (pinfunction "RCK_12") (pintype "input"))
      (node (ref "R84") (pin "1") (pinfunction "1_1") (pintype "passive"))
    )
    (net (code "90") (name "Net-(IC6A-SCK)") (class "Default")
      (node (ref "IC6") (pin "11") (pinfunction "SCK_11") (pintype "input"))
      (node (ref "R83") (pin "1") (pinfunction "1_1") (pintype "passive"))
    )
    (net (code "91") (name "Net-(IC6A-SCL)") (class "Default")
      (node (ref "IC6") (pin "10") (pinfunction "SCL_10") (pintype "input"))
      (node (ref "R86") (pin "1") (pinfunction "1_1") (pintype "passive"))
    )
    (net (code "92") (name "Net-(IC6A-SER)") (class "Default")
      (node (ref "IC6") (pin "14") (pinfunction "SER_14") (pintype "input"))
      (node (ref "R82") (pin "1") (pinfunction "1_1") (pintype "passive"))
    )
    (net (code "93") (name "Net-(IC7A-G)") (class "Default")
      (node (ref "IC7") (pin "13") (pinfunction "G_13") (pintype "input"))
      (node (ref "R90") (pin "1") (pinfunction "1_1") (pintype "passive"))
    )
    (net (code "94") (name "Net-(IC7A-QA)") (class "Default")
      (node (ref "IC7") (pin "15") (pinfunction "QA_15") (pintype "tri_state"))
      (node (ref "R18") (pin "1") (pinfunction "1_1") (pintype "passive"))
    )
    (net (code "95") (name "Net-(IC7A-QB)") (class "Default")
      (node (ref "IC7") (pin "1") (pinfunction "QB_1") (pintype "tri_state"))
      (node (ref "R17") (pin "1") (pinfunction "1_1") (pintype "passive"))
    )
    (net (code "96") (name "Net-(IC7A-QC)") (class "Default")
      (node (ref "IC7") (pin "2") (pinfunction "QC_2") (pintype "tri_state"))
      (node (ref "R16") (pin "1") (pinfunction "1_1") (pintype "passive"))
    )
    (net (code "97") (name "Net-(IC7A-QD)") (class "Default")
      (node (ref "IC7") (pin "3") (pinfunction "QD_3") (pintype "tri_state"))
      (node (ref "R15") (pin "1") (pinfunction "1_1") (pintype "passive"))
    )
    (net (code "98") (name "Net-(IC7A-QE)") (class "Default")
      (node (ref "IC7") (pin "4") (pinfunction "QE_4") (pintype "tri_state"))
      (node (ref "R14") (pin "1") (pinfunction "1_1") (pintype "passive"))
    )
    (net (code "99") (name "Net-(IC7A-QF)") (class "Default")
      (node (ref "IC7") (pin "5") (pinfunction "QF_5") (pintype "tri_state"))
      (node (ref "R13") (pin "1") (pinfunction "1_1") (pintype "passive"))
    )
    (net (code "100") (name "Net-(IC7A-QG)") (class "Default")
      (node (ref "IC7") (pin "6") (pinfunction "QG_6") (pintype "tri_state"))
      (node (ref "R12") (pin "1") (pinfunction "1_1") (pintype "passive"))
    )
    (net (code "101") (name "Net-(IC7A-QH)") (class "Default")
      (node (ref "IC7") (pin "7") (pinfunction "QH_7") (pintype "tri_state"))
      (node (ref "R11") (pin "1") (pinfunction "1_1") (pintype "passive"))
    )
    (net (code "102") (name "Net-(IC7A-QH*)") (class "Default")
      (node (ref "IC7") (pin "9") (pinfunction "QH*_9") (pintype "tri_state"))
      (node (ref "R82") (pin "2") (pinfunction "2_2") (pintype "passive"))
    )
    (net (code "103") (name "Net-(IC7A-RCK)") (class "Default")
      (node (ref "IC7") (pin "12") (pinfunction "RCK_12") (pintype "input"))
      (node (ref "R89") (pin "1") (pinfunction "1_1") (pintype "passive"))
    )
    (net (code "104") (name "Net-(IC7A-SCK)") (class "Default")
      (node (ref "IC7") (pin "11") (pinfunction "SCK_11") (pintype "input"))
      (node (ref "R88") (pin "1") (pinfunction "1_1") (pintype "passive"))
    )
    (net (code "105") (name "Net-(IC7A-SCL)") (class "Default")
      (node (ref "IC7") (pin "10") (pinfunction "SCL_10") (pintype "input"))
      (node (ref "R91") (pin "1") (pinfunction "1_1") (pintype "passive"))
    )
    (net (code "106") (name "Net-(IC7A-SER)") (class "Default")
      (node (ref "IC7") (pin "14") (pinfunction "SER_14") (pintype "input"))
      (node (ref "R87") (pin "1") (pinfunction "1_1") (pintype "passive"))
    )
    (net (code "107") (name "Net-(LED1-C)") (class "Default")
      (node (ref "LED1") (pin "K") (pinfunction "C_K") (pintype "passive"))
      (node (ref "LED113") (pin "K") (pinfunction "C_K") (pintype "passive"))
      (node (ref "LED129") (pin "K") (pinfunction "C_K") (pintype "passive"))
      (node (ref "LED145") (pin "K") (pinfunction "C_K") (pintype "passive"))
      (node (ref "LED161") (pin "K") (pinfunction "C_K") (pintype "passive"))
      (node (ref "LED17") (pin "K") (pinfunction "C_K") (pintype "passive"))
      (node (ref "LED177") (pin "K") (pinfunction "C_K") (pintype "passive"))
      (node (ref "LED193") (pin "K") (pinfunction "C_K") (pintype "passive"))
      (node (ref "LED209") (pin "K") (pinfunction "C_K") (pintype "passive"))
      (node (ref "LED225") (pin "K") (pinfunction "C_K") (pintype "passive"))
      (node (ref "LED241") (pin "K") (pinfunction "C_K") (pintype "passive"))
      (node (ref "LED257") (pin "K") (pinfunction "C_K") (pintype "passive"))
      (node (ref "LED273") (pin "K") (pinfunction "C_K") (pintype "passive"))
      (node (ref "LED289") (pin "K") (pinfunction "C_K") (pintype "passive"))
      (node (ref "LED305") (pin "K") (pinfunction "C_K") (pintype "passive"))
      (node (ref "LED321") (pin "K") (pinfunction "C_K") (pintype "passive"))
      (node (ref "LED33") (pin "K") (pinfunction "C_K") (pintype "passive"))
      (node (ref "LED337") (pin "K") (pinfunction "C_K") (pintype "passive"))
      (node (ref "LED353") (pin "K") (pinfunction "C_K") (pintype "passive"))
      (node (ref "LED369") (pin "K") (pinfunction "C_K") (pintype "passive"))
      (node (ref "LED385") (pin "K") (pinfunction "C_K") (pintype "passive"))
      (node (ref "LED401") (pin "K") (pinfunction "C_K") (pintype "passive"))
      (node (ref "LED417") (pin "K") (pinfunction "C_K") (pintype "passive"))
      (node (ref "LED433") (pin "K") (pinfunction "C_K") (pintype "passive"))
      (node (ref "LED449") (pin "K") (pinfunction "C_K") (pintype "passive"))
      (node (ref "LED465") (pin "K") (pinfunction "C_K") (pintype "passive"))
      (node (ref "LED481") (pin "K") (pinfunction "C_K") (pintype "passive"))
      (node (ref "LED49") (pin "K") (pinfunction "C_K") (pintype "passive"))
      (node (ref "LED497") (pin "K") (pinfunction "C_K") (pintype "passive"))
      (node (ref "LED513") (pin "K") (pinfunction "C_K") (pintype "passive"))
      (node (ref "LED529") (pin "K") (pinfunction "C_K") (pintype "passive"))
      (node (ref "LED545") (pin "K") (pinfunction "C_K") (pintype "passive"))
      (node (ref "LED561") (pin "K") (pinfunction "C_K") (pintype "passive"))
      (node (ref "LED577") (pin "K") (pinfunction "C_K") (pintype "passive"))
      (node (ref "LED593") (pin "K") (pinfunction "C_K") (pintype "passive"))
      (node (ref "LED609") (pin "K") (pinfunction "C_K") (pintype "passive"))
      (node (ref "LED625") (pin "K") (pinfunction "C_K") (pintype "passive"))
      (node (ref "LED65") (pin "K") (pinfunction "C_K") (pintype "passive"))
      (node (ref "LED81") (pin "K") (pinfunction "C_K") (pintype "passive"))
      (node (ref "LED97") (pin "K") (pinfunction "C_K") (pintype "passive"))
      (node (ref "U$1") (pin "3") (pinfunction "D_3") (pintype "passive"))
    )
    (net (code "108") (name "Net-(LED1-PadA)") (class "Default")
      (node (ref "LED1") (pin "A") (pinfunction "A_A") (pintype "passive"))
      (node (ref "LED10") (pin "A") (pinfunction "A_A") (pintype "passive"))
      (node (ref "LED11") (pin "A") (pinfunction "A_A") (pintype "passive"))
      (node (ref "LED12") (pin "A") (pinfunction "A_A") (pintype "passive"))
      (node (ref "LED13") (pin "A") (pinfunction "A_A") (pintype "passive"))
      (node (ref "LED14") (pin "A") (pinfunction "A_A") (pintype "passive"))
      (node (ref "LED15") (pin "A") (pinfunction "A_A") (pintype "passive"))
      (node (ref "LED16") (pin "A") (pinfunction "A_A") (pintype "passive"))
      (node (ref "LED2") (pin "A") (pinfunction "A_A") (pintype "passive"))
      (node (ref "LED3") (pin "A") (pinfunction "A_A") (pintype "passive"))
      (node (ref "LED4") (pin "A") (pinfunction "A_A") (pintype "passive"))
      (node (ref "LED5") (pin "A") (pinfunction "A_A") (pintype "passive"))
      (node (ref "LED6") (pin "A") (pinfunction "A_A") (pintype "passive"))
      (node (ref "LED7") (pin "A") (pinfunction "A_A") (pintype "passive"))
      (node (ref "LED8") (pin "A") (pinfunction "A_A") (pintype "passive"))
      (node (ref "LED9") (pin "A") (pinfunction "A_A") (pintype "passive"))
      (node (ref "R3") (pin "1") (pinfunction "1_1") (pintype "passive"))
    )
    (net (code "109") (name "Net-(LED10-C)") (class "Default")
      (node (ref "LED10") (pin "K") (pinfunction "C_K") (pintype "passive"))
      (node (ref "LED106") (pin "K") (pinfunction "C_K") (pintype "passive"))
      (node (ref "LED122") (pin "K") (pinfunction "C_K") (pintype "passive"))
      (node (ref "LED138") (pin "K") (pinfunction "C_K") (pintype "passive"))
      (node (ref "LED154") (pin "K") (pinfunction "C_K") (pintype "passive"))
      (node (ref "LED170") (pin "K") (pinfunction "C_K") (pintype "passive"))
      (node (ref "LED186") (pin "K") (pinfunction "C_K") (pintype "passive"))
      (node (ref "LED202") (pin "K") (pinfunction "C_K") (pintype "passive"))
      (node (ref "LED218") (pin "K") (pinfunction "C_K") (pintype "passive"))
      (node (ref "LED234") (pin "K") (pinfunction "C_K") (pintype "passive"))
      (node (ref "LED250") (pin "K") (pinfunction "C_K") (pintype "passive"))
      (node (ref "LED26") (pin "K") (pinfunction "C_K") (pintype "passive"))
      (node (ref "LED266") (pin "K") (pinfunction "C_K") (pintype "passive"))
      (node (ref "LED282") (pin "K") (pinfunction "C_K") (pintype "passive"))
      (node (ref "LED298") (pin "K") (pinfunction "C_K") (pintype "passive"))
      (node (ref "LED314") (pin "K") (pinfunction "C_K") (pintype "passive"))
      (node (ref "LED330") (pin "K") (pinfunction "C_K") (pintype "passive"))
      (node (ref "LED346") (pin "K") (pinfunction "C_K") (pintype "passive"))
      (node (ref "LED362") (pin "K") (pinfunction "C_K") (pintype "passive"))
      (node (ref "LED378") (pin "K") (pinfunction "C_K") (pintype "passive"))
      (node (ref "LED394") (pin "K") (pinfunction "C_K") (pintype "passive"))
      (node (ref "LED410") (pin "K") (pinfunction "C_K") (pintype "passive"))
      (node (ref "LED42") (pin "K") (pinfunction "C_K") (pintype "passive"))
      (node (ref "LED426") (pin "K") (pinfunction "C_K") (pintype "passive"))
      (node (ref "LED442") (pin "K") (pinfunction "C_K") (pintype "passive"))
      (node (ref "LED458") (pin "K") (pinfunction "C_K") (pintype "passive"))
      (node (ref "LED474") (pin "K") (pinfunction "C_K") (pintype "passive"))
      (node (ref "LED490") (pin "K") (pinfunction "C_K") (pintype "passive"))
      (node (ref "LED506") (pin "K") (pinfunction "C_K") (pintype "passive"))
      (node (ref "LED522") (pin "K") (pinfunction "C_K") (pintype "passive"))
      (node (ref "LED538") (pin "K") (pinfunction "C_K") (pintype "passive"))
      (node (ref "LED554") (pin "K") (pinfunction "C_K") (pintype "passive"))
      (node (ref "LED570") (pin "K") (pinfunction "C_K") (pintype "passive"))
      (node (ref "LED58") (pin "K") (pinfunction "C_K") (pintype "passive"))
      (node (ref "LED586") (pin "K") (pinfunction "C_K") (pintype "passive"))
      (node (ref "LED602") (pin "K") (pinfunction "C_K") (pintype "passive"))
      (node (ref "LED618") (pin "K") (pinfunction "C_K") (pintype "passive"))
      (node (ref "LED634") (pin "K") (pinfunction "C_K") (pintype "passive"))
      (node (ref "LED74") (pin "K") (pinfunction "C_K") (pintype "passive"))
      (node (ref "LED90") (pin "K") (pinfunction "C_K") (pintype "passive"))
      (node (ref "U$10") (pin "3") (pinfunction "D_3") (pintype "passive"))
    )
    (net (code "110") (name "Net-(LED17-PadA)") (class "Default")
      (node (ref "LED17") (pin "A") (pinfunction "A_A") (pintype "passive"))
      (node (ref "LED18") (pin "A") (pinfunction "A_A") (pintype "passive"))
      (node (ref "LED19") (pin "A") (pinfunction "A_A") (pintype "passive"))
      (node (ref "LED20") (pin "A") (pinfunction "A_A") (pintype "passive"))
      (node (ref "LED21") (pin "A") (pinfunction "A_A") (pintype "passive"))
      (node (ref "LED22") (pin "A") (pinfunction "A_A") (pintype "passive"))
      (node (ref "LED23") (pin "A") (pinfunction "A_A") (pintype "passive"))
      (node (ref "LED24") (pin "A") (pinfunction "A_A") (pintype "passive"))
      (node (ref "LED25") (pin "A") (pinfunction "A_A") (pintype "passive"))
      (node (ref "LED26") (pin "A") (pinfunction "A_A") (pintype "passive"))
      (node (ref "LED27") (pin "A") (pinfunction "A_A") (pintype "passive"))
      (node (ref "LED28") (pin "A") (pinfunction "A_A") (pintype "passive"))
      (node (ref "LED29") (pin "A") (pinfunction "A_A") (pintype "passive"))
      (node (ref "LED30") (pin "A") (pinfunction "A_A") (pintype "passive"))
      (node (ref "LED31") (pin "A") (pinfunction "A_A") (pintype "passive"))
      (node (ref "LED32") (pin "A") (pinfunction "A_A") (pintype "passive"))
      (node (ref "R19") (pin "1") (pinfunction "1_1") (pintype "passive"))
    )
    (net (code "111") (name "Net-(LED33-PadA)") (class "Default")
      (node (ref "LED33") (pin "A") (pinfunction "A_A") (pintype "passive"))
      (node (ref "LED34") (pin "A") (pinfunction "A_A") (pintype "passive"))
      (node (ref "LED35") (pin "A") (pinfunction "A_A") (pintype "passive"))
      (node (ref "LED36") (pin "A") (pinfunction "A_A") (pintype "passive"))
      (node (ref "LED37") (pin "A") (pinfunction "A_A") (pintype "passive"))
      (node (ref "LED38") (pin "A") (pinfunction "A_A") (pintype "passive"))
      (node (ref "LED39") (pin "A") (pinfunction "A_A") (pintype "passive"))
      (node (ref "LED40") (pin "A") (pinfunction "A_A") (pintype "passive"))
      (node (ref "LED41") (pin "A") (pinfunction "A_A") (pintype "passive"))
      (node (ref "LED42") (pin "A") (pinfunction "A_A") (pintype "passive"))
      (node (ref "LED43") (pin "A") (pinfunction "A_A") (pintype "passive"))
      (node (ref "LED44") (pin "A") (pinfunction "A_A") (pintype "passive"))
      (node (ref "LED45") (pin "A") (pinfunction "A_A") (pintype "passive"))
      (node (ref "LED46") (pin "A") (pinfunction "A_A") (pintype "passive"))
      (node (ref "LED47") (pin "A") (pinfunction "A_A") (pintype "passive"))
      (node (ref "LED48") (pin "A") (pinfunction "A_A") (pintype "passive"))
      (node (ref "R20") (pin "1") (pinfunction "1_1") (pintype "passive"))
    )
    (net (code "112") (name "Net-(LED49-PadA)") (class "Default")
      (node (ref "LED49") (pin "A") (pinfunction "A_A") (pintype "passive"))
      (node (ref "LED50") (pin "A") (pinfunction "A_A") (pintype "passive"))
      (node (ref "LED51") (pin "A") (pinfunction "A_A") (pintype "passive"))
      (node (ref "LED52") (pin "A") (pinfunction "A_A") (pintype "passive"))
      (node (ref "LED53") (pin "A") (pinfunction "A_A") (pintype "passive"))
      (node (ref "LED54") (pin "A") (pinfunction "A_A") (pintype "passive"))
      (node (ref "LED55") (pin "A") (pinfunction "A_A") (pintype "passive"))
      (node (ref "LED56") (pin "A") (pinfunction "A_A") (pintype "passive"))
      (node (ref "LED57") (pin "A") (pinfunction "A_A") (pintype "passive"))
      (node (ref "LED58") (pin "A") (pinfunction "A_A") (pintype "passive"))
      (node (ref "LED59") (pin "A") (pinfunction "A_A") (pintype "passive"))
      (node (ref "LED60") (pin "A") (pinfunction "A_A") (pintype "passive"))
      (node (ref "LED61") (pin "A") (pinfunction "A_A") (pintype "passive"))
      (node (ref "LED62") (pin "A") (pinfunction "A_A") (pintype "passive"))
      (node (ref "LED63") (pin "A") (pinfunction "A_A") (pintype "passive"))
      (node (ref "LED64") (pin "A") (pinfunction "A_A") (pintype "passive"))
      (node (ref "R2") (pin "1") (pinfunction "1_1") (pintype "passive"))
    )
    (net (code "113") (name "Net-(LED65-PadA)") (class "Default")
      (node (ref "LED65") (pin "A") (pinfunction "A_A") (pintype "passive"))
      (node (ref "LED66") (pin "A") (pinfunction "A_A") (pintype "passive"))
      (node (ref "LED67") (pin "A") (pinfunction "A_A") (pintype "passive"))
      (node (ref "LED68") (pin "A") (pinfunction "A_A") (pintype "passive"))
      (node (ref "LED69") (pin "A") (pinfunction "A_A") (pintype "passive"))
      (node (ref "LED70") (pin "A") (pinfunction "A_A") (pintype "passive"))
      (node (ref "LED71") (pin "A") (pinfunction "A_A") (pintype "passive"))
      (node (ref "LED72") (pin "A") (pinfunction "A_A") (pintype "passive"))
      (node (ref "LED73") (pin "A") (pinfunction "A_A") (pintype "passive"))
      (node (ref "LED74") (pin "A") (pinfunction "A_A") (pintype "passive"))
      (node (ref "LED75") (pin "A") (pinfunction "A_A") (pintype "passive"))
      (node (ref "LED76") (pin "A") (pinfunction "A_A") (pintype "passive"))
      (node (ref "LED77") (pin "A") (pinfunction "A_A") (pintype "passive"))
      (node (ref "LED78") (pin "A") (pinfunction "A_A") (pintype "passive"))
      (node (ref "LED79") (pin "A") (pinfunction "A_A") (pintype "passive"))
      (node (ref "LED80") (pin "A") (pinfunction "A_A") (pintype "passive"))
      (node (ref "R21") (pin "1") (pinfunction "1_1") (pintype "passive"))
    )
    (net (code "114") (name "Net-(LED81-PadA)") (class "Default")
      (node (ref "LED81") (pin "A") (pinfunction "A_A") (pintype "passive"))
      (node (ref "LED82") (pin "A") (pinfunction "A_A") (pintype "passive"))
      (node (ref "LED83") (pin "A") (pinfunction "A_A") (pintype "passive"))
      (node (ref "LED84") (pin "A") (pinfunction "A_A") (pintype "passive"))
      (node (ref "LED85") (pin "A") (pinfunction "A_A") (pintype "passive"))
      (node (ref "LED86") (pin "A") (pinfunction "A_A") (pintype "passive"))
      (node (ref "LED87") (pin "A") (pinfunction "A_A") (pintype "passive"))
      (node (ref "LED88") (pin "A") (pinfunction "A_A") (pintype "passive"))
      (node (ref "LED89") (pin "A") (pinfunction "A_A") (pintype "passive"))
      (node (ref "LED90") (pin "A") (pinfunction "A_A") (pintype "passive"))
      (node (ref "LED91") (pin "A") (pinfunction "A_A") (pintype "passive"))
      (node (ref "LED92") (pin "A") (pinfunction "A_A") (pintype "passive"))
      (node (ref "LED93") (pin "A") (pinfunction "A_A") (pintype "passive"))
      (node (ref "LED94") (pin "A") (pinfunction "A_A") (pintype "passive"))
      (node (ref "LED95") (pin "A") (pinfunction "A_A") (pintype "passive"))
      (node (ref "LED96") (pin "A") (pinfunction "A_A") (pintype "passive"))
      (node (ref "R22") (pin "1") (pinfunction "1_1") (pintype "passive"))
    )
    (net (code "115") (name "Net-(LED100-C)") (class "Default")
      (node (ref "LED100") (pin "K") (pinfunction "C_K") (pintype "passive"))
      (node (ref "LED116") (pin "K") (pinfunction "C_K") (pintype "passive"))
      (node (ref "LED132") (pin "K") (pinfunction "C_K") (pintype "passive"))
      (node (ref "LED148") (pin "K") (pinfunction "C_K") (pintype "passive"))
      (node (ref "LED164") (pin "K") (pinfunction "C_K") (pintype "passive"))
      (node (ref "LED180") (pin "K") (pinfunction "C_K") (pintype "passive"))
      (node (ref "LED196") (pin "K") (pinfunction "C_K") (pintype "passive"))
      (node (ref "LED20") (pin "K") (pinfunction "C_K") (pintype "passive"))
      (node (ref "LED212") (pin "K") (pinfunction "C_K") (pintype "passive"))
      (node (ref "LED228") (pin "K") (pinfunction "C_K") (pintype "passive"))
      (node (ref "LED244") (pin "K") (pinfunction "C_K") (pintype "passive"))
      (node (ref "LED260") (pin "K") (pinfunction "C_K") (pintype "passive"))
      (node (ref "LED276") (pin "K") (pinfunction "C_K") (pintype "passive"))
      (node (ref "LED292") (pin "K") (pinfunction "C_K") (pintype "passive"))
      (node (ref "LED308") (pin "K") (pinfunction "C_K") (pintype "passive"))
      (node (ref "LED324") (pin "K") (pinfunction "C_K") (pintype "passive"))
      (node (ref "LED340") (pin "K") (pinfunction "C_K") (pintype "passive"))
      (node (ref "LED356") (pin "K") (pinfunction "C_K") (pintype "passive"))
      (node (ref "LED36") (pin "K") (pinfunction "C_K") (pintype "passive"))
      (node (ref "LED372") (pin "K") (pinfunction "C_K") (pintype "passive"))
      (node (ref "LED388") (pin "K") (pinfunction "C_K") (pintype "passive"))
      (node (ref "LED4") (pin "K") (pinfunction "C_K") (pintype "passive"))
      (node (ref "LED404") (pin "K") (pinfunction "C_K") (pintype "passive"))
      (node (ref "LED420") (pin "K") (pinfunction "C_K") (pintype "passive"))
      (node (ref "LED436") (pin "K") (pinfunction "C_K") (pintype "passive"))
      (node (ref "LED452") (pin "K") (pinfunction "C_K") (pintype "passive"))
      (node (ref "LED468") (pin "K") (pinfunction "C_K") (pintype "passive"))
      (node (ref "LED484") (pin "K") (pinfunction "C_K") (pintype "passive"))
      (node (ref "LED500") (pin "K") (pinfunction "C_K") (pintype "passive"))
      (node (ref "LED516") (pin "K") (pinfunction "C_K") (pintype "passive"))
      (node (ref "LED52") (pin "K") (pinfunction "C_K") (pintype "passive"))
      (node (ref "LED532") (pin "K") (pinfunction "C_K") (pintype "passive"))
      (node (ref "LED548") (pin "K") (pinfunction "C_K") (pintype "passive"))
      (node (ref "LED564") (pin "K") (pinfunction "C_K") (pintype "passive"))
      (node (ref "LED580") (pin "K") (pinfunction "C_K") (pintype "passive"))
      (node (ref "LED596") (pin "K") (pinfunction "C_K") (pintype "passive"))
      (node (ref "LED612") (pin "K") (pinfunction "C_K") (pintype "passive"))
      (node (ref "LED628") (pin "K") (pinfunction "C_K") (pintype "passive"))
      (node (ref "LED68") (pin "K") (pinfunction "C_K") (pintype "passive"))
      (node (ref "LED84") (pin "K") (pinfunction "C_K") (pintype "passive"))
      (node (ref "U$4") (pin "3") (pinfunction "D_3") (pintype "passive"))
    )
    (net (code "116") (name "Net-(LED100-PadA)") (class "Default")
      (node (ref "LED100") (pin "A") (pinfunction "A_A") (pintype "passive"))
      (node (ref "LED101") (pin "A") (pinfunction "A_A") (pintype "passive"))
      (node (ref "LED102") (pin "A") (pinfunction "A_A") (pintype "passive"))
      (node (ref "LED103") (pin "A") (pinfunction "A_A") (pintype "passive"))
      (node (ref "LED104") (pin "A") (pinfunction "A_A") (pintype "passive"))
      (node (ref "LED105") (pin "A") (pinfunction "A_A") (pintype "passive"))
      (node (ref "LED106") (pin "A") (pinfunction "A_A") (pintype "passive"))
      (node (ref "LED107") (pin "A") (pinfunction "A_A") (pintype "passive"))
      (node (ref "LED108") (pin "A") (pinfunction "A_A") (pintype "passive"))
      (node (ref "LED109") (pin "A") (pinfunction "A_A") (pintype "passive"))
      (node (ref "LED110") (pin "A") (pinfunction "A_A") (pintype "passive"))
      (node (ref "LED111") (pin "A") (pinfunction "A_A") (pintype "passive"))
      (node (ref "LED112") (pin "A") (pinfunction "A_A") (pintype "passive"))
      (node (ref "LED97") (pin "A") (pinfunction "A_A") (pintype "passive"))
      (node (ref "LED98") (pin "A") (pinfunction "A_A") (pintype "passive"))
      (node (ref "LED99") (pin "A") (pinfunction "A_A") (pintype "passive"))
      (node (ref "R23") (pin "1") (pinfunction "1_1") (pintype "passive"))
    )
    (net (code "117") (name "Net-(LED101-C)") (class "Default")
      (node (ref "LED101") (pin "K") (pinfunction "C_K") (pintype "passive"))
      (node (ref "LED117") (pin "K") (pinfunction "C_K") (pintype "passive"))
      (node (ref "LED133") (pin "K") (pinfunction "C_K") (pintype "passive"))
      (node (ref "LED149") (pin "K") (pinfunction "C_K") (pintype "passive"))
      (node (ref "LED165") (pin "K") (pinfunction "C_K") (pintype "passive"))
      (node (ref "LED181") (pin "K") (pinfunction "C_K") (pintype "passive"))
      (node (ref "LED197") (pin "K") (pinfunction "C_K") (pintype "passive"))
      (node (ref "LED21") (pin "K") (pinfunction "C_K") (pintype "passive"))
      (node (ref "LED213") (pin "K") (pinfunction "C_K") (pintype "passive"))
      (node (ref "LED229") (pin "K") (pinfunction "C_K") (pintype "passive"))
      (node (ref "LED245") (pin "K") (pinfunction "C_K") (pintype "passive"))
      (node (ref "LED261") (pin "K") (pinfunction "C_K") (pintype "passive"))
      (node (ref "LED277") (pin "K") (pinfunction "C_K") (pintype "passive"))
      (node (ref "LED293") (pin "K") (pinfunction "C_K") (pintype "passive"))
      (node (ref "LED309") (pin "K") (pinfunction "C_K") (pintype "passive"))
      (node (ref "LED325") (pin "K") (pinfunction "C_K") (pintype "passive"))
      (node (ref "LED341") (pin "K") (pinfunction "C_K") (pintype "passive"))
      (node (ref "LED357") (pin "K") (pinfunction "C_K") (pintype "passive"))
      (node (ref "LED37") (pin "K") (pinfunction "C_K") (pintype "passive"))
      (node (ref "LED373") (pin "K") (pinfunction "C_K") (pintype "passive"))
      (node (ref "LED389") (pin "K") (pinfunction "C_K") (pintype "passive"))
      (node (ref "LED405") (pin "K") (pinfunction "C_K") (pintype "passive"))
      (node (ref "LED421") (pin "K") (pinfunction "C_K") (pintype "passive"))
      (node (ref "LED437") (pin "K") (pinfunction "C_K") (pintype "passive"))
      (node (ref "LED453") (pin "K") (pinfunction "C_K") (pintype "passive"))
      (node (ref "LED469") (pin "K") (pinfunction "C_K") (pintype "passive"))
      (node (ref "LED485") (pin "K") (pinfunction "C_K") (pintype "passive"))
      (node (ref "LED5") (pin "K") (pinfunction "C_K") (pintype "passive"))
      (node (ref "LED501") (pin "K") (pinfunction "C_K") (pintype "passive"))
      (node (ref "LED517") (pin "K") (pinfunction "C_K") (pintype "passive"))
      (node (ref "LED53") (pin "K") (pinfunction "C_K") (pintype "passive"))
      (node (ref "LED533") (pin "K") (pinfunction "C_K") (pintype "passive"))
      (node (ref "LED549") (pin "K") (pinfunction "C_K") (pintype "passive"))
      (node (ref "LED565") (pin "K") (pinfunction "C_K") (pintype "passive"))
      (node (ref "LED581") (pin "K") (pinfunction "C_K") (pintype "passive"))
      (node (ref "LED597") (pin "K") (pinfunction "C_K") (pintype "passive"))
      (node (ref "LED613") (pin "K") (pinfunction "C_K") (pintype "passive"))
      (node (ref "LED629") (pin "K") (pinfunction "C_K") (pintype "passive"))
      (node (ref "LED69") (pin "K") (pinfunction "C_K") (pintype "passive"))
      (node (ref "LED85") (pin "K") (pinfunction "C_K") (pintype "passive"))
      (node (ref "U$5") (pin "3") (pinfunction "D_3") (pintype "passive"))
    )
    (net (code "118") (name "Net-(LED102-C)") (class "Default")
      (node (ref "LED102") (pin "K") (pinfunction "C_K") (pintype "passive"))
      (node (ref "LED118") (pin "K") (pinfunction "C_K") (pintype "passive"))
      (node (ref "LED134") (pin "K") (pinfunction "C_K") (pintype "passive"))
      (node (ref "LED150") (pin "K") (pinfunction "C_K") (pintype "passive"))
      (node (ref "LED166") (pin "K") (pinfunction "C_K") (pintype "passive"))
      (node (ref "LED182") (pin "K") (pinfunction "C_K") (pintype "passive"))
      (node (ref "LED198") (pin "K") (pinfunction "C_K") (pintype "passive"))
      (node (ref "LED214") (pin "K") (pinfunction "C_K") (pintype "passive"))
      (node (ref "LED22") (pin "K") (pinfunction "C_K") (pintype "passive"))
      (node (ref "LED230") (pin "K") (pinfunction "C_K") (pintype "passive"))
      (node (ref "LED246") (pin "K") (pinfunction "C_K") (pintype "passive"))
      (node (ref "LED262") (pin "K") (pinfunction "C_K") (pintype "passive"))
      (node (ref "LED278") (pin "K") (pinfunction "C_K") (pintype "passive"))
      (node (ref "LED294") (pin "K") (pinfunction "C_K") (pintype "passive"))
      (node (ref "LED310") (pin "K") (pinfunction "C_K") (pintype "passive"))
      (node (ref "LED326") (pin "K") (pinfunction "C_K") (pintype "passive"))
      (node (ref "LED342") (pin "K") (pinfunction "C_K") (pintype "passive"))
      (node (ref "LED358") (pin "K") (pinfunction "C_K") (pintype "passive"))
      (node (ref "LED374") (pin "K") (pinfunction "C_K") (pintype "passive"))
      (node (ref "LED38") (pin "K") (pinfunction "C_K") (pintype "passive"))
      (node (ref "LED390") (pin "K") (pinfunction "C_K") (pintype "passive"))
      (node (ref "LED406") (pin "K") (pinfunction "C_K") (pintype "passive"))
      (node (ref "LED422") (pin "K") (pinfunction "C_K") (pintype "passive"))
      (node (ref "LED438") (pin "K") (pinfunction "C_K") (pintype "passive"))
      (node (ref "LED454") (pin "K") (pinfunction "C_K") (pintype "passive"))
      (node (ref "LED470") (pin "K") (pinfunction "C_K") (pintype "passive"))
      (node (ref "LED486") (pin "K") (pinfunction "C_K") (pintype "passive"))
      (node (ref "LED502") (pin "K") (pinfunction "C_K") (pintype "passive"))
      (node (ref "LED518") (pin "K") (pinfunction "C_K") (pintype "passive"))
      (node (ref "LED534") (pin "K") (pinfunction "C_K") (pintype "passive"))
      (node (ref "LED54") (pin "K") (pinfunction "C_K") (pintype "passive"))
      (node (ref "LED550") (pin "K") (pinfunction "C_K") (pintype "passive"))
      (node (ref "LED566") (pin "K") (pinfunction "C_K") (pintype "passive"))
      (node (ref "LED582") (pin "K") (pinfunction "C_K") (pintype "passive"))
      (node (ref "LED598") (pin "K") (pinfunction "C_K") (pintype "passive"))
      (node (ref "LED6") (pin "K") (pinfunction "C_K") (pintype "passive"))
      (node (ref "LED614") (pin "K") (pinfunction "C_K") (pintype "passive"))
      (node (ref "LED630") (pin "K") (pinfunction "C_K") (pintype "passive"))
      (node (ref "LED70") (pin "K") (pinfunction "C_K") (pintype "passive"))
      (node (ref "LED86") (pin "K") (pinfunction "C_K") (pintype "passive"))
      (node (ref "U$6") (pin "3") (pinfunction "D_3") (pintype "passive"))
    )
    (net (code "119") (name "Net-(LED103-C)") (class "Default")
      (node (ref "LED103") (pin "K") (pinfunction "C_K") (pintype "passive"))
      (node (ref "LED119") (pin "K") (pinfunction "C_K") (pintype "passive"))
      (node (ref "LED135") (pin "K") (pinfunction "C_K") (pintype "passive"))
      (node (ref "LED151") (pin "K") (pinfunction "C_K") (pintype "passive"))
      (node (ref "LED167") (pin "K") (pinfunction "C_K") (pintype "passive"))
      (node (ref "LED183") (pin "K") (pinfunction "C_K") (pintype "passive"))
      (node (ref "LED199") (pin "K") (pinfunction "C_K") (pintype "passive"))
      (node (ref "LED215") (pin "K") (pinfunction "C_K") (pintype "passive"))
      (node (ref "LED23") (pin "K") (pinfunction "C_K") (pintype "passive"))
      (node (ref "LED231") (pin "K") (pinfunction "C_K") (pintype "passive"))
      (node (ref "LED247") (pin "K") (pinfunction "C_K") (pintype "passive"))
      (node (ref "LED263") (pin "K") (pinfunction "C_K") (pintype "passive"))
      (node (ref "LED279") (pin "K") (pinfunction "C_K") (pintype "passive"))
      (node (ref "LED295") (pin "K") (pinfunction "C_K") (pintype "passive"))
      (node (ref "LED311") (pin "K") (pinfunction "C_K") (pintype "passive"))
      (node (ref "LED327") (pin "K") (pinfunction "C_K") (pintype "passive"))
      (node (ref "LED343") (pin "K") (pinfunction "C_K") (pintype "passive"))
      (node (ref "LED359") (pin "K") (pinfunction "C_K") (pintype "passive"))
      (node (ref "LED375") (pin "K") (pinfunction "C_K") (pintype "passive"))
      (node (ref "LED39") (pin "K") (pinfunction "C_K") (pintype "passive"))
      (node (ref "LED391") (pin "K") (pinfunction "C_K") (pintype "passive"))
      (node (ref "LED407") (pin "K") (pinfunction "C_K") (pintype "passive"))
      (node (ref "LED423") (pin "K") (pinfunction "C_K") (pintype "passive"))
      (node (ref "LED439") (pin "K") (pinfunction "C_K") (pintype "passive"))
      (node (ref "LED455") (pin "K") (pinfunction "C_K") (pintype "passive"))
      (node (ref "LED471") (pin "K") (pinfunction "C_K") (pintype "passive"))
      (node (ref "LED487") (pin "K") (pinfunction "C_K") (pintype "passive"))
      (node (ref "LED503") (pin "K") (pinfunction "C_K") (pintype "passive"))
      (node (ref "LED519") (pin "K") (pinfunction "C_K") (pintype "passive"))
      (node (ref "LED535") (pin "K") (pinfunction "C_K") (pintype "passive"))
      (node (ref "LED55") (pin "K") (pinfunction "C_K") (pintype "passive"))
      (node (ref "LED551") (pin "K") (pinfunction "C_K") (pintype "passive"))
      (node (ref "LED567") (pin "K") (pinfunction "C_K") (pintype "passive"))
      (node (ref "LED583") (pin "K") (pinfunction "C_K") (pintype "passive"))
      (node (ref "LED599") (pin "K") (pinfunction "C_K") (pintype "passive"))
      (node (ref "LED615") (pin "K") (pinfunction "C_K") (pintype "passive"))
      (node (ref "LED631") (pin "K") (pinfunction "C_K") (pintype "passive"))
      (node (ref "LED7") (pin "K") (pinfunction "C_K") (pintype "passive"))
      (node (ref "LED71") (pin "K") (pinfunction "C_K") (pintype "passive"))
      (node (ref "LED87") (pin "K") (pinfunction "C_K") (pintype "passive"))
      (node (ref "U$7") (pin "3") (pinfunction "D_3") (pintype "passive"))
    )
    (net (code "120") (name "Net-(LED104-C)") (class "Default")
      (node (ref "LED104") (pin "K") (pinfunction "C_K") (pintype "passive"))
      (node (ref "LED120") (pin "K") (pinfunction "C_K") (pintype "passive"))
      (node (ref "LED136") (pin "K") (pinfunction "C_K") (pintype "passive"))
      (node (ref "LED152") (pin "K") (pinfunction "C_K") (pintype "passive"))
      (node (ref "LED168") (pin "K") (pinfunction "C_K") (pintype "passive"))
      (node (ref "LED184") (pin "K") (pinfunction "C_K") (pintype "passive"))
      (node (ref "LED200") (pin "K") (pinfunction "C_K") (pintype "passive"))
      (node (ref "LED216") (pin "K") (pinfunction "C_K") (pintype "passive"))
      (node (ref "LED232") (pin "K") (pinfunction "C_K") (pintype "passive"))
      (node (ref "LED24") (pin "K") (pinfunction "C_K") (pintype "passive"))
      (node (ref "LED248") (pin "K") (pinfunction "C_K") (pintype "passive"))
      (node (ref "LED264") (pin "K") (pinfunction "C_K") (pintype "passive"))
      (node (ref "LED280") (pin "K") (pinfunction "C_K") (pintype "passive"))
      (node (ref "LED296") (pin "K") (pinfunction "C_K") (pintype "passive"))
      (node (ref "LED312") (pin "K") (pinfunction "C_K") (pintype "passive"))
      (node (ref "LED328") (pin "K") (pinfunction "C_K") (pintype "passive"))
      (node (ref "LED344") (pin "K") (pinfunction "C_K") (pintype "passive"))
      (node (ref "LED360") (pin "K") (pinfunction "C_K") (pintype "passive"))
      (node (ref "LED376") (pin "K") (pinfunction "C_K") (pintype "passive"))
      (node (ref "LED392") (pin "K") (pinfunction "C_K") (pintype "passive"))
      (node (ref "LED40") (pin "K") (pinfunction "C_K") (pintype "passive"))
      (node (ref "LED408") (pin "K") (pinfunction "C_K") (pintype "passive"))
      (node (ref "LED424") (pin "K") (pinfunction "C_K") (pintype "passive"))
      (node (ref "LED440") (pin "K") (pinfunction "C_K") (pintype "passive"))
      (node (ref "LED456") (pin "K") (pinfunction "C_K") (pintype "passive"))
      (node (ref "LED472") (pin "K") (pinfunction "C_K") (pintype "passive"))
      (node (ref "LED488") (pin "K") (pinfunction "C_K") (pintype "passive"))
      (node (ref "LED504") (pin "K") (pinfunction "C_K") (pintype "passive"))
      (node (ref "LED520") (pin "K") (pinfunction "C_K") (pintype "passive"))
      (node (ref "LED536") (pin "K") (pinfunction "C_K") (pintype "passive"))
      (node (ref "LED552") (pin "K") (pinfunction "C_K") (pintype "passive"))
      (node (ref "LED56") (pin "K") (pinfunction "C_K") (pintype "passive"))
      (node (ref "LED568") (pin "K") (pinfunction "C_K") (pintype "passive"))
      (node (ref "LED584") (pin "K") (pinfunction "C_K") (pintype "passive"))
      (node (ref "LED600") (pin "K") (pinfunction "C_K") (pintype "passive"))
      (node (ref "LED616") (pin "K") (pinfunction "C_K") (pintype "passive"))
      (node (ref "LED632") (pin "K") (pinfunction "C_K") (pintype "passive"))
      (node (ref "LED72") (pin "K") (pinfunction "C_K") (pintype "passive"))
      (node (ref "LED8") (pin "K") (pinfunction "C_K") (pintype "passive"))
      (node (ref "LED88") (pin "K") (pinfunction "C_K") (pintype "passive"))
      (node (ref "U$8") (pin "3") (pinfunction "D_3") (pintype "passive"))
    )
    (net (code "121") (name "Net-(LED105-C)") (class "Default")
      (node (ref "LED105") (pin "K") (pinfunction "C_K") (pintype "passive"))
      (node (ref "LED121") (pin "K") (pinfunction "C_K") (pintype "passive"))
      (node (ref "LED137") (pin "K") (pinfunction "C_K") (pintype "passive"))
      (node (ref "LED153") (pin "K") (pinfunction "C_K") (pintype "passive"))
      (node (ref "LED169") (pin "K") (pinfunction "C_K") (pintype "passive"))
      (node (ref "LED185") (pin "K") (pinfunction "C_K") (pintype "passive"))
      (node (ref "LED201") (pin "K") (pinfunction "C_K") (pintype "passive"))
      (node (ref "LED217") (pin "K") (pinfunction "C_K") (pintype "passive"))
      (node (ref "LED233") (pin "K") (pinfunction "C_K") (pintype "passive"))
      (node (ref "LED249") (pin "K") (pinfunction "C_K") (pintype "passive"))
      (node (ref "LED25") (pin "K") (pinfunction "C_K") (pintype "passive"))
      (node (ref "LED265") (pin "K") (pinfunction "C_K") (pintype "passive"))
      (node (ref "LED281") (pin "K") (pinfunction "C_K") (pintype "passive"))
      (node (ref "LED297") (pin "K") (pinfunction "C_K") (pintype "passive"))
      (node (ref "LED313") (pin "K") (pinfunction "C_K") (pintype "passive"))
      (node (ref "LED329") (pin "K") (pinfunction "C_K") (pintype "passive"))
      (node (ref "LED345") (pin "K") (pinfunction "C_K") (pintype "passive"))
      (node (ref "LED361") (pin "K") (pinfunction "C_K") (pintype "passive"))
      (node (ref "LED377") (pin "K") (pinfunction "C_K") (pintype "passive"))
      (node (ref "LED393") (pin "K") (pinfunction "C_K") (pintype "passive"))
      (node (ref "LED409") (pin "K") (pinfunction "C_K") (pintype "passive"))
      (node (ref "LED41") (pin "K") (pinfunction "C_K") (pintype "passive"))
      (node (ref "LED425") (pin "K") (pinfunction "C_K") (pintype "passive"))
      (node (ref "LED441") (pin "K") (pinfunction "C_K") (pintype "passive"))
      (node (ref "LED457") (pin "K") (pinfunction "C_K") (pintype "passive"))
      (node (ref "LED473") (pin "K") (pinfunction "C_K") (pintype "passive"))
      (node (ref "LED489") (pin "K") (pinfunction "C_K") (pintype "passive"))
      (node (ref "LED505") (pin "K") (pinfunction "C_K") (pintype "passive"))
      (node (ref "LED521") (pin "K") (pinfunction "C_K") (pintype "passive"))
      (node (ref "LED537") (pin "K") (pinfunction "C_K") (pintype "passive"))
      (node (ref "LED553") (pin "K") (pinfunction "C_K") (pintype "passive"))
      (node (ref "LED569") (pin "K") (pinfunction "C_K") (pintype "passive"))
      (node (ref "LED57") (pin "K") (pinfunction "C_K") (pintype "passive"))
      (node (ref "LED585") (pin "K") (pinfunction "C_K") (pintype "passive"))
      (node (ref "LED601") (pin "K") (pinfunction "C_K") (pintype "passive"))
      (node (ref "LED617") (pin "K") (pinfunction "C_K") (pintype "passive"))
      (node (ref "LED633") (pin "K") (pinfunction "C_K") (pintype "passive"))
      (node (ref "LED73") (pin "K") (pinfunction "C_K") (pintype "passive"))
      (node (ref "LED89") (pin "K") (pinfunction "C_K") (pintype "passive"))
      (node (ref "LED9") (pin "K") (pinfunction "C_K") (pintype "passive"))
      (node (ref "U$9") (pin "3") (pinfunction "D_3") (pintype "passive"))
    )
    (net (code "122") (name "Net-(LED107-C)") (class "Default")
      (node (ref "LED107") (pin "K") (pinfunction "C_K") (pintype "passive"))
      (node (ref "LED11") (pin "K") (pinfunction "C_K") (pintype "passive"))
      (node (ref "LED123") (pin "K") (pinfunction "C_K") (pintype "passive"))
      (node (ref "LED139") (pin "K") (pinfunction "C_K") (pintype "passive"))
      (node (ref "LED155") (pin "K") (pinfunction "C_K") (pintype "passive"))
      (node (ref "LED171") (pin "K") (pinfunction "C_K") (pintype "passive"))
      (node (ref "LED187") (pin "K") (pinfunction "C_K") (pintype "passive"))
      (node (ref "LED203") (pin "K") (pinfunction "C_K") (pintype "passive"))
      (node (ref "LED219") (pin "K") (pinfunction "C_K") (pintype "passive"))
      (node (ref "LED235") (pin "K") (pinfunction "C_K") (pintype "passive"))
      (node (ref "LED251") (pin "K") (pinfunction "C_K") (pintype "passive"))
      (node (ref "LED267") (pin "K") (pinfunction "C_K") (pintype "passive"))
      (node (ref "LED27") (pin "K") (pinfunction "C_K") (pintype "passive"))
      (node (ref "LED283") (pin "K") (pinfunction "C_K") (pintype "passive"))
      (node (ref "LED299") (pin "K") (pinfunction "C_K") (pintype "passive"))
      (node (ref "LED315") (pin "K") (pinfunction "C_K") (pintype "passive"))
      (node (ref "LED331") (pin "K") (pinfunction "C_K") (pintype "passive"))
      (node (ref "LED347") (pin "K") (pinfunction "C_K") (pintype "passive"))
      (node (ref "LED363") (pin "K") (pinfunction "C_K") (pintype "passive"))
      (node (ref "LED379") (pin "K") (pinfunction "C_K") (pintype "passive"))
      (node (ref "LED395") (pin "K") (pinfunction "C_K") (pintype "passive"))
      (node (ref "LED411") (pin "K") (pinfunction "C_K") (pintype "passive"))
      (node (ref "LED427") (pin "K") (pinfunction "C_K") (pintype "passive"))
      (node (ref "LED43") (pin "K") (pinfunction "C_K") (pintype "passive"))
      (node (ref "LED443") (pin "K") (pinfunction "C_K") (pintype "passive"))
      (node (ref "LED459") (pin "K") (pinfunction "C_K") (pintype "passive"))
      (node (ref "LED475") (pin "K") (pinfunction "C_K") (pintype "passive"))
      (node (ref "LED491") (pin "K") (pinfunction "C_K") (pintype "passive"))
      (node (ref "LED507") (pin "K") (pinfunction "C_K") (pintype "passive"))
      (node (ref "LED523") (pin "K") (pinfunction "C_K") (pintype "passive"))
      (node (ref "LED539") (pin "K") (pinfunction "C_K") (pintype "passive"))
      (node (ref "LED555") (pin "K") (pinfunction "C_K") (pintype "passive"))
      (node (ref "LED571") (pin "K") (pinfunction "C_K") (pintype "passive"))
      (node (ref "LED587") (pin "K") (pinfunction "C_K") (pintype "passive"))
      (node (ref "LED59") (pin "K") (pinfunction "C_K") (pintype "passive"))
      (node (ref "LED603") (pin "K") (pinfunction "C_K") (pintype "passive"))
      (node (ref "LED619") (pin "K") (pinfunction "C_K") (pintype "passive"))
      (node (ref "LED635") (pin "K") (pinfunction "C_K") (pintype "passive"))
      (node (ref "LED75") (pin "K") (pinfunction "C_K") (pintype "passive"))
      (node (ref "LED91") (pin "K") (pinfunction "C_K") (pintype "passive"))
      (node (ref "U$11") (pin "3") (pinfunction "D_3") (pintype "passive"))
    )
    (net (code "123") (name "Net-(LED108-C)") (class "Default")
      (node (ref "LED108") (pin "K") (pinfunction "C_K") (pintype "passive"))
      (node (ref "LED12") (pin "K") (pinfunction "C_K") (pintype "passive"))
      (node (ref "LED124") (pin "K") (pinfunction "C_K") (pintype "passive"))
      (node (ref "LED140") (pin "K") (pinfunction "C_K") (pintype "passive"))
      (node (ref "LED156") (pin "K") (pinfunction "C_K") (pintype "passive"))
      (node (ref "LED172") (pin "K") (pinfunction "C_K") (pintype "passive"))
      (node (ref "LED188") (pin "K") (pinfunction "C_K") (pintype "passive"))
      (node (ref "LED204") (pin "K") (pinfunction "C_K") (pintype "passive"))
      (node (ref "LED220") (pin "K") (pinfunction "C_K") (pintype "passive"))
      (node (ref "LED236") (pin "K") (pinfunction "C_K") (pintype "passive"))
      (node (ref "LED252") (pin "K") (pinfunction "C_K") (pintype "passive"))
      (node (ref "LED268") (pin "K") (pinfunction "C_K") (pintype "passive"))
      (node (ref "LED28") (pin "K") (pinfunction "C_K") (pintype "passive"))
      (node (ref "LED284") (pin "K") (pinfunction "C_K") (pintype "passive"))
      (node (ref "LED300") (pin "K") (pinfunction "C_K") (pintype "passive"))
      (node (ref "LED316") (pin "K") (pinfunction "C_K") (pintype "passive"))
      (node (ref "LED332") (pin "K") (pinfunction "C_K") (pintype "passive"))
      (node (ref "LED348") (pin "K") (pinfunction "C_K") (pintype "passive"))
      (node (ref "LED364") (pin "K") (pinfunction "C_K") (pintype "passive"))
      (node (ref "LED380") (pin "K") (pinfunction "C_K") (pintype "passive"))
      (node (ref "LED396") (pin "K") (pinfunction "C_K") (pintype "passive"))
      (node (ref "LED412") (pin "K") (pinfunction "C_K") (pintype "passive"))
      (node (ref "LED428") (pin "K") (pinfunction "C_K") (pintype "passive"))
      (node (ref "LED44") (pin "K") (pinfunction "C_K") (pintype "passive"))
      (node (ref "LED444") (pin "K") (pinfunction "C_K") (pintype "passive"))
      (node (ref "LED460") (pin "K") (pinfunction "C_K") (pintype "passive"))
      (node (ref "LED476") (pin "K") (pinfunction "C_K") (pintype "passive"))
      (node (ref "LED492") (pin "K") (pinfunction "C_K") (pintype "passive"))
      (node (ref "LED508") (pin "K") (pinfunction "C_K") (pintype "passive"))
      (node (ref "LED524") (pin "K") (pinfunction "C_K") (pintype "passive"))
      (node (ref "LED540") (pin "K") (pinfunction "C_K") (pintype "passive"))
      (node (ref "LED556") (pin "K") (pinfunction "C_K") (pintype "passive"))
      (node (ref "LED572") (pin "K") (pinfunction "C_K") (pintype "passive"))
      (node (ref "LED588") (pin "K") (pinfunction "C_K") (pintype "passive"))
      (node (ref "LED60") (pin "K") (pinfunction "C_K") (pintype "passive"))
      (node (ref "LED604") (pin "K") (pinfunction "C_K") (pintype "passive"))
      (node (ref "LED620") (pin "K") (pinfunction "C_K") (pintype "passive"))
      (node (ref "LED636") (pin "K") (pinfunction "C_K") (pintype "passive"))
      (node (ref "LED76") (pin "K") (pinfunction "C_K") (pintype "passive"))
      (node (ref "LED92") (pin "K") (pinfunction "C_K") (pintype "passive"))
      (node (ref "U$12") (pin "3") (pinfunction "D_3") (pintype "passive"))
    )
    (net (code "124") (name "Net-(LED109-C)") (class "Default")
      (node (ref "LED109") (pin "K") (pinfunction "C_K") (pintype "passive"))
      (node (ref "LED125") (pin "K") (pinfunction "C_K") (pintype "passive"))
      (node (ref "LED13") (pin "K") (pinfunction "C_K") (pintype "passive"))
      (node (ref "LED141") (pin "K") (pinfunction "C_K") (pintype "passive"))
      (node (ref "LED157") (pin "K") (pinfunction "C_K") (pintype "passive"))
      (node (ref "LED173") (pin "K") (pinfunction "C_K") (pintype "passive"))
      (node (ref "LED189") (pin "K") (pinfunction "C_K") (pintype "passive"))
      (node (ref "LED205") (pin "K") (pinfunction "C_K") (pintype "passive"))
      (node (ref "LED221") (pin "K") (pinfunction "C_K") (pintype "passive"))
      (node (ref "LED237") (pin "K") (pinfunction "C_K") (pintype "passive"))
      (node (ref "LED253") (pin "K") (pinfunction "C_K") (pintype "passive"))
      (node (ref "LED269") (pin "K") (pinfunction "C_K") (pintype "passive"))
      (node (ref "LED285") (pin "K") (pinfunction "C_K") (pintype "passive"))
      (node (ref "LED29") (pin "K") (pinfunction "C_K") (pintype "passive"))
      (node (ref "LED301") (pin "K") (pinfunction "C_K") (pintype "passive"))
      (node (ref "LED317") (pin "K") (pinfunction "C_K") (pintype "passive"))
      (node (ref "LED333") (pin "K") (pinfunction "C_K") (pintype "passive"))
      (node (ref "LED349") (pin "K") (pinfunction "C_K") (pintype "passive"))
      (node (ref "LED365") (pin "K") (pinfunction "C_K") (pintype "passive"))
      (node (ref "LED381") (pin "K") (pinfunction "C_K") (pintype "passive"))
      (node (ref "LED397") (pin "K") (pinfunction "C_K") (pintype "passive"))
      (node (ref "LED413") (pin "K") (pinfunction "C_K") (pintype "passive"))
      (node (ref "LED429") (pin "K") (pinfunction "C_K") (pintype "passive"))
      (node (ref "LED445") (pin "K") (pinfunction "C_K") (pintype "passive"))
      (node (ref "LED45") (pin "K") (pinfunction "C_K") (pintype "passive"))
      (node (ref "LED461") (pin "K") (pinfunction "C_K") (pintype "passive"))
      (node (ref "LED477") (pin "K") (pinfunction "C_K") (pintype "passive"))
      (node (ref "LED493") (pin "K") (pinfunction "C_K") (pintype "passive"))
      (node (ref "LED509") (pin "K") (pinfunction "C_K") (pintype "passive"))
      (node (ref "LED525") (pin "K") (pinfunction "C_K") (pintype "passive"))
      (node (ref "LED541") (pin "K") (pinfunction "C_K") (pintype "passive"))
      (node (ref "LED557") (pin "K") (pinfunction "C_K") (pintype "passive"))
      (node (ref "LED573") (pin "K") (pinfunction "C_K") (pintype "passive"))
      (node (ref "LED589") (pin "K") (pinfunction "C_K") (pintype "passive"))
      (node (ref "LED605") (pin "K") (pinfunction "C_K") (pintype "passive"))
      (node (ref "LED61") (pin "K") (pinfunction "C_K") (pintype "passive"))
      (node (ref "LED621") (pin "K") (pinfunction "C_K") (pintype "passive"))
      (node (ref "LED637") (pin "K") (pinfunction "C_K") (pintype "passive"))
      (node (ref "LED77") (pin "K") (pinfunction "C_K") (pintype "passive"))
      (node (ref "LED93") (pin "K") (pinfunction "C_K") (pintype "passive"))
      (node (ref "U$13") (pin "3") (pinfunction "D_3") (pintype "passive"))
    )
    (net (code "125") (name "Net-(LED110-C)") (class "Default")
      (node (ref "LED110") (pin "K") (pinfunction "C_K") (pintype "passive"))
      (node (ref "LED126") (pin "K") (pinfunction "C_K") (pintype "passive"))
      (node (ref "LED14") (pin "K") (pinfunction "C_K") (pintype "passive"))
      (node (ref "LED142") (pin "K") (pinfunction "C_K") (pintype "passive"))
      (node (ref "LED158") (pin "K") (pinfunction "C_K") (pintype "passive"))
      (node (ref "LED174") (pin "K") (pinfunction "C_K") (pintype "passive"))
      (node (ref "LED190") (pin "K") (pinfunction "C_K") (pintype "passive"))
      (node (ref "LED206") (pin "K") (pinfunction "C_K") (pintype "passive"))
      (node (ref "LED222") (pin "K") (pinfunction "C_K") (pintype "passive"))
      (node (ref "LED238") (pin "K") (pinfunction "C_K") (pintype "passive"))
      (node (ref "LED254") (pin "K") (pinfunction "C_K") (pintype "passive"))
      (node (ref "LED270") (pin "K") (pinfunction "C_K") (pintype "passive"))
      (node (ref "LED286") (pin "K") (pinfunction "C_K") (pintype "passive"))
      (node (ref "LED30") (pin "K") (pinfunction "C_K") (pintype "passive"))
      (node (ref "LED302") (pin "K") (pinfunction "C_K") (pintype "passive"))
      (node (ref "LED318") (pin "K") (pinfunction "C_K") (pintype "passive"))
      (node (ref "LED334") (pin "K") (pinfunction "C_K") (pintype "passive"))
      (node (ref "LED350") (pin "K") (pinfunction "C_K") (pintype "passive"))
      (node (ref "LED366") (pin "K") (pinfunction "C_K") (pintype "passive"))
      (node (ref "LED382") (pin "K") (pinfunction "C_K") (pintype "passive"))
      (node (ref "LED398") (pin "K") (pinfunction "C_K") (pintype "passive"))
      (node (ref "LED414") (pin "K") (pinfunction "C_K") (pintype "passive"))
      (node (ref "LED430") (pin "K") (pinfunction "C_K") (pintype "passive"))
      (node (ref "LED446") (pin "K") (pinfunction "C_K") (pintype "passive"))
      (node (ref "LED46") (pin "K") (pinfunction "C_K") (pintype "passive"))
      (node (ref "LED462") (pin "K") (pinfunction "C_K") (pintype "passive"))
      (node (ref "LED478") (pin "K") (pinfunction "C_K") (pintype "passive"))
      (node (ref "LED494") (pin "K") (pinfunction "C_K") (pintype "passive"))
      (node (ref "LED510") (pin "K") (pinfunction "C_K") (pintype "passive"))
      (node (ref "LED526") (pin "K") (pinfunction "C_K") (pintype "passive"))
      (node (ref "LED542") (pin "K") (pinfunction "C_K") (pintype "passive"))
      (node (ref "LED558") (pin "K") (pinfunction "C_K") (pintype "passive"))
      (node (ref "LED574") (pin "K") (pinfunction "C_K") (pintype "passive"))
      (node (ref "LED590") (pin "K") (pinfunction "C_K") (pintype "passive"))
      (node (ref "LED606") (pin "K") (pinfunction "C_K") (pintype "passive"))
      (node (ref "LED62") (pin "K") (pinfunction "C_K") (pintype "passive"))
      (node (ref "LED622") (pin "K") (pinfunction "C_K") (pintype "passive"))
      (node (ref "LED638") (pin "K") (pinfunction "C_K") (pintype "passive"))
      (node (ref "LED78") (pin "K") (pinfunction "C_K") (pintype "passive"))
      (node (ref "LED94") (pin "K") (pinfunction "C_K") (pintype "passive"))
      (node (ref "U$14") (pin "3") (pinfunction "D_3") (pintype "passive"))
    )
    (net (code "126") (name "Net-(LED111-C)") (class "Default")
      (node (ref "LED111") (pin "K") (pinfunction "C_K") (pintype "passive"))
      (node (ref "LED127") (pin "K") (pinfunction "C_K") (pintype "passive"))
      (node (ref "LED143") (pin "K") (pinfunction "C_K") (pintype "passive"))
      (node (ref "LED15") (pin "K") (pinfunction "C_K") (pintype "passive"))
      (node (ref "LED159") (pin "K") (pinfunction "C_K") (pintype "passive"))
      (node (ref "LED175") (pin "K") (pinfunction "C_K") (pintype "passive"))
      (node (ref "LED191") (pin "K") (pinfunction "C_K") (pintype "passive"))
      (node (ref "LED207") (pin "K") (pinfunction "C_K") (pintype "passive"))
      (node (ref "LED223") (pin "K") (pinfunction "C_K") (pintype "passive"))
      (node (ref "LED239") (pin "K") (pinfunction "C_K") (pintype "passive"))
      (node (ref "LED255") (pin "K") (pinfunction "C_K") (pintype "passive"))
      (node (ref "LED271") (pin "K") (pinfunction "C_K") (pintype "passive"))
      (node (ref "LED287") (pin "K") (pinfunction "C_K") (pintype "passive"))
      (node (ref "LED303") (pin "K") (pinfunction "C_K") (pintype "passive"))
      (node (ref "LED31") (pin "K") (pinfunction "C_K") (pintype "passive"))
      (node (ref "LED319") (pin "K") (pinfunction "C_K") (pintype "passive"))
      (node (ref "LED335") (pin "K") (pinfunction "C_K") (pintype "passive"))
      (node (ref "LED351") (pin "K") (pinfunction "C_K") (pintype "passive"))
      (node (ref "LED367") (pin "K") (pinfunction "C_K") (pintype "passive"))
      (node (ref "LED383") (pin "K") (pinfunction "C_K") (pintype "passive"))
      (node (ref "LED399") (pin "K") (pinfunction "C_K") (pintype "passive"))
      (node (ref "LED415") (pin "K") (pinfunction "C_K") (pintype "passive"))
      (node (ref "LED431") (pin "K") (pinfunction "C_K") (pintype "passive"))
      (node (ref "LED447") (pin "K") (pinfunction "C_K") (pintype "passive"))
      (node (ref "LED463") (pin "K") (pinfunction "C_K") (pintype "passive"))
      (node (ref "LED47") (pin "K") (pinfunction "C_K") (pintype "passive"))
      (node (ref "LED479") (pin "K") (pinfunction "C_K") (pintype "passive"))
      (node (ref "LED495") (pin "K") (pinfunction "C_K") (pintype "passive"))
      (node (ref "LED511") (pin "K") (pinfunction "C_K") (pintype "passive"))
      (node (ref "LED527") (pin "K") (pinfunction "C_K") (pintype "passive"))
      (node (ref "LED543") (pin "K") (pinfunction "C_K") (pintype "passive"))
      (node (ref "LED559") (pin "K") (pinfunction "C_K") (pintype "passive"))
      (node (ref "LED575") (pin "K") (pinfunction "C_K") (pintype "passive"))
      (node (ref "LED591") (pin "K") (pinfunction "C_K") (pintype "passive"))
      (node (ref "LED607") (pin "K") (pinfunction "C_K") (pintype "passive"))
      (node (ref "LED623") (pin "K") (pinfunction "C_K") (pintype "passive"))
      (node (ref "LED63") (pin "K") (pinfunction "C_K") (pintype "passive"))
      (node (ref "LED639") (pin "K") (pinfunction "C_K") (pintype "passive"))
      (node (ref "LED79") (pin "K") (pinfunction "C_K") (pintype "passive"))
      (node (ref "LED95") (pin "K") (pinfunction "C_K") (pintype "passive"))
      (node (ref "U$15") (pin "3") (pinfunction "D_3") (pintype "passive"))
    )
    (net (code "127") (name "Net-(LED112-C)") (class "Default")
      (node (ref "LED112") (pin "K") (pinfunction "C_K") (pintype "passive"))
      (node (ref "LED128") (pin "K") (pinfunction "C_K") (pintype "passive"))
      (node (ref "LED144") (pin "K") (pinfunction "C_K") (pintype "passive"))
      (node (ref "LED16") (pin "K") (pinfunction "C_K") (pintype "passive"))
      (node (ref "LED160") (pin "K") (pinfunction "C_K") (pintype "passive"))
      (node (ref "LED176") (pin "K") (pinfunction "C_K") (pintype "passive"))
      (node (ref "LED192") (pin "K") (pinfunction "C_K") (pintype "passive"))
      (node (ref "LED208") (pin "K") (pinfunction "C_K") (pintype "passive"))
      (node (ref "LED224") (pin "K") (pinfunction "C_K") (pintype "passive"))
      (node (ref "LED240") (pin "K") (pinfunction "C_K") (pintype "passive"))
      (node (ref "LED256") (pin "K") (pinfunction "C_K") (pintype "passive"))
      (node (ref "LED272") (pin "K") (pinfunction "C_K") (pintype "passive"))
      (node (ref "LED288") (pin "K") (pinfunction "C_K") (pintype "passive"))
      (node (ref "LED304") (pin "K") (pinfunction "C_K") (pintype "passive"))
      (node (ref "LED32") (pin "K") (pinfunction "C_K") (pintype "passive"))
      (node (ref "LED320") (pin "K") (pinfunction "C_K") (pintype "passive"))
      (node (ref "LED336") (pin "K") (pinfunction "C_K") (pintype "passive"))
      (node (ref "LED352") (pin "K") (pinfunction "C_K") (pintype "passive"))
      (node (ref "LED368") (pin "K") (pinfunction "C_K") (pintype "passive"))
      (node (ref "LED384") (pin "K") (pinfunction "C_K") (pintype "passive"))
      (node (ref "LED400") (pin "K") (pinfunction "C_K") (pintype "passive"))
      (node (ref "LED416") (pin "K") (pinfunction "C_K") (pintype "passive"))
      (node (ref "LED432") (pin "K") (pinfunction "C_K") (pintype "passive"))
      (node (ref "LED448") (pin "K") (pinfunction "C_K") (pintype "passive"))
      (node (ref "LED464") (pin "K") (pinfunction "C_K") (pintype "passive"))
      (node (ref "LED48") (pin "K") (pinfunction "C_K") (pintype "passive"))
      (node (ref "LED480") (pin "K") (pinfunction "C_K") (pintype "passive"))
      (node (ref "LED496") (pin "K") (pinfunction "C_K") (pintype "passive"))
      (node (ref "LED512") (pin "K") (pinfunction "C_K") (pintype "passive"))
      (node (ref "LED528") (pin "K") (pinfunction "C_K") (pintype "passive"))
      (node (ref "LED544") (pin "K") (pinfunction "C_K") (pintype "passive"))
      (node (ref "LED560") (pin "K") (pinfunction "C_K") (pintype "passive"))
      (node (ref "LED576") (pin "K") (pinfunction "C_K") (pintype "passive"))
      (node (ref "LED592") (pin "K") (pinfunction "C_K") (pintype "passive"))
      (node (ref "LED608") (pin "K") (pinfunction "C_K") (pintype "passive"))
      (node (ref "LED624") (pin "K") (pinfunction "C_K") (pintype "passive"))
      (node (ref "LED64") (pin "K") (pinfunction "C_K") (pintype "passive"))
      (node (ref "LED640") (pin "K") (pinfunction "C_K") (pintype "passive"))
      (node (ref "LED80") (pin "K") (pinfunction "C_K") (pintype "passive"))
      (node (ref "LED96") (pin "K") (pinfunction "C_K") (pintype "passive"))
      (node (ref "U$16") (pin "3") (pinfunction "D_3") (pintype "passive"))
    )
    (net (code "128") (name "Net-(LED113-PadA)") (class "Default")
      (node (ref "LED113") (pin "A") (pinfunction "A_A") (pintype "passive"))
      (node (ref "LED114") (pin "A") (pinfunction "A_A") (pintype "passive"))
      (node (ref "LED115") (pin "A") (pinfunction "A_A") (pintype "passive"))
      (node (ref "LED116") (pin "A") (pinfunction "A_A") (pintype "passive"))
      (node (ref "LED117") (pin "A") (pinfunction "A_A") (pintype "passive"))
      (node (ref "LED118") (pin "A") (pinfunction "A_A") (pintype "passive"))
      (node (ref "LED119") (pin "A") (pinfunction "A_A") (pintype "passive"))
      (node (ref "LED120") (pin "A") (pinfunction "A_A") (pintype "passive"))
      (node (ref "LED121") (pin "A") (pinfunction "A_A") (pintype "passive"))
      (node (ref "LED122") (pin "A") (pinfunction "A_A") (pintype "passive"))
      (node (ref "LED123") (pin "A") (pinfunction "A_A") (pintype "passive"))
      (node (ref "LED124") (pin "A") (pinfunction "A_A") (pintype "passive"))
      (node (ref "LED125") (pin "A") (pinfunction "A_A") (pintype "passive"))
      (node (ref "LED126") (pin "A") (pinfunction "A_A") (pintype "passive"))
      (node (ref "LED127") (pin "A") (pinfunction "A_A") (pintype "passive"))
      (node (ref "LED128") (pin "A") (pinfunction "A_A") (pintype "passive"))
      (node (ref "R24") (pin "1") (pinfunction "1_1") (pintype "passive"))
    )
    (net (code "129") (name "Net-(LED114-C)") (class "Default")
      (node (ref "LED114") (pin "K") (pinfunction "C_K") (pintype "passive"))
      (node (ref "LED130") (pin "K") (pinfunction "C_K") (pintype "passive"))
      (node (ref "LED146") (pin "K") (pinfunction "C_K") (pintype "passive"))
      (node (ref "LED162") (pin "K") (pinfunction "C_K") (pintype "passive"))
      (node (ref "LED178") (pin "K") (pinfunction "C_K") (pintype "passive"))
      (node (ref "LED18") (pin "K") (pinfunction "C_K") (pintype "passive"))
      (node (ref "LED194") (pin "K") (pinfunction "C_K") (pintype "passive"))
      (node (ref "LED2") (pin "K") (pinfunction "C_K") (pintype "passive"))
      (node (ref "LED210") (pin "K") (pinfunction "C_K") (pintype "passive"))
      (node (ref "LED226") (pin "K") (pinfunction "C_K") (pintype "passive"))
      (node (ref "LED242") (pin "K") (pinfunction "C_K") (pintype "passive"))
      (node (ref "LED258") (pin "K") (pinfunction "C_K") (pintype "passive"))
      (node (ref "LED274") (pin "K") (pinfunction "C_K") (pintype "passive"))
      (node (ref "LED290") (pin "K") (pinfunction "C_K") (pintype "passive"))
      (node (ref "LED306") (pin "K") (pinfunction "C_K") (pintype "passive"))
      (node (ref "LED322") (pin "K") (pinfunction "C_K") (pintype "passive"))
      (node (ref "LED338") (pin "K") (pinfunction "C_K") (pintype "passive"))
      (node (ref "LED34") (pin "K") (pinfunction "C_K") (pintype "passive"))
      (node (ref "LED354") (pin "K") (pinfunction "C_K") (pintype "passive"))
      (node (ref "LED370") (pin "K") (pinfunction "C_K") (pintype "passive"))
      (node (ref "LED386") (pin "K") (pinfunction "C_K") (pintype "passive"))
      (node (ref "LED402") (pin "K") (pinfunction "C_K") (pintype "passive"))
      (node (ref "LED418") (pin "K") (pinfunction "C_K") (pintype "passive"))
      (node (ref "LED434") (pin "K") (pinfunction "C_K") (pintype "passive"))
      (node (ref "LED450") (pin "K") (pinfunction "C_K") (pintype "passive"))
      (node (ref "LED466") (pin "K") (pinfunction "C_K") (pintype "passive"))
      (node (ref "LED482") (pin "K") (pinfunction "C_K") (pintype "passive"))
      (node (ref "LED498") (pin "K") (pinfunction "C_K") (pintype "passive"))
      (node (ref "LED50") (pin "K") (pinfunction "C_K") (pintype "passive"))
      (node (ref "LED514") (pin "K") (pinfunction "C_K") (pintype "passive"))
      (node (ref "LED530") (pin "K") (pinfunction "C_K") (pintype "passive"))
      (node (ref "LED546") (pin "K") (pinfunction "C_K") (pintype "passive"))
      (node (ref "LED562") (pin "K") (pinfunction "C_K") (pintype "passive"))
      (node (ref "LED578") (pin "K") (pinfunction "C_K") (pintype "passive"))
      (node (ref "LED594") (pin "K") (pinfunction "C_K") (pintype "passive"))
      (node (ref "LED610") (pin "K") (pinfunction "C_K") (pintype "passive"))
      (node (ref "LED626") (pin "K") (pinfunction "C_K") (pintype "passive"))
      (node (ref "LED66") (pin "K") (pinfunction "C_K") (pintype "passive"))
      (node (ref "LED82") (pin "K") (pinfunction "C_K") (pintype "passive"))
      (node (ref "LED98") (pin "K") (pinfunction "C_K") (pintype "passive"))
      (node (ref "U$2") (pin "3") (pinfunction "D_3") (pintype "passive"))
    )
    (net (code "130") (name "Net-(LED115-C)") (class "Default")
      (node (ref "LED115") (pin "K") (pinfunction "C_K") (pintype "passive"))
      (node (ref "LED131") (pin "K") (pinfunction "C_K") (pintype "passive"))
      (node (ref "LED147") (pin "K") (pinfunction "C_K") (pintype "passive"))
      (node (ref "LED163") (pin "K") (pinfunction "C_K") (pintype "passive"))
      (node (ref "LED179") (pin "K") (pinfunction "C_K") (pintype "passive"))
      (node (ref "LED19") (pin "K") (pinfunction "C_K") (pintype "passive"))
      (node (ref "LED195") (pin "K") (pinfunction "C_K") (pintype "passive"))
      (node (ref "LED211") (pin "K") (pinfunction "C_K") (pintype "passive"))
      (node (ref "LED227") (pin "K") (pinfunction "C_K") (pintype "passive"))
      (node (ref "LED243") (pin "K") (pinfunction "C_K") (pintype "passive"))
      (node (ref "LED259") (pin "K") (pinfunction "C_K") (pintype "passive"))
      (node (ref "LED275") (pin "K") (pinfunction "C_K") (pintype "passive"))
      (node (ref "LED291") (pin "K") (pinfunction "C_K") (pintype "passive"))
      (node (ref "LED3") (pin "K") (pinfunction "C_K") (pintype "passive"))
      (node (ref "LED307") (pin "K") (pinfunction "C_K") (pintype "passive"))
      (node (ref "LED323") (pin "K") (pinfunction "C_K") (pintype "passive"))
      (node (ref "LED339") (pin "K") (pinfunction "C_K") (pintype "passive"))
      (node (ref "LED35") (pin "K") (pinfunction "C_K") (pintype "passive"))
      (node (ref "LED355") (pin "K") (pinfunction "C_K") (pintype "passive"))
      (node (ref "LED371") (pin "K") (pinfunction "C_K") (pintype "passive"))
      (node (ref "LED387") (pin "K") (pinfunction "C_K") (pintype "passive"))
      (node (ref "LED403") (pin "K") (pinfunction "C_K") (pintype "passive"))
      (node (ref "LED419") (pin "K") (pinfunction "C_K") (pintype "passive"))
      (node (ref "LED435") (pin "K") (pinfunction "C_K") (pintype "passive"))
      (node (ref "LED451") (pin "K") (pinfunction "C_K") (pintype "passive"))
      (node (ref "LED467") (pin "K") (pinfunction "C_K") (pintype "passive"))
      (node (ref "LED483") (pin "K") (pinfunction "C_K") (pintype "passive"))
      (node (ref "LED499") (pin "K") (pinfunction "C_K") (pintype "passive"))
      (node (ref "LED51") (pin "K") (pinfunction "C_K") (pintype "passive"))
      (node (ref "LED515") (pin "K") (pinfunction "C_K") (pintype "passive"))
      (node (ref "LED531") (pin "K") (pinfunction "C_K") (pintype "passive"))
      (node (ref "LED547") (pin "K") (pinfunction "C_K") (pintype "passive"))
      (node (ref "LED563") (pin "K") (pinfunction "C_K") (pintype "passive"))
      (node (ref "LED579") (pin "K") (pinfunction "C_K") (pintype "passive"))
      (node (ref "LED595") (pin "K") (pinfunction "C_K") (pintype "passive"))
      (node (ref "LED611") (pin "K") (pinfunction "C_K") (pintype "passive"))
      (node (ref "LED627") (pin "K") (pinfunction "C_K") (pintype "passive"))
      (node (ref "LED67") (pin "K") (pinfunction "C_K") (pintype "passive"))
      (node (ref "LED83") (pin "K") (pinfunction "C_K") (pintype "passive"))
      (node (ref "LED99") (pin "K") (pinfunction "C_K") (pintype "passive"))
      (node (ref "U$3") (pin "3") (pinfunction "D_3") (pintype "passive"))
    )
    (net (code "131") (name "Net-(LED129-PadA)") (class "Default")
      (node (ref "LED129") (pin "A") (pinfunction "A_A") (pintype "passive"))
      (node (ref "LED130") (pin "A") (pinfunction "A_A") (pintype "passive"))
      (node (ref "LED131") (pin "A") (pinfunction "A_A") (pintype "passive"))
      (node (ref "LED132") (pin "A") (pinfunction "A_A") (pintype "passive"))
      (node (ref "LED133") (pin "A") (pinfunction "A_A") (pintype "passive"))
      (node (ref "LED134") (pin "A") (pinfunction "A_A") (pintype "passive"))
      (node (ref "LED135") (pin "A") (pinfunction "A_A") (pintype "passive"))
      (node (ref "LED136") (pin "A") (pinfunction "A_A") (pintype "passive"))
      (node (ref "LED137") (pin "A") (pinfunction "A_A") (pintype "passive"))
      (node (ref "LED138") (pin "A") (pinfunction "A_A") (pintype "passive"))
      (node (ref "LED139") (pin "A") (pinfunction "A_A") (pintype "passive"))
      (node (ref "LED140") (pin "A") (pinfunction "A_A") (pintype "passive"))
      (node (ref "LED141") (pin "A") (pinfunction "A_A") (pintype "passive"))
      (node (ref "LED142") (pin "A") (pinfunction "A_A") (pintype "passive"))
      (node (ref "LED143") (pin "A") (pinfunction "A_A") (pintype "passive"))
      (node (ref "LED144") (pin "A") (pinfunction "A_A") (pintype "passive"))
      (node (ref "R25") (pin "1") (pinfunction "1_1") (pintype "passive"))
    )
    (net (code "132") (name "Net-(LED145-PadA)") (class "Default")
      (node (ref "LED145") (pin "A") (pinfunction "A_A") (pintype "passive"))
      (node (ref "LED146") (pin "A") (pinfunction "A_A") (pintype "passive"))
      (node (ref "LED147") (pin "A") (pinfunction "A_A") (pintype "passive"))
      (node (ref "LED148") (pin "A") (pinfunction "A_A") (pintype "passive"))
      (node (ref "LED149") (pin "A") (pinfunction "A_A") (pintype "passive"))
      (node (ref "LED150") (pin "A") (pinfunction "A_A") (pintype "passive"))
      (node (ref "LED151") (pin "A") (pinfunction "A_A") (pintype "passive"))
      (node (ref "LED152") (pin "A") (pinfunction "A_A") (pintype "passive"))
      (node (ref "LED153") (pin "A") (pinfunction "A_A") (pintype "passive"))
      (node (ref "LED154") (pin "A") (pinfunction "A_A") (pintype "passive"))
      (node (ref "LED155") (pin "A") (pinfunction "A_A") (pintype "passive"))
      (node (ref "LED156") (pin "A") (pinfunction "A_A") (pintype "passive"))
      (node (ref "LED157") (pin "A") (pinfunction "A_A") (pintype "passive"))
      (node (ref "LED158") (pin "A") (pinfunction "A_A") (pintype "passive"))
      (node (ref "LED159") (pin "A") (pinfunction "A_A") (pintype "passive"))
      (node (ref "LED160") (pin "A") (pinfunction "A_A") (pintype "passive"))
      (node (ref "R26") (pin "1") (pinfunction "1_1") (pintype "passive"))
    )
    (net (code "133") (name "Net-(LED161-PadA)") (class "Default")
      (node (ref "LED161") (pin "A") (pinfunction "A_A") (pintype "passive"))
      (node (ref "LED162") (pin "A") (pinfunction "A_A") (pintype "passive"))
      (node (ref "LED163") (pin "A") (pinfunction "A_A") (pintype "passive"))
      (node (ref "LED164") (pin "A") (pinfunction "A_A") (pintype "passive"))
      (node (ref "LED165") (pin "A") (pinfunction "A_A") (pintype "passive"))
      (node (ref "LED166") (pin "A") (pinfunction "A_A") (pintype "passive"))
      (node (ref "LED167") (pin "A") (pinfunction "A_A") (pintype "passive"))
      (node (ref "LED168") (pin "A") (pinfunction "A_A") (pintype "passive"))
      (node (ref "LED169") (pin "A") (pinfunction "A_A") (pintype "passive"))
      (node (ref "LED170") (pin "A") (pinfunction "A_A") (pintype "passive"))
      (node (ref "LED171") (pin "A") (pinfunction "A_A") (pintype "passive"))
      (node (ref "LED172") (pin "A") (pinfunction "A_A") (pintype "passive"))
      (node (ref "LED173") (pin "A") (pinfunction "A_A") (pintype "passive"))
      (node (ref "LED174") (pin "A") (pinfunction "A_A") (pintype "passive"))
      (node (ref "LED175") (pin "A") (pinfunction "A_A") (pintype "passive"))
      (node (ref "LED176") (pin "A") (pinfunction "A_A") (pintype "passive"))
      (node (ref "R27") (pin "1") (pinfunction "1_1") (pintype "passive"))
    )
    (net (code "134") (name "Net-(LED177-PadA)") (class "Default")
      (node (ref "LED177") (pin "A") (pinfunction "A_A") (pintype "passive"))
      (node (ref "LED178") (pin "A") (pinfunction "A_A") (pintype "passive"))
      (node (ref "LED179") (pin "A") (pinfunction "A_A") (pintype "passive"))
      (node (ref "LED180") (pin "A") (pinfunction "A_A") (pintype "passive"))
      (node (ref "LED181") (pin "A") (pinfunction "A_A") (pintype "passive"))
      (node (ref "LED182") (pin "A") (pinfunction "A_A") (pintype "passive"))
      (node (ref "LED183") (pin "A") (pinfunction "A_A") (pintype "passive"))
      (node (ref "LED184") (pin "A") (pinfunction "A_A") (pintype "passive"))
      (node (ref "LED185") (pin "A") (pinfunction "A_A") (pintype "passive"))
      (node (ref "LED186") (pin "A") (pinfunction "A_A") (pintype "passive"))
      (node (ref "LED187") (pin "A") (pinfunction "A_A") (pintype "passive"))
      (node (ref "LED188") (pin "A") (pinfunction "A_A") (pintype "passive"))
      (node (ref "LED189") (pin "A") (pinfunction "A_A") (pintype "passive"))
      (node (ref "LED190") (pin "A") (pinfunction "A_A") (pintype "passive"))
      (node (ref "LED191") (pin "A") (pinfunction "A_A") (pintype "passive"))
      (node (ref "LED192") (pin "A") (pinfunction "A_A") (pintype "passive"))
      (node (ref "R28") (pin "1") (pinfunction "1_1") (pintype "passive"))
    )
    (net (code "135") (name "Net-(LED193-PadA)") (class "Default")
      (node (ref "LED193") (pin "A") (pinfunction "A_A") (pintype "passive"))
      (node (ref "LED194") (pin "A") (pinfunction "A_A") (pintype "passive"))
      (node (ref "LED195") (pin "A") (pinfunction "A_A") (pintype "passive"))
      (node (ref "LED196") (pin "A") (pinfunction "A_A") (pintype "passive"))
      (node (ref "LED197") (pin "A") (pinfunction "A_A") (pintype "passive"))
      (node (ref "LED198") (pin "A") (pinfunction "A_A") (pintype "passive"))
      (node (ref "LED199") (pin "A") (pinfunction "A_A") (pintype "passive"))
      (node (ref "LED200") (pin "A") (pinfunction "A_A") (pintype "passive"))
      (node (ref "LED201") (pin "A") (pinfunction "A_A") (pintype "passive"))
      (node (ref "LED202") (pin "A") (pinfunction "A_A") (pintype "passive"))
      (node (ref "LED203") (pin "A") (pinfunction "A_A") (pintype "passive"))
      (node (ref "LED204") (pin "A") (pinfunction "A_A") (pintype "passive"))
      (node (ref "LED205") (pin "A") (pinfunction "A_A") (pintype "passive"))
      (node (ref "LED206") (pin "A") (pinfunction "A_A") (pintype "passive"))
      (node (ref "LED207") (pin "A") (pinfunction "A_A") (pintype "passive"))
      (node (ref "LED208") (pin "A") (pinfunction "A_A") (pintype "passive"))
      (node (ref "R29") (pin "1") (pinfunction "1_1") (pintype "passive"))
    )
    (net (code "136") (name "Net-(LED209-PadA)") (class "Default")
      (node (ref "LED209") (pin "A") (pinfunction "A_A") (pintype "passive"))
      (node (ref "LED210") (pin "A") (pinfunction "A_A") (pintype "passive"))
      (node (ref "LED211") (pin "A") (pinfunction "A_A") (pintype "passive"))
      (node (ref "LED212") (pin "A") (pinfunction "A_A") (pintype "passive"))
      (node (ref "LED213") (pin "A") (pinfunction "A_A") (pintype "passive"))
      (node (ref "LED214") (pin "A") (pinfunction "A_A") (pintype "passive"))
      (node (ref "LED215") (pin "A") (pinfunction "A_A") (pintype "passive"))
      (node (ref "LED216") (pin "A") (pinfunction "A_A") (pintype "passive"))
      (node (ref "LED217") (pin "A") (pinfunction "A_A") (pintype "passive"))
      (node (ref "LED218") (pin "A") (pinfunction "A_A") (pintype "passive"))
      (node (ref "LED219") (pin "A") (pinfunction "A_A") (pintype "passive"))
      (node (ref "LED220") (pin "A") (pinfunction "A_A") (pintype "passive"))
      (node (ref "LED221") (pin "A") (pinfunction "A_A") (pintype "passive"))
      (node (ref "LED222") (pin "A") (pinfunction "A_A") (pintype "passive"))
      (node (ref "LED223") (pin "A") (pinfunction "A_A") (pintype "passive"))
      (node (ref "LED224") (pin "A") (pinfunction "A_A") (pintype "passive"))
      (node (ref "R30") (pin "1") (pinfunction "1_1") (pintype "passive"))
    )
    (net (code "137") (name "Net-(LED225-PadA)") (class "Default")
      (node (ref "LED225") (pin "A") (pinfunction "A_A") (pintype "passive"))
      (node (ref "LED226") (pin "A") (pinfunction "A_A") (pintype "passive"))
      (node (ref "LED227") (pin "A") (pinfunction "A_A") (pintype "passive"))
      (node (ref "LED228") (pin "A") (pinfunction "A_A") (pintype "passive"))
      (node (ref "LED229") (pin "A") (pinfunction "A_A") (pintype "passive"))
      (node (ref "LED230") (pin "A") (pinfunction "A_A") (pintype "passive"))
      (node (ref "LED231") (pin "A") (pinfunction "A_A") (pintype "passive"))
      (node (ref "LED232") (pin "A") (pinfunction "A_A") (pintype "passive"))
      (node (ref "LED233") (pin "A") (pinfunction "A_A") (pintype "passive"))
      (node (ref "LED234") (pin "A") (pinfunction "A_A") (pintype "passive"))
      (node (ref "LED235") (pin "A") (pinfunction "A_A") (pintype "passive"))
      (node (ref "LED236") (pin "A") (pinfunction "A_A") (pintype "passive"))
      (node (ref "LED237") (pin "A") (pinfunction "A_A") (pintype "passive"))
      (node (ref "LED238") (pin "A") (pinfunction "A_A") (pintype "passive"))
      (node (ref "LED239") (pin "A") (pinfunction "A_A") (pintype "passive"))
      (node (ref "LED240") (pin "A") (pinfunction "A_A") (pintype "passive"))
      (node (ref "R31") (pin "1") (pinfunction "1_1") (pintype "passive"))
    )
    (net (code "138") (name "Net-(LED241-PadA)") (class "Default")
      (node (ref "LED241") (pin "A") (pinfunction "A_A") (pintype "passive"))
      (node (ref "LED242") (pin "A") (pinfunction "A_A") (pintype "passive"))
      (node (ref "LED243") (pin "A") (pinfunction "A_A") (pintype "passive"))
      (node (ref "LED244") (pin "A") (pinfunction "A_A") (pintype "passive"))
      (node (ref "LED245") (pin "A") (pinfunction "A_A") (pintype "passive"))
      (node (ref "LED246") (pin "A") (pinfunction "A_A") (pintype "passive"))
      (node (ref "LED247") (pin "A") (pinfunction "A_A") (pintype "passive"))
      (node (ref "LED248") (pin "A") (pinfunction "A_A") (pintype "passive"))
      (node (ref "LED249") (pin "A") (pinfunction "A_A") (pintype "passive"))
      (node (ref "LED250") (pin "A") (pinfunction "A_A") (pintype "passive"))
      (node (ref "LED251") (pin "A") (pinfunction "A_A") (pintype "passive"))
      (node (ref "LED252") (pin "A") (pinfunction "A_A") (pintype "passive"))
      (node (ref "LED253") (pin "A") (pinfunction "A_A") (pintype "passive"))
      (node (ref "LED254") (pin "A") (pinfunction "A_A") (pintype "passive"))
      (node (ref "LED255") (pin "A") (pinfunction "A_A") (pintype "passive"))
      (node (ref "LED256") (pin "A") (pinfunction "A_A") (pintype "passive"))
      (node (ref "R32") (pin "1") (pinfunction "1_1") (pintype "passive"))
    )
    (net (code "139") (name "Net-(LED257-PadA)") (class "Default")
      (node (ref "LED257") (pin "A") (pinfunction "A_A") (pintype "passive"))
      (node (ref "LED258") (pin "A") (pinfunction "A_A") (pintype "passive"))
      (node (ref "LED259") (pin "A") (pinfunction "A_A") (pintype "passive"))
      (node (ref "LED260") (pin "A") (pinfunction "A_A") (pintype "passive"))
      (node (ref "LED261") (pin "A") (pinfunction "A_A") (pintype "passive"))
      (node (ref "LED262") (pin "A") (pinfunction "A_A") (pintype "passive"))
      (node (ref "LED263") (pin "A") (pinfunction "A_A") (pintype "passive"))
      (node (ref "LED264") (pin "A") (pinfunction "A_A") (pintype "passive"))
      (node (ref "LED265") (pin "A") (pinfunction "A_A") (pintype "passive"))
      (node (ref "LED266") (pin "A") (pinfunction "A_A") (pintype "passive"))
      (node (ref "LED267") (pin "A") (pinfunction "A_A") (pintype "passive"))
      (node (ref "LED268") (pin "A") (pinfunction "A_A") (pintype "passive"))
      (node (ref "LED269") (pin "A") (pinfunction "A_A") (pintype "passive"))
      (node (ref "LED270") (pin "A") (pinfunction "A_A") (pintype "passive"))
      (node (ref "LED271") (pin "A") (pinfunction "A_A") (pintype "passive"))
      (node (ref "LED272") (pin "A") (pinfunction "A_A") (pintype "passive"))
      (node (ref "R33") (pin "1") (pinfunction "1_1") (pintype "passive"))
    )
    (net (code "140") (name "Net-(LED273-PadA)") (class "Default")
      (node (ref "LED273") (pin "A") (pinfunction "A_A") (pintype "passive"))
      (node (ref "LED274") (pin "A") (pinfunction "A_A") (pintype "passive"))
      (node (ref "LED275") (pin "A") (pinfunction "A_A") (pintype "passive"))
      (node (ref "LED276") (pin "A") (pinfunction "A_A") (pintype "passive"))
      (node (ref "LED277") (pin "A") (pinfunction "A_A") (pintype "passive"))
      (node (ref "LED278") (pin "A") (pinfunction "A_A") (pintype "passive"))
      (node (ref "LED279") (pin "A") (pinfunction "A_A") (pintype "passive"))
      (node (ref "LED280") (pin "A") (pinfunction "A_A") (pintype "passive"))
      (node (ref "LED281") (pin "A") (pinfunction "A_A") (pintype "passive"))
      (node (ref "LED282") (pin "A") (pinfunction "A_A") (pintype "passive"))
      (node (ref "LED283") (pin "A") (pinfunction "A_A") (pintype "passive"))
      (node (ref "LED284") (pin "A") (pinfunction "A_A") (pintype "passive"))
      (node (ref "LED285") (pin "A") (pinfunction "A_A") (pintype "passive"))
      (node (ref "LED286") (pin "A") (pinfunction "A_A") (pintype "passive"))
      (node (ref "LED287") (pin "A") (pinfunction "A_A") (pintype "passive"))
      (node (ref "LED288") (pin "A") (pinfunction "A_A") (pintype "passive"))
      (node (ref "R34") (pin "1") (pinfunction "1_1") (pintype "passive"))
    )
    (net (code "141") (name "Net-(LED289-PadA)") (class "Default")
      (node (ref "LED289") (pin "A") (pinfunction "A_A") (pintype "passive"))
      (node (ref "LED290") (pin "A") (pinfunction "A_A") (pintype "passive"))
      (node (ref "LED291") (pin "A") (pinfunction "A_A") (pintype "passive"))
      (node (ref "LED292") (pin "A") (pinfunction "A_A") (pintype "passive"))
      (node (ref "LED293") (pin "A") (pinfunction "A_A") (pintype "passive"))
      (node (ref "LED294") (pin "A") (pinfunction "A_A") (pintype "passive"))
      (node (ref "LED295") (pin "A") (pinfunction "A_A") (pintype "passive"))
      (node (ref "LED296") (pin "A") (pinfunction "A_A") (pintype "passive"))
      (node (ref "LED297") (pin "A") (pinfunction "A_A") (pintype "passive"))
      (node (ref "LED298") (pin "A") (pinfunction "A_A") (pintype "passive"))
      (node (ref "LED299") (pin "A") (pinfunction "A_A") (pintype "passive"))
      (node (ref "LED300") (pin "A") (pinfunction "A_A") (pintype "passive"))
      (node (ref "LED301") (pin "A") (pinfunction "A_A") (pintype "passive"))
      (node (ref "LED302") (pin "A") (pinfunction "A_A") (pintype "passive"))
      (node (ref "LED303") (pin "A") (pinfunction "A_A") (pintype "passive"))
      (node (ref "LED304") (pin "A") (pinfunction "A_A") (pintype "passive"))
      (node (ref "R35") (pin "1") (pinfunction "1_1") (pintype "passive"))
    )
    (net (code "142") (name "Net-(LED305-PadA)") (class "Default")
      (node (ref "LED305") (pin "A") (pinfunction "A_A") (pintype "passive"))
      (node (ref "LED306") (pin "A") (pinfunction "A_A") (pintype "passive"))
      (node (ref "LED307") (pin "A") (pinfunction "A_A") (pintype "passive"))
      (node (ref "LED308") (pin "A") (pinfunction "A_A") (pintype "passive"))
      (node (ref "LED309") (pin "A") (pinfunction "A_A") (pintype "passive"))
      (node (ref "LED310") (pin "A") (pinfunction "A_A") (pintype "passive"))
      (node (ref "LED311") (pin "A") (pinfunction "A_A") (pintype "passive"))
      (node (ref "LED312") (pin "A") (pinfunction "A_A") (pintype "passive"))
      (node (ref "LED313") (pin "A") (pinfunction "A_A") (pintype "passive"))
      (node (ref "LED314") (pin "A") (pinfunction "A_A") (pintype "passive"))
      (node (ref "LED315") (pin "A") (pinfunction "A_A") (pintype "passive"))
      (node (ref "LED316") (pin "A") (pinfunction "A_A") (pintype "passive"))
      (node (ref "LED317") (pin "A") (pinfunction "A_A") (pintype "passive"))
      (node (ref "LED318") (pin "A") (pinfunction "A_A") (pintype "passive"))
      (node (ref "LED319") (pin "A") (pinfunction "A_A") (pintype "passive"))
      (node (ref "LED320") (pin "A") (pinfunction "A_A") (pintype "passive"))
      (node (ref "R36") (pin "1") (pinfunction "1_1") (pintype "passive"))
    )
    (net (code "143") (name "Net-(LED321-PadA)") (class "Default")
      (node (ref "LED321") (pin "A") (pinfunction "A_A") (pintype "passive"))
      (node (ref "LED322") (pin "A") (pinfunction "A_A") (pintype "passive"))
      (node (ref "LED323") (pin "A") (pinfunction "A_A") (pintype "passive"))
      (node (ref "LED324") (pin "A") (pinfunction "A_A") (pintype "passive"))
      (node (ref "LED325") (pin "A") (pinfunction "A_A") (pintype "passive"))
      (node (ref "LED326") (pin "A") (pinfunction "A_A") (pintype "passive"))
      (node (ref "LED327") (pin "A") (pinfunction "A_A") (pintype "passive"))
      (node (ref "LED328") (pin "A") (pinfunction "A_A") (pintype "passive"))
      (node (ref "LED329") (pin "A") (pinfunction "A_A") (pintype "passive"))
      (node (ref "LED330") (pin "A") (pinfunction "A_A") (pintype "passive"))
      (node (ref "LED331") (pin "A") (pinfunction "A_A") (pintype "passive"))
      (node (ref "LED332") (pin "A") (pinfunction "A_A") (pintype "passive"))
      (node (ref "LED333") (pin "A") (pinfunction "A_A") (pintype "passive"))
      (node (ref "LED334") (pin "A") (pinfunction "A_A") (pintype "passive"))
      (node (ref "LED335") (pin "A") (pinfunction "A_A") (pintype "passive"))
      (node (ref "LED336") (pin "A") (pinfunction "A_A") (pintype "passive"))
      (node (ref "R37") (pin "1") (pinfunction "1_1") (pintype "passive"))
    )
    (net (code "144") (name "Net-(LED337-PadA)") (class "Default")
      (node (ref "LED337") (pin "A") (pinfunction "A_A") (pintype "passive"))
      (node (ref "LED338") (pin "A") (pinfunction "A_A") (pintype "passive"))
      (node (ref "LED339") (pin "A") (pinfunction "A_A") (pintype "passive"))
      (node (ref "LED340") (pin "A") (pinfunction "A_A") (pintype "passive"))
      (node (ref "LED341") (pin "A") (pinfunction "A_A") (pintype "passive"))
      (node (ref "LED342") (pin "A") (pinfunction "A_A") (pintype "passive"))
      (node (ref "LED343") (pin "A") (pinfunction "A_A") (pintype "passive"))
      (node (ref "LED344") (pin "A") (pinfunction "A_A") (pintype "passive"))
      (node (ref "LED345") (pin "A") (pinfunction "A_A") (pintype "passive"))
      (node (ref "LED346") (pin "A") (pinfunction "A_A") (pintype "passive"))
      (node (ref "LED347") (pin "A") (pinfunction "A_A") (pintype "passive"))
      (node (ref "LED348") (pin "A") (pinfunction "A_A") (pintype "passive"))
      (node (ref "LED349") (pin "A") (pinfunction "A_A") (pintype "passive"))
      (node (ref "LED350") (pin "A") (pinfunction "A_A") (pintype "passive"))
      (node (ref "LED351") (pin "A") (pinfunction "A_A") (pintype "passive"))
      (node (ref "LED352") (pin "A") (pinfunction "A_A") (pintype "passive"))
      (node (ref "R38") (pin "1") (pinfunction "1_1") (pintype "passive"))
    )
    (net (code "145") (name "Net-(LED353-PadA)") (class "Default")
      (node (ref "LED353") (pin "A") (pinfunction "A_A") (pintype "passive"))
      (node (ref "LED354") (pin "A") (pinfunction "A_A") (pintype "passive"))
      (node (ref "LED355") (pin "A") (pinfunction "A_A") (pintype "passive"))
      (node (ref "LED356") (pin "A") (pinfunction "A_A") (pintype "passive"))
      (node (ref "LED357") (pin "A") (pinfunction "A_A") (pintype "passive"))
      (node (ref "LED358") (pin "A") (pinfunction "A_A") (pintype "passive"))
      (node (ref "LED359") (pin "A") (pinfunction "A_A") (pintype "passive"))
      (node (ref "LED360") (pin "A") (pinfunction "A_A") (pintype "passive"))
      (node (ref "LED361") (pin "A") (pinfunction "A_A") (pintype "passive"))
      (node (ref "LED362") (pin "A") (pinfunction "A_A") (pintype "passive"))
      (node (ref "LED363") (pin "A") (pinfunction "A_A") (pintype "passive"))
      (node (ref "LED364") (pin "A") (pinfunction "A_A") (pintype "passive"))
      (node (ref "LED365") (pin "A") (pinfunction "A_A") (pintype "passive"))
      (node (ref "LED366") (pin "A") (pinfunction "A_A") (pintype "passive"))
      (node (ref "LED367") (pin "A") (pinfunction "A_A") (pintype "passive"))
      (node (ref "LED368") (pin "A") (pinfunction "A_A") (pintype "passive"))
      (node (ref "R39") (pin "1") (pinfunction "1_1") (pintype "passive"))
    )
    (net (code "146") (name "Net-(LED369-PadA)") (class "Default")
      (node (ref "LED369") (pin "A") (pinfunction "A_A") (pintype "passive"))
      (node (ref "LED370") (pin "A") (pinfunction "A_A") (pintype "passive"))
      (node (ref "LED371") (pin "A") (pinfunction "A_A") (pintype "passive"))
      (node (ref "LED372") (pin "A") (pinfunction "A_A") (pintype "passive"))
      (node (ref "LED373") (pin "A") (pinfunction "A_A") (pintype "passive"))
      (node (ref "LED374") (pin "A") (pinfunction "A_A") (pintype "passive"))
      (node (ref "LED375") (pin "A") (pinfunction "A_A") (pintype "passive"))
      (node (ref "LED376") (pin "A") (pinfunction "A_A") (pintype "passive"))
      (node (ref "LED377") (pin "A") (pinfunction "A_A") (pintype "passive"))
      (node (ref "LED378") (pin "A") (pinfunction "A_A") (pintype "passive"))
      (node (ref "LED379") (pin "A") (pinfunction "A_A") (pintype "passive"))
      (node (ref "LED380") (pin "A") (pinfunction "A_A") (pintype "passive"))
      (node (ref "LED381") (pin "A") (pinfunction "A_A") (pintype "passive"))
      (node (ref "LED382") (pin "A") (pinfunction "A_A") (pintype "passive"))
      (node (ref "LED383") (pin "A") (pinfunction "A_A") (pintype "passive"))
      (node (ref "LED384") (pin "A") (pinfunction "A_A") (pintype "passive"))
      (node (ref "R40") (pin "1") (pinfunction "1_1") (pintype "passive"))
    )
    (net (code "147") (name "Net-(LED385-PadA)") (class "Default")
      (node (ref "LED385") (pin "A") (pinfunction "A_A") (pintype "passive"))
      (node (ref "LED386") (pin "A") (pinfunction "A_A") (pintype "passive"))
      (node (ref "LED387") (pin "A") (pinfunction "A_A") (pintype "passive"))
      (node (ref "LED388") (pin "A") (pinfunction "A_A") (pintype "passive"))
      (node (ref "LED389") (pin "A") (pinfunction "A_A") (pintype "passive"))
      (node (ref "LED390") (pin "A") (pinfunction "A_A") (pintype "passive"))
      (node (ref "LED391") (pin "A") (pinfunction "A_A") (pintype "passive"))
      (node (ref "LED392") (pin "A") (pinfunction "A_A") (pintype "passive"))
      (node (ref "LED393") (pin "A") (pinfunction "A_A") (pintype "passive"))
      (node (ref "LED394") (pin "A") (pinfunction "A_A") (pintype "passive"))
      (node (ref "LED395") (pin "A") (pinfunction "A_A") (pintype "passive"))
      (node (ref "LED396") (pin "A") (pinfunction "A_A") (pintype "passive"))
      (node (ref "LED397") (pin "A") (pinfunction "A_A") (pintype "passive"))
      (node (ref "LED398") (pin "A") (pinfunction "A_A") (pintype "passive"))
      (node (ref "LED399") (pin "A") (pinfunction "A_A") (pintype "passive"))
      (node (ref "LED400") (pin "A") (pinfunction "A_A") (pintype "passive"))
      (node (ref "R41") (pin "1") (pinfunction "1_1") (pintype "passive"))
    )
    (net (code "148") (name "Net-(LED401-PadA)") (class "Default")
      (node (ref "LED401") (pin "A") (pinfunction "A_A") (pintype "passive"))
      (node (ref "LED402") (pin "A") (pinfunction "A_A") (pintype "passive"))
      (node (ref "LED403") (pin "A") (pinfunction "A_A") (pintype "passive"))
      (node (ref "LED404") (pin "A") (pinfunction "A_A") (pintype "passive"))
      (node (ref "LED405") (pin "A") (pinfunction "A_A") (pintype "passive"))
      (node (ref "LED406") (pin "A") (pinfunction "A_A") (pintype "passive"))
      (node (ref "LED407") (pin "A") (pinfunction "A_A") (pintype "passive"))
      (node (ref "LED408") (pin "A") (pinfunction "A_A") (pintype "passive"))
      (node (ref "LED409") (pin "A") (pinfunction "A_A") (pintype "passive"))
      (node (ref "LED410") (pin "A") (pinfunction "A_A") (pintype "passive"))
      (node (ref "LED411") (pin "A") (pinfunction "A_A") (pintype "passive"))
      (node (ref "LED412") (pin "A") (pinfunction "A_A") (pintype "passive"))
      (node (ref "LED413") (pin "A") (pinfunction "A_A") (pintype "passive"))
      (node (ref "LED414") (pin "A") (pinfunction "A_A") (pintype "passive"))
      (node (ref "LED415") (pin "A") (pinfunction "A_A") (pintype "passive"))
      (node (ref "LED416") (pin "A") (pinfunction "A_A") (pintype "passive"))
      (node (ref "R42") (pin "1") (pinfunction "1_1") (pintype "passive"))
    )
    (net (code "149") (name "Net-(LED417-PadA)") (class "Default")
      (node (ref "LED417") (pin "A") (pinfunction "A_A") (pintype "passive"))
      (node (ref "LED418") (pin "A") (pinfunction "A_A") (pintype "passive"))
      (node (ref "LED419") (pin "A") (pinfunction "A_A") (pintype "passive"))
      (node (ref "LED420") (pin "A") (pinfunction "A_A") (pintype "passive"))
      (node (ref "LED421") (pin "A") (pinfunction "A_A") (pintype "passive"))
      (node (ref "LED422") (pin "A") (pinfunction "A_A") (pintype "passive"))
      (node (ref "LED423") (pin "A") (pinfunction "A_A") (pintype "passive"))
      (node (ref "LED424") (pin "A") (pinfunction "A_A") (pintype "passive"))
      (node (ref "LED425") (pin "A") (pinfunction "A_A") (pintype "passive"))
      (node (ref "LED426") (pin "A") (pinfunction "A_A") (pintype "passive"))
      (node (ref "LED427") (pin "A") (pinfunction "A_A") (pintype "passive"))
      (node (ref "LED428") (pin "A") (pinfunction "A_A") (pintype "passive"))
      (node (ref "LED429") (pin "A") (pinfunction "A_A") (pintype "passive"))
      (node (ref "LED430") (pin "A") (pinfunction "A_A") (pintype "passive"))
      (node (ref "LED431") (pin "A") (pinfunction "A_A") (pintype "passive"))
      (node (ref "LED432") (pin "A") (pinfunction "A_A") (pintype "passive"))
      (node (ref "R43") (pin "1") (pinfunction "1_1") (pintype "passive"))
    )
    (net (code "150") (name "Net-(LED433-PadA)") (class "Default")
      (node (ref "LED433") (pin "A") (pinfunction "A_A") (pintype "passive"))
      (node (ref "LED434") (pin "A") (pinfunction "A_A") (pintype "passive"))
      (node (ref "LED435") (pin "A") (pinfunction "A_A") (pintype "passive"))
      (node (ref "LED436") (pin "A") (pinfunction "A_A") (pintype "passive"))
      (node (ref "LED437") (pin "A") (pinfunction "A_A") (pintype "passive"))
      (node (ref "LED438") (pin "A") (pinfunction "A_A") (pintype "passive"))
      (node (ref "LED439") (pin "A") (pinfunction "A_A") (pintype "passive"))
      (node (ref "LED440") (pin "A") (pinfunction "A_A") (pintype "passive"))
      (node (ref "LED441") (pin "A") (pinfunction "A_A") (pintype "passive"))
      (node (ref "LED442") (pin "A") (pinfunction "A_A") (pintype "passive"))
      (node (ref "LED443") (pin "A") (pinfunction "A_A") (pintype "passive"))
      (node (ref "LED444") (pin "A") (pinfunction "A_A") (pintype "passive"))
      (node (ref "LED445") (pin "A") (pinfunction "A_A") (pintype "passive"))
      (node (ref "LED446") (pin "A") (pinfunction "A_A") (pintype "passive"))
      (node (ref "LED447") (pin "A") (pinfunction "A_A") (pintype "passive"))
      (node (ref "LED448") (pin "A") (pinfunction "A_A") (pintype "passive"))
      (node (ref "R44") (pin "1") (pinfunction "1_1") (pintype "passive"))
    )
    (net (code "151") (name "Net-(LED449-PadA)") (class "Default")
      (node (ref "LED449") (pin "A") (pinfunction "A_A") (pintype "passive"))
      (node (ref "LED450") (pin "A") (pinfunction "A_A") (pintype "passive"))
      (node (ref "LED451") (pin "A") (pinfunction "A_A") (pintype "passive"))
      (node (ref "LED452") (pin "A") (pinfunction "A_A") (pintype "passive"))
      (node (ref "LED453") (pin "A") (pinfunction "A_A") (pintype "passive"))
      (node (ref "LED454") (pin "A") (pinfunction "A_A") (pintype "passive"))
      (node (ref "LED455") (pin "A") (pinfunction "A_A") (pintype "passive"))
      (node (ref "LED456") (pin "A") (pinfunction "A_A") (pintype "passive"))
      (node (ref "LED457") (pin "A") (pinfunction "A_A") (pintype "passive"))
      (node (ref "LED458") (pin "A") (pinfunction "A_A") (pintype "passive"))
      (node (ref "LED459") (pin "A") (pinfunction "A_A") (pintype "passive"))
      (node (ref "LED460") (pin "A") (pinfunction "A_A") (pintype "passive"))
      (node (ref "LED461") (pin "A") (pinfunction "A_A") (pintype "passive"))
      (node (ref "LED462") (pin "A") (pinfunction "A_A") (pintype "passive"))
      (node (ref "LED463") (pin "A") (pinfunction "A_A") (pintype "passive"))
      (node (ref "LED464") (pin "A") (pinfunction "A_A") (pintype "passive"))
      (node (ref "R45") (pin "1") (pinfunction "1_1") (pintype "passive"))
    )
    (net (code "152") (name "Net-(LED465-PadA)") (class "Default")
      (node (ref "LED465") (pin "A") (pinfunction "A_A") (pintype "passive"))
      (node (ref "LED466") (pin "A") (pinfunction "A_A") (pintype "passive"))
      (node (ref "LED467") (pin "A") (pinfunction "A_A") (pintype "passive"))
      (node (ref "LED468") (pin "A") (pinfunction "A_A") (pintype "passive"))
      (node (ref "LED469") (pin "A") (pinfunction "A_A") (pintype "passive"))
      (node (ref "LED470") (pin "A") (pinfunction "A_A") (pintype "passive"))
      (node (ref "LED471") (pin "A") (pinfunction "A_A") (pintype "passive"))
      (node (ref "LED472") (pin "A") (pinfunction "A_A") (pintype "passive"))
      (node (ref "LED473") (pin "A") (pinfunction "A_A") (pintype "passive"))
      (node (ref "LED474") (pin "A") (pinfunction "A_A") (pintype "passive"))
      (node (ref "LED475") (pin "A") (pinfunction "A_A") (pintype "passive"))
      (node (ref "LED476") (pin "A") (pinfunction "A_A") (pintype "passive"))
      (node (ref "LED477") (pin "A") (pinfunction "A_A") (pintype "passive"))
      (node (ref "LED478") (pin "A") (pinfunction "A_A") (pintype "passive"))
      (node (ref "LED479") (pin "A") (pinfunction "A_A") (pintype "passive"))
      (node (ref "LED480") (pin "A") (pinfunction "A_A") (pintype "passive"))
      (node (ref "R46") (pin "1") (pinfunction "1_1") (pintype "passive"))
    )
    (net (code "153") (name "Net-(LED481-PadA)") (class "Default")
      (node (ref "LED481") (pin "A") (pinfunction "A_A") (pintype "passive"))
      (node (ref "LED482") (pin "A") (pinfunction "A_A") (pintype "passive"))
      (node (ref "LED483") (pin "A") (pinfunction "A_A") (pintype "passive"))
      (node (ref "LED484") (pin "A") (pinfunction "A_A") (pintype "passive"))
      (node (ref "LED485") (pin "A") (pinfunction "A_A") (pintype "passive"))
      (node (ref "LED486") (pin "A") (pinfunction "A_A") (pintype "passive"))
      (node (ref "LED487") (pin "A") (pinfunction "A_A") (pintype "passive"))
      (node (ref "LED488") (pin "A") (pinfunction "A_A") (pintype "passive"))
      (node (ref "LED489") (pin "A") (pinfunction "A_A") (pintype "passive"))
      (node (ref "LED490") (pin "A") (pinfunction "A_A") (pintype "passive"))
      (node (ref "LED491") (pin "A") (pinfunction "A_A") (pintype "passive"))
      (node (ref "LED492") (pin "A") (pinfunction "A_A") (pintype "passive"))
      (node (ref "LED493") (pin "A") (pinfunction "A_A") (pintype "passive"))
      (node (ref "LED494") (pin "A") (pinfunction "A_A") (pintype "passive"))
      (node (ref "LED495") (pin "A") (pinfunction "A_A") (pintype "passive"))
      (node (ref "LED496") (pin "A") (pinfunction "A_A") (pintype "passive"))
      (node (ref "R47") (pin "1") (pinfunction "1_1") (pintype "passive"))
    )
    (net (code "154") (name "Net-(LED497-PadA)") (class "Default")
      (node (ref "LED497") (pin "A") (pinfunction "A_A") (pintype "passive"))
      (node (ref "LED498") (pin "A") (pinfunction "A_A") (pintype "passive"))
      (node (ref "LED499") (pin "A") (pinfunction "A_A") (pintype "passive"))
      (node (ref "LED500") (pin "A") (pinfunction "A_A") (pintype "passive"))
      (node (ref "LED501") (pin "A") (pinfunction "A_A") (pintype "passive"))
      (node (ref "LED502") (pin "A") (pinfunction "A_A") (pintype "passive"))
      (node (ref "LED503") (pin "A") (pinfunction "A_A") (pintype "passive"))
      (node (ref "LED504") (pin "A") (pinfunction "A_A") (pintype "passive"))
      (node (ref "LED505") (pin "A") (pinfunction "A_A") (pintype "passive"))
      (node (ref "LED506") (pin "A") (pinfunction "A_A") (pintype "passive"))
      (node (ref "LED507") (pin "A") (pinfunction "A_A") (pintype "passive"))
      (node (ref "LED508") (pin "A") (pinfunction "A_A") (pintype "passive"))
      (node (ref "LED509") (pin "A") (pinfunction "A_A") (pintype "passive"))
      (node (ref "LED510") (pin "A") (pinfunction "A_A") (pintype "passive"))
      (node (ref "LED511") (pin "A") (pinfunction "A_A") (pintype "passive"))
      (node (ref "LED512") (pin "A") (pinfunction "A_A") (pintype "passive"))
      (node (ref "R48") (pin "1") (pinfunction "1_1") (pintype "passive"))
    )
    (net (code "155") (name "Net-(LED513-PadA)") (class "Default")
      (node (ref "LED513") (pin "A") (pinfunction "A_A") (pintype "passive"))
      (node (ref "LED514") (pin "A") (pinfunction "A_A") (pintype "passive"))
      (node (ref "LED515") (pin "A") (pinfunction "A_A") (pintype "passive"))
      (node (ref "LED516") (pin "A") (pinfunction "A_A") (pintype "passive"))
      (node (ref "LED517") (pin "A") (pinfunction "A_A") (pintype "passive"))
      (node (ref "LED518") (pin "A") (pinfunction "A_A") (pintype "passive"))
      (node (ref "LED519") (pin "A") (pinfunction "A_A") (pintype "passive"))
      (node (ref "LED520") (pin "A") (pinfunction "A_A") (pintype "passive"))
      (node (ref "LED521") (pin "A") (pinfunction "A_A") (pintype "passive"))
      (node (ref "LED522") (pin "A") (pinfunction "A_A") (pintype "passive"))
      (node (ref "LED523") (pin "A") (pinfunction "A_A") (pintype "passive"))
      (node (ref "LED524") (pin "A") (pinfunction "A_A") (pintype "passive"))
      (node (ref "LED525") (pin "A") (pinfunction "A_A") (pintype "passive"))
      (node (ref "LED526") (pin "A") (pinfunction "A_A") (pintype "passive"))
      (node (ref "LED527") (pin "A") (pinfunction "A_A") (pintype "passive"))
      (node (ref "LED528") (pin "A") (pinfunction "A_A") (pintype "passive"))
      (node (ref "R49") (pin "1") (pinfunction "1_1") (pintype "passive"))
    )
    (net (code "156") (name "Net-(LED529-PadA)") (class "Default")
      (node (ref "LED529") (pin "A") (pinfunction "A_A") (pintype "passive"))
      (node (ref "LED530") (pin "A") (pinfunction "A_A") (pintype "passive"))
      (node (ref "LED531") (pin "A") (pinfunction "A_A") (pintype "passive"))
      (node (ref "LED532") (pin "A") (pinfunction "A_A") (pintype "passive"))
      (node (ref "LED533") (pin "A") (pinfunction "A_A") (pintype "passive"))
      (node (ref "LED534") (pin "A") (pinfunction "A_A") (pintype "passive"))
      (node (ref "LED535") (pin "A") (pinfunction "A_A") (pintype "passive"))
      (node (ref "LED536") (pin "A") (pinfunction "A_A") (pintype "passive"))
      (node (ref "LED537") (pin "A") (pinfunction "A_A") (pintype "passive"))
      (node (ref "LED538") (pin "A") (pinfunction "A_A") (pintype "passive"))
      (node (ref "LED539") (pin "A") (pinfunction "A_A") (pintype "passive"))
      (node (ref "LED540") (pin "A") (pinfunction "A_A") (pintype "passive"))
      (node (ref "LED541") (pin "A") (pinfunction "A_A") (pintype "passive"))
      (node (ref "LED542") (pin "A") (pinfunction "A_A") (pintype "passive"))
      (node (ref "LED543") (pin "A") (pinfunction "A_A") (pintype "passive"))
      (node (ref "LED544") (pin "A") (pinfunction "A_A") (pintype "passive"))
      (node (ref "R50") (pin "1") (pinfunction "1_1") (pintype "passive"))
    )
    (net (code "157") (name "Net-(LED545-PadA)") (class "Default")
      (node (ref "LED545") (pin "A") (pinfunction "A_A") (pintype "passive"))
      (node (ref "LED546") (pin "A") (pinfunction "A_A") (pintype "passive"))
      (node (ref "LED547") (pin "A") (pinfunction "A_A") (pintype "passive"))
      (node (ref "LED548") (pin "A") (pinfunction "A_A") (pintype "passive"))
      (node (ref "LED549") (pin "A") (pinfunction "A_A") (pintype "passive"))
      (node (ref "LED550") (pin "A") (pinfunction "A_A") (pintype "passive"))
      (node (ref "LED551") (pin "A") (pinfunction "A_A") (pintype "passive"))
      (node (ref "LED552") (pin "A") (pinfunction "A_A") (pintype "passive"))
      (node (ref "LED553") (pin "A") (pinfunction "A_A") (pintype "passive"))
      (node (ref "LED554") (pin "A") (pinfunction "A_A") (pintype "passive"))
      (node (ref "LED555") (pin "A") (pinfunction "A_A") (pintype "passive"))
      (node (ref "LED556") (pin "A") (pinfunction "A_A") (pintype "passive"))
      (node (ref "LED557") (pin "A") (pinfunction "A_A") (pintype "passive"))
      (node (ref "LED558") (pin "A") (pinfunction "A_A") (pintype "passive"))
      (node (ref "LED559") (pin "A") (pinfunction "A_A") (pintype "passive"))
      (node (ref "LED560") (pin "A") (pinfunction "A_A") (pintype "passive"))
      (node (ref "R51") (pin "1") (pinfunction "1_1") (pintype "passive"))
    )
    (net (code "158") (name "Net-(LED561-PadA)") (class "Default")
      (node (ref "LED561") (pin "A") (pinfunction "A_A") (pintype "passive"))
      (node (ref "LED562") (pin "A") (pinfunction "A_A") (pintype "passive"))
      (node (ref "LED563") (pin "A") (pinfunction "A_A") (pintype "passive"))
      (node (ref "LED564") (pin "A") (pinfunction "A_A") (pintype "passive"))
      (node (ref "LED565") (pin "A") (pinfunction "A_A") (pintype "passive"))
      (node (ref "LED566") (pin "A") (pinfunction "A_A") (pintype "passive"))
      (node (ref "LED567") (pin "A") (pinfunction "A_A") (pintype "passive"))
      (node (ref "LED568") (pin "A") (pinfunction "A_A") (pintype "passive"))
      (node (ref "LED569") (pin "A") (pinfunction "A_A") (pintype "passive"))
      (node (ref "LED570") (pin "A") (pinfunction "A_A") (pintype "passive"))
      (node (ref "LED571") (pin "A") (pinfunction "A_A") (pintype "passive"))
      (node (ref "LED572") (pin "A") (pinfunction "A_A") (pintype "passive"))
      (node (ref "LED573") (pin "A") (pinfunction "A_A") (pintype "passive"))
      (node (ref "LED574") (pin "A") (pinfunction "A_A") (pintype "passive"))
      (node (ref "LED575") (pin "A") (pinfunction "A_A") (pintype "passive"))
      (node (ref "LED576") (pin "A") (pinfunction "A_A") (pintype "passive"))
      (node (ref "R52") (pin "1") (pinfunction "1_1") (pintype "passive"))
    )
    (net (code "159") (name "Net-(LED577-PadA)") (class "Default")
      (node (ref "LED577") (pin "A") (pinfunction "A_A") (pintype "passive"))
      (node (ref "LED578") (pin "A") (pinfunction "A_A") (pintype "passive"))
      (node (ref "LED579") (pin "A") (pinfunction "A_A") (pintype "passive"))
      (node (ref "LED580") (pin "A") (pinfunction "A_A") (pintype "passive"))
      (node (ref "LED581") (pin "A") (pinfunction "A_A") (pintype "passive"))
      (node (ref "LED582") (pin "A") (pinfunction "A_A") (pintype "passive"))
      (node (ref "LED583") (pin "A") (pinfunction "A_A") (pintype "passive"))
      (node (ref "LED584") (pin "A") (pinfunction "A_A") (pintype "passive"))
      (node (ref "LED585") (pin "A") (pinfunction "A_A") (pintype "passive"))
      (node (ref "LED586") (pin "A") (pinfunction "A_A") (pintype "passive"))
      (node (ref "LED587") (pin "A") (pinfunction "A_A") (pintype "passive"))
      (node (ref "LED588") (pin "A") (pinfunction "A_A") (pintype "passive"))
      (node (ref "LED589") (pin "A") (pinfunction "A_A") (pintype "passive"))
      (node (ref "LED590") (pin "A") (pinfunction "A_A") (pintype "passive"))
      (node (ref "LED591") (pin "A") (pinfunction "A_A") (pintype "passive"))
      (node (ref "LED592") (pin "A") (pinfunction "A_A") (pintype "passive"))
      (node (ref "R53") (pin "1") (pinfunction "1_1") (pintype "passive"))
    )
    (net (code "160") (name "Net-(LED593-PadA)") (class "Default")
      (node (ref "LED593") (pin "A") (pinfunction "A_A") (pintype "passive"))
      (node (ref "LED594") (pin "A") (pinfunction "A_A") (pintype "passive"))
      (node (ref "LED595") (pin "A") (pinfunction "A_A") (pintype "passive"))
      (node (ref "LED596") (pin "A") (pinfunction "A_A") (pintype "passive"))
      (node (ref "LED597") (pin "A") (pinfunction "A_A") (pintype "passive"))
      (node (ref "LED598") (pin "A") (pinfunction "A_A") (pintype "passive"))
      (node (ref "LED599") (pin "A") (pinfunction "A_A") (pintype "passive"))
      (node (ref "LED600") (pin "A") (pinfunction "A_A") (pintype "passive"))
      (node (ref "LED601") (pin "A") (pinfunction "A_A") (pintype "passive"))
      (node (ref "LED602") (pin "A") (pinfunction "A_A") (pintype "passive"))
      (node (ref "LED603") (pin "A") (pinfunction "A_A") (pintype "passive"))
      (node (ref "LED604") (pin "A") (pinfunction "A_A") (pintype "passive"))
      (node (ref "LED605") (pin "A") (pinfunction "A_A") (pintype "passive"))
      (node (ref "LED606") (pin "A") (pinfunction "A_A") (pintype "passive"))
      (node (ref "LED607") (pin "A") (pinfunction "A_A") (pintype "passive"))
      (node (ref "LED608") (pin "A") (pinfunction "A_A") (pintype "passive"))
      (node (ref "R54") (pin "1") (pinfunction "1_1") (pintype "passive"))
    )
    (net (code "161") (name "Net-(LED609-PadA)") (class "Default")
      (node (ref "LED609") (pin "A") (pinfunction "A_A") (pintype "passive"))
      (node (ref "LED610") (pin "A") (pinfunction "A_A") (pintype "passive"))
      (node (ref "LED611") (pin "A") (pinfunction "A_A") (pintype "passive"))
      (node (ref "LED612") (pin "A") (pinfunction "A_A") (pintype "passive"))
      (node (ref "LED613") (pin "A") (pinfunction "A_A") (pintype "passive"))
      (node (ref "LED614") (pin "A") (pinfunction "A_A") (pintype "passive"))
      (node (ref "LED615") (pin "A") (pinfunction "A_A") (pintype "passive"))
      (node (ref "LED616") (pin "A") (pinfunction "A_A") (pintype "passive"))
      (node (ref "LED617") (pin "A") (pinfunction "A_A") (pintype "passive"))
      (node (ref "LED618") (pin "A") (pinfunction "A_A") (pintype "passive"))
      (node (ref "LED619") (pin "A") (pinfunction "A_A") (pintype "passive"))
      (node (ref "LED620") (pin "A") (pinfunction "A_A") (pintype "passive"))
      (node (ref "LED621") (pin "A") (pinfunction "A_A") (pintype "passive"))
      (node (ref "LED622") (pin "A") (pinfunction "A_A") (pintype "passive"))
      (node (ref "LED623") (pin "A") (pinfunction "A_A") (pintype "passive"))
      (node (ref "LED624") (pin "A") (pinfunction "A_A") (pintype "passive"))
      (node (ref "R55") (pin "1") (pinfunction "1_1") (pintype "passive"))
    )
    (net (code "162") (name "Net-(LED625-PadA)") (class "Default")
      (node (ref "LED625") (pin "A") (pinfunction "A_A") (pintype "passive"))
      (node (ref "LED626") (pin "A") (pinfunction "A_A") (pintype "passive"))
      (node (ref "LED627") (pin "A") (pinfunction "A_A") (pintype "passive"))
      (node (ref "LED628") (pin "A") (pinfunction "A_A") (pintype "passive"))
      (node (ref "LED629") (pin "A") (pinfunction "A_A") (pintype "passive"))
      (node (ref "LED630") (pin "A") (pinfunction "A_A") (pintype "passive"))
      (node (ref "LED631") (pin "A") (pinfunction "A_A") (pintype "passive"))
      (node (ref "LED632") (pin "A") (pinfunction "A_A") (pintype "passive"))
      (node (ref "LED633") (pin "A") (pinfunction "A_A") (pintype "passive"))
      (node (ref "LED634") (pin "A") (pinfunction "A_A") (pintype "passive"))
      (node (ref "LED635") (pin "A") (pinfunction "A_A") (pintype "passive"))
      (node (ref "LED636") (pin "A") (pinfunction "A_A") (pintype "passive"))
      (node (ref "LED637") (pin "A") (pinfunction "A_A") (pintype "passive"))
      (node (ref "LED638") (pin "A") (pinfunction "A_A") (pintype "passive"))
      (node (ref "LED639") (pin "A") (pinfunction "A_A") (pintype "passive"))
      (node (ref "LED640") (pin "A") (pinfunction "A_A") (pintype "passive"))
      (node (ref "R56") (pin "1") (pinfunction "1_1") (pintype "passive"))
    )
    (net (code "163") (name "Net-(S1-P)") (class "Default")
      (node (ref "C9") (pin "2") (pinfunction "2_2") (pintype "passive"))
      (node (ref "R108") (pin "1") (pinfunction "1_1") (pintype "passive"))
      (node (ref "S1") (pin "3") (pinfunction "P_3") (pintype "passive"))
      (node (ref "S1") (pin "4") (pinfunction "P1_4") (pintype "passive"))
    )
    (net (code "164") (name "Net-(T1-B)") (class "Default")
      (node (ref "R111") (pin "1") (pinfunction "1_1") (pintype "passive"))
      (node (ref "T1") (pin "2") (pinfunction "B_2") (pintype "passive"))
    )
    (net (code "165") (name "Net-(T1-C)") (class "Default")
      (node (ref "JP6") (pin "1") (pinfunction "1_1") (pintype "passive"))
      (node (ref "R110") (pin "2") (pinfunction "2_2") (pintype "passive"))
      (node (ref "T1") (pin "3") (pinfunction "C_3") (pintype "passive"))
    )
    (net (code "166") (name "Net-(U$1-G)") (class "Default")
      (node (ref "R1") (pin "2") (pinfunction "2_2") (pintype "passive"))
      (node (ref "R92") (pin "1") (pinfunction "1_1") (pintype "passive"))
      (node (ref "U$1") (pin "1") (pinfunction "G_1") (pintype "passive"))
    )
    (net (code "167") (name "Net-(U$2-G)") (class "Default")
      (node (ref "R4") (pin "2") (pinfunction "2_2") (pintype "passive"))
      (node (ref "R93") (pin "1") (pinfunction "1_1") (pintype "passive"))
      (node (ref "U$2") (pin "1") (pinfunction "G_1") (pintype "passive"))
    )
    (net (code "168") (name "Net-(U$3-G)") (class "Default")
      (node (ref "R5") (pin "2") (pinfunction "2_2") (pintype "passive"))
      (node (ref "R94") (pin "1") (pinfunction "1_1") (pintype "passive"))
      (node (ref "U$3") (pin "1") (pinfunction "G_1") (pintype "passive"))
    )
    (net (code "169") (name "Net-(U$4-G)") (class "Default")
      (node (ref "R6") (pin "2") (pinfunction "2_2") (pintype "passive"))
      (node (ref "R95") (pin "1") (pinfunction "1_1") (pintype "passive"))
      (node (ref "U$4") (pin "1") (pinfunction "G_1") (pintype "passive"))
    )
    (net (code "170") (name "Net-(U$5-G)") (class "Default")
      (node (ref "R7") (pin "2") (pinfunction "2_2") (pintype "passive"))
      (node (ref "R96") (pin "1") (pinfunction "1_1") (pintype "passive"))
      (node (ref "U$5") (pin "1") (pinfunction "G_1") (pintype "passive"))
    )
    (net (code "171") (name "Net-(U$6-G)") (class "Default")
      (node (ref "R8") (pin "2") (pinfunction "2_2") (pintype "passive"))
      (node (ref "R97") (pin "1") (pinfunction "1_1") (pintype "passive"))
      (node (ref "U$6") (pin "1") (pinfunction "G_1") (pintype "passive"))
    )
    (net (code "172") (name "Net-(U$7-G)") (class "Default")
      (node (ref "R9") (pin "2") (pinfunction "2_2") (pintype "passive"))
      (node (ref "R98") (pin "1") (pinfunction "1_1") (pintype "passive"))
      (node (ref "U$7") (pin "1") (pinfunction "G_1") (pintype "passive"))
    )
    (net (code "173") (name "Net-(U$8-G)") (class "Default")
      (node (ref "R10") (pin "2") (pinfunction "2_2") (pintype "passive"))
      (node (ref "R99") (pin "1") (pinfunction "1_1") (pintype "passive"))
      (node (ref "U$8") (pin "1") (pinfunction "G_1") (pintype "passive"))
    )
    (net (code "174") (name "Net-(U$9-G)") (class "Default")
      (node (ref "R100") (pin "1") (pinfunction "1_1") (pintype "passive"))
      (node (ref "R11") (pin "2") (pinfunction "2_2") (pintype "passive"))
      (node (ref "U$9") (pin "1") (pinfunction "G_1") (pintype "passive"))
    )
    (net (code "175") (name "Net-(U$10-G)") (class "Default")
      (node (ref "R101") (pin "1") (pinfunction "1_1") (pintype "passive"))
      (node (ref "R12") (pin "2") (pinfunction "2_2") (pintype "passive"))
      (node (ref "U$10") (pin "1") (pinfunction "G_1") (pintype "passive"))
    )
    (net (code "176") (name "Net-(U$11-G)") (class "Default")
      (node (ref "R102") (pin "1") (pinfunction "1_1") (pintype "passive"))
      (node (ref "R13") (pin "2") (pinfunction "2_2") (pintype "passive"))
      (node (ref "U$11") (pin "1") (pinfunction "G_1") (pintype "passive"))
    )
    (net (code "177") (name "Net-(U$12-G)") (class "Default")
      (node (ref "R103") (pin "1") (pinfunction "1_1") (pintype "passive"))
      (node (ref "R14") (pin "2") (pinfunction "2_2") (pintype "passive"))
      (node (ref "U$12") (pin "1") (pinfunction "G_1") (pintype "passive"))
    )
    (net (code "178") (name "Net-(U$13-G)") (class "Default")
      (node (ref "R104") (pin "1") (pinfunction "1_1") (pintype "passive"))
      (node (ref "R15") (pin "2") (pinfunction "2_2") (pintype "passive"))
      (node (ref "U$13") (pin "1") (pinfunction "G_1") (pintype "passive"))
    )
    (net (code "179") (name "Net-(U$14-G)") (class "Default")
      (node (ref "R105") (pin "1") (pinfunction "1_1") (pintype "passive"))
      (node (ref "R16") (pin "2") (pinfunction "2_2") (pintype "passive"))
      (node (ref "U$14") (pin "1") (pinfunction "G_1") (pintype "passive"))
    )
    (net (code "180") (name "Net-(U$15-G)") (class "Default")
      (node (ref "R106") (pin "1") (pinfunction "1_1") (pintype "passive"))
      (node (ref "R17") (pin "2") (pinfunction "2_2") (pintype "passive"))
      (node (ref "U$15") (pin "1") (pinfunction "G_1") (pintype "passive"))
    )
    (net (code "181") (name "Net-(U$16-G)") (class "Default")
      (node (ref "R107") (pin "1") (pinfunction "1_1") (pintype "passive"))
      (node (ref "R18") (pin "2") (pinfunction "2_2") (pintype "passive"))
      (node (ref "U$16") (pin "1") (pinfunction "G_1") (pintype "passive"))
    )
    (net (code "182") (name "Net-(U1-PB3)") (class "Default")
      (node (ref "JP3") (pin "3") (pinfunction "3_3") (pintype "passive"))
      (node (ref "U1") (pin "2") (pinfunction "PB3_2") (pintype "bidirectional"))
    )
    (net (code "183") (name "Net-(U1-PB4)") (class "Default")
      (node (ref "JP2") (pin "3") (pinfunction "3_3") (pintype "passive"))
      (node (ref "U1") (pin "3") (pinfunction "PB4_3") (pintype "bidirectional"))
    )
    (net (code "184") (name "Net-(X1A-KL)") (class "Default")
      (node (ref "JP2") (pin "1") (pinfunction "1_1") (pintype "passive"))
      (node (ref "X1") (pin "1") (pinfunction "KL_1") (pintype "passive"))
    )
    (net (code "185") (name "Net-(X1B-KL)") (class "Default")
      (node (ref "JP1") (pin "1") (pinfunction "1_1") (pintype "passive"))
      (node (ref "X1") (pin "2") (pinfunction "KL_2") (pintype "passive"))
    )
    (net (code "186") (name "Net-(X1C-KL)") (class "Default")
      (node (ref "JP3") (pin "1") (pinfunction "1_1") (pintype "passive"))
      (node (ref "X1") (pin "3") (pinfunction "KL_3") (pintype "passive"))
    )
    (net (code "187") (name "unconnected-(IC5A-QH*-Pad9)") (class "Default")
      (node (ref "IC5") (pin "9") (pinfunction "QH*_9") (pintype "tri_state"))
    )
  )
)
